# cfc-card.net
KiCad netlist of a schematic drawn in EAGLE
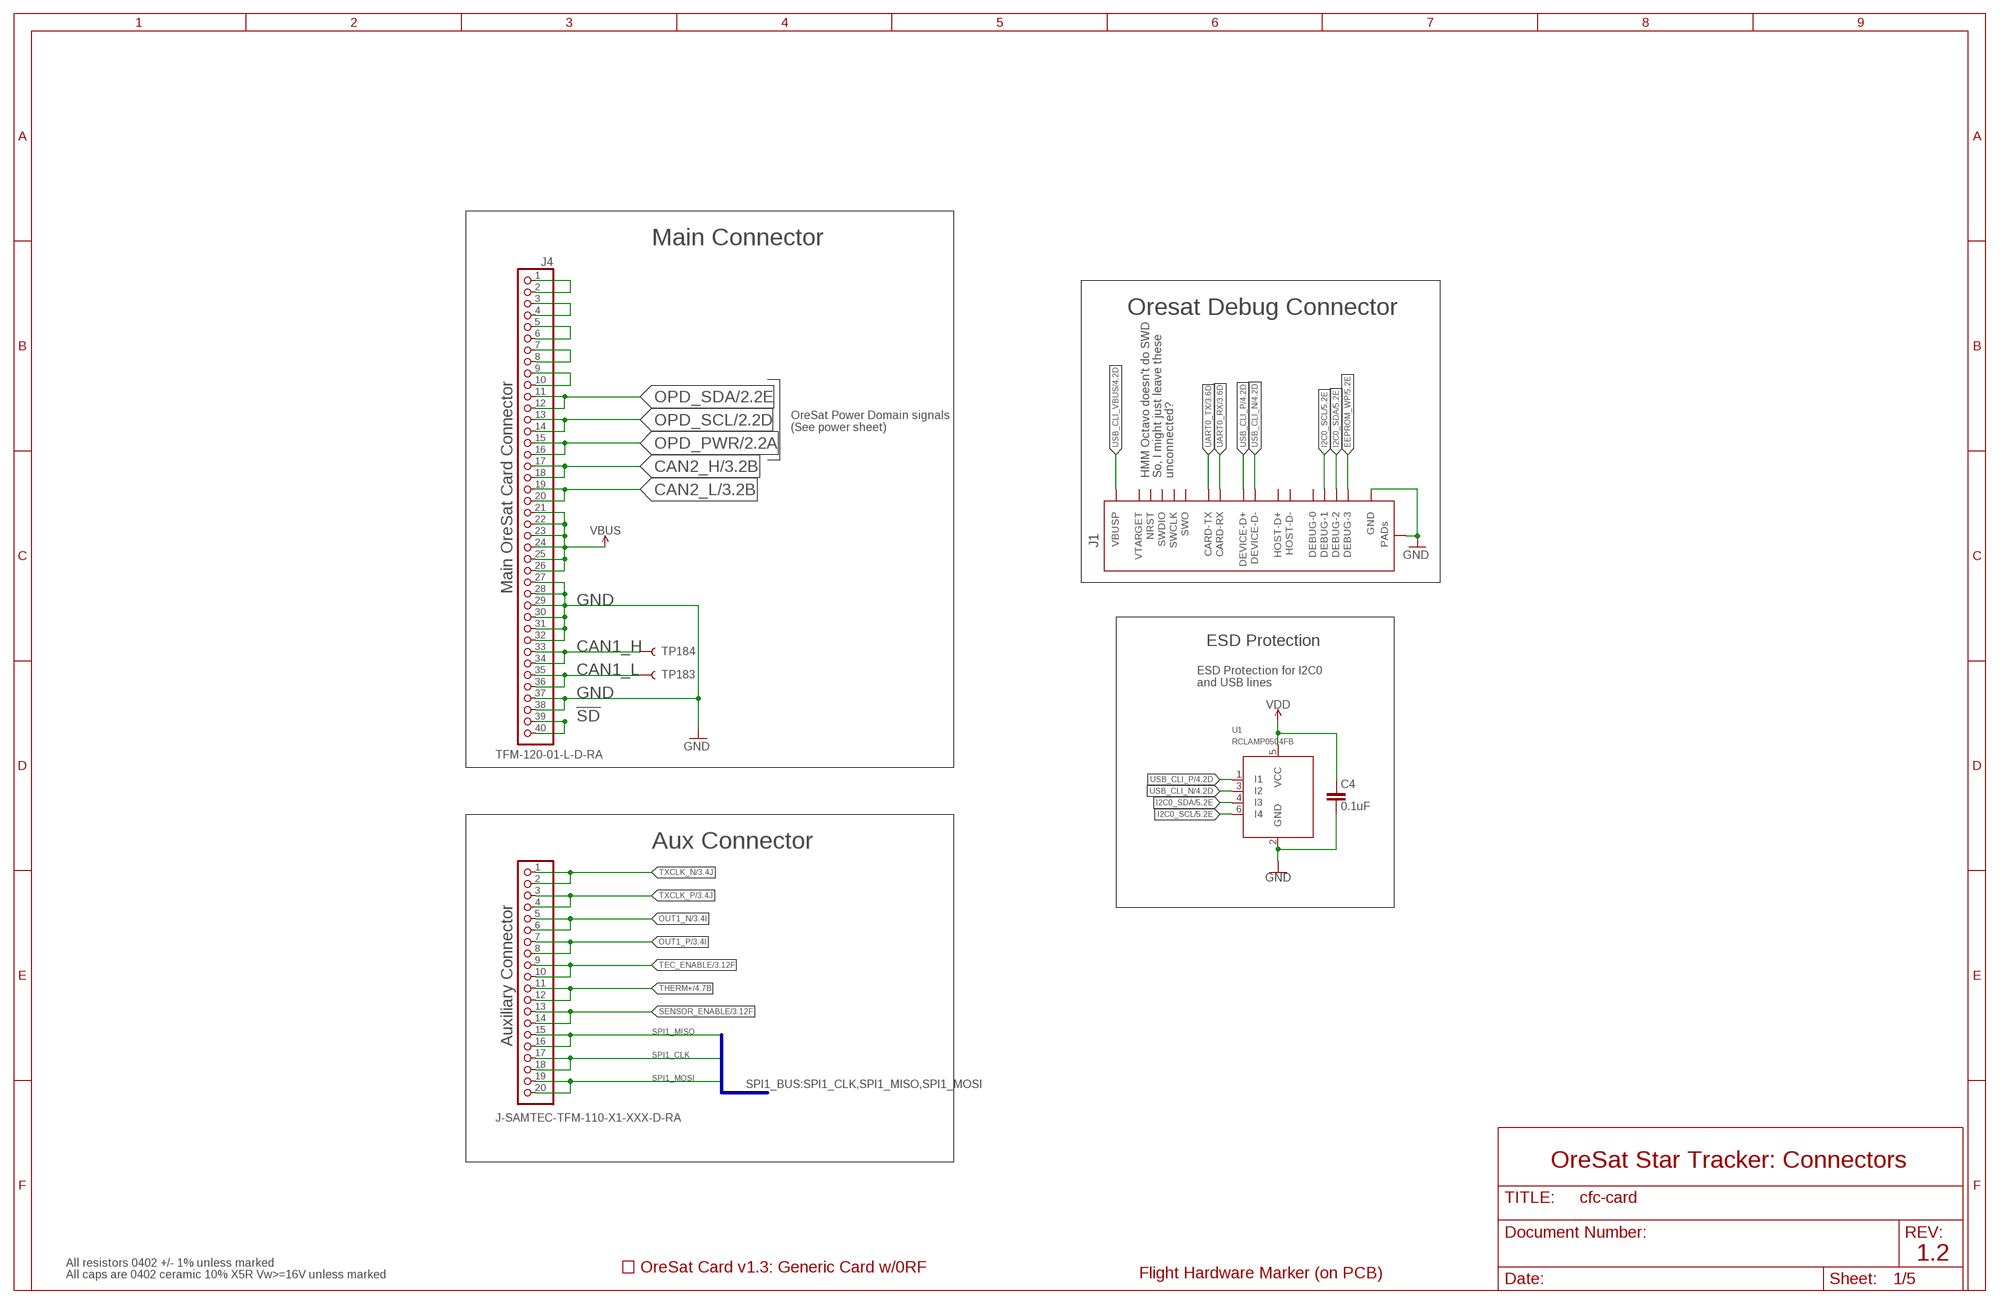
[diagram p0: schematic, sheet 1]
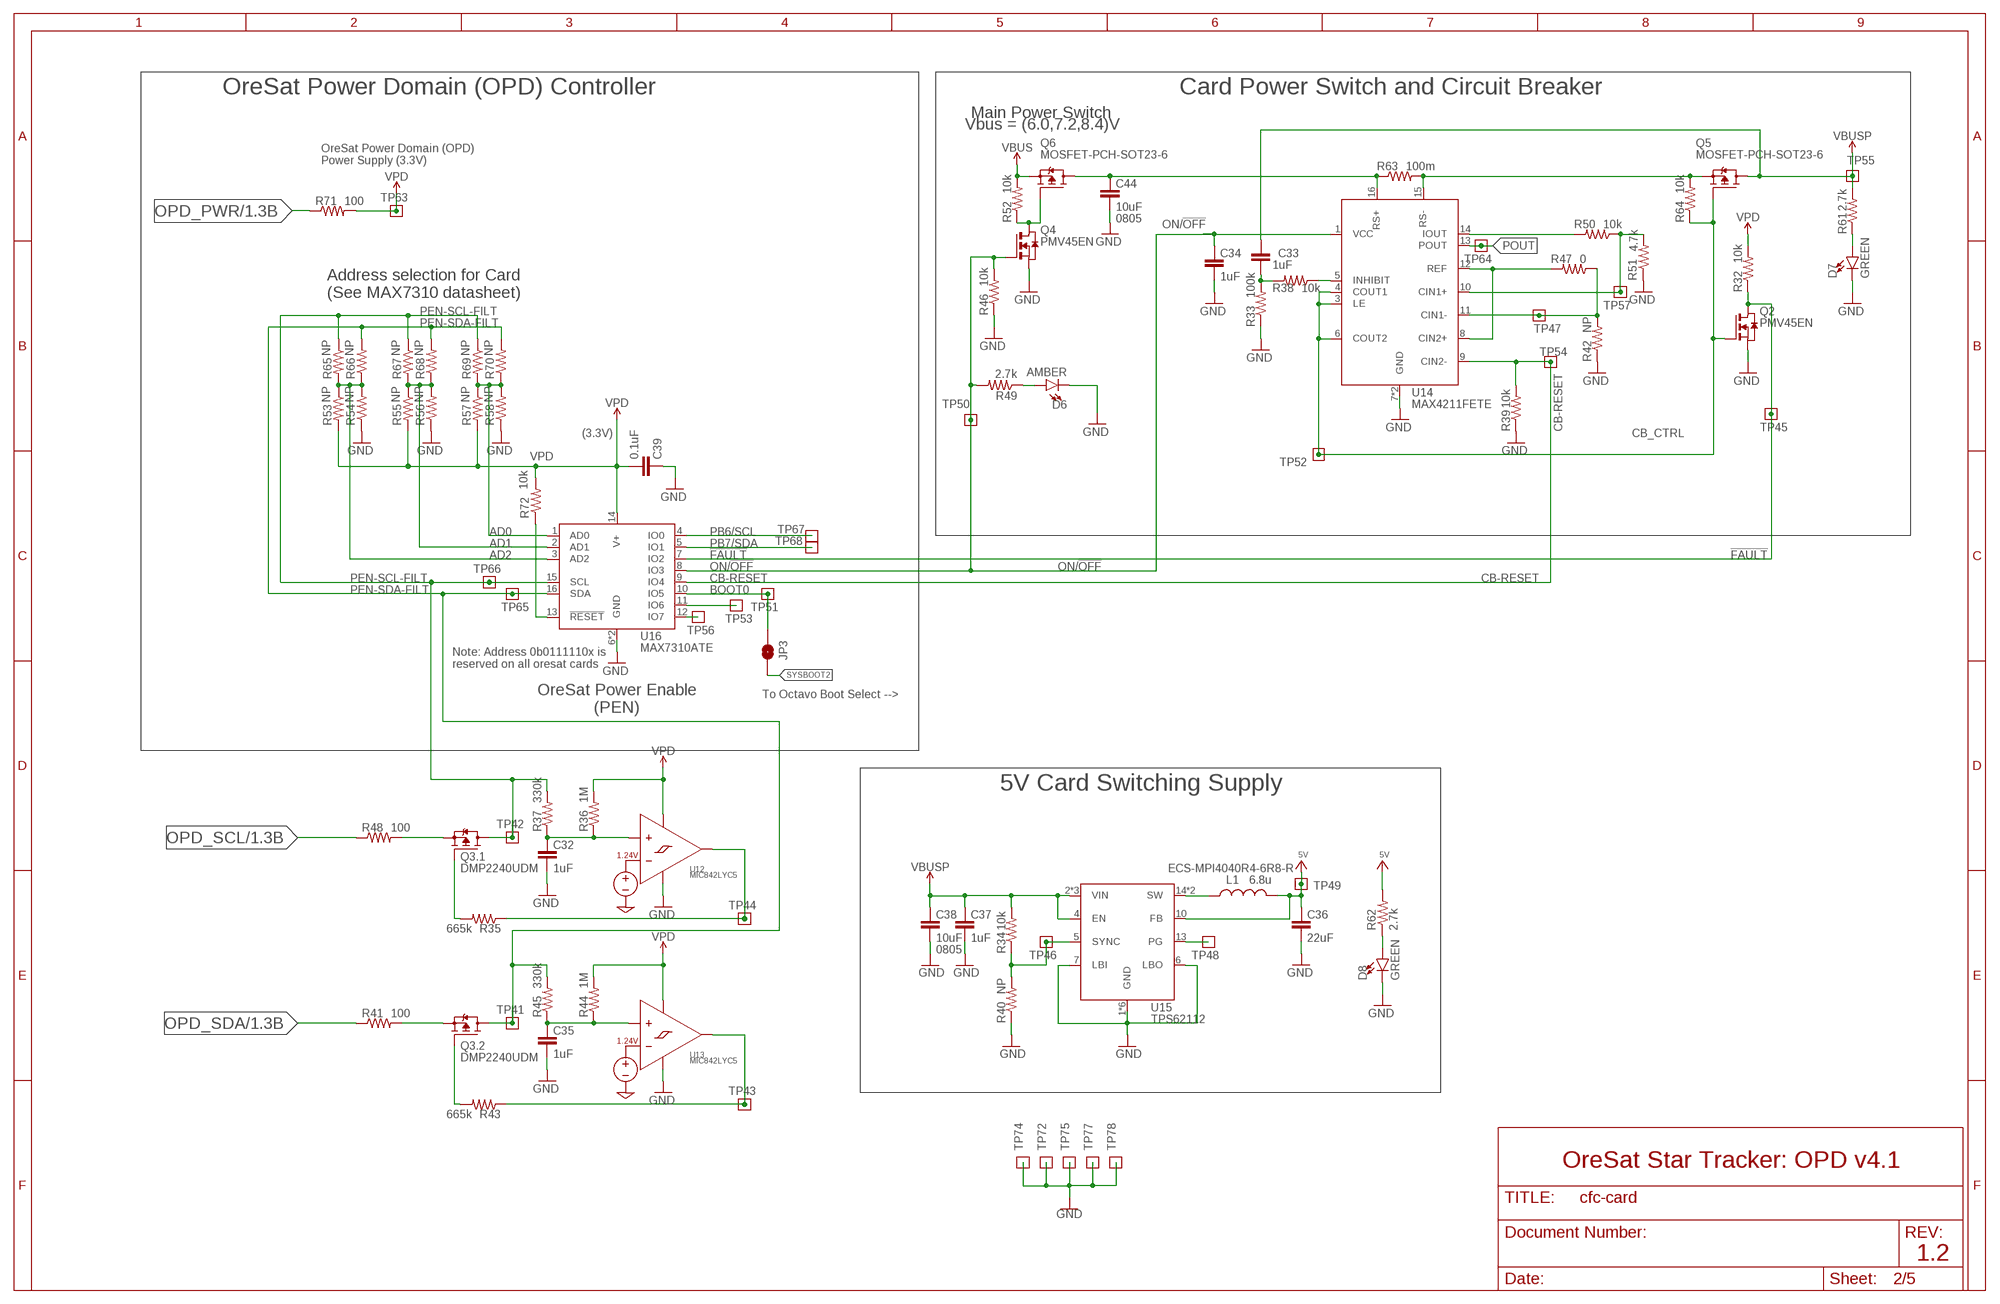
[diagram p1: schematic, sheet 2]
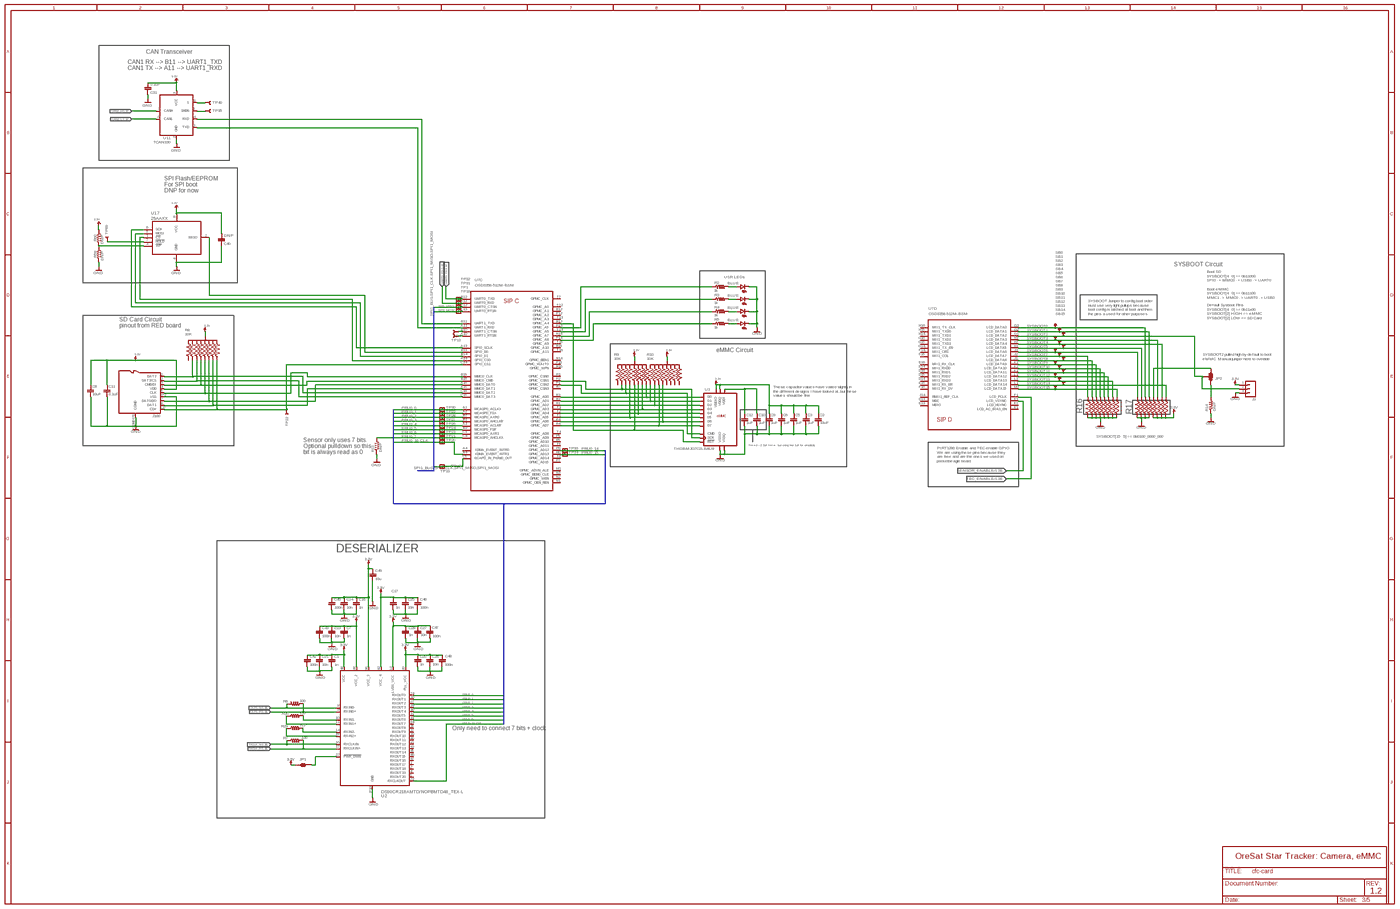
[diagram p2: schematic, sheet 3, overview]
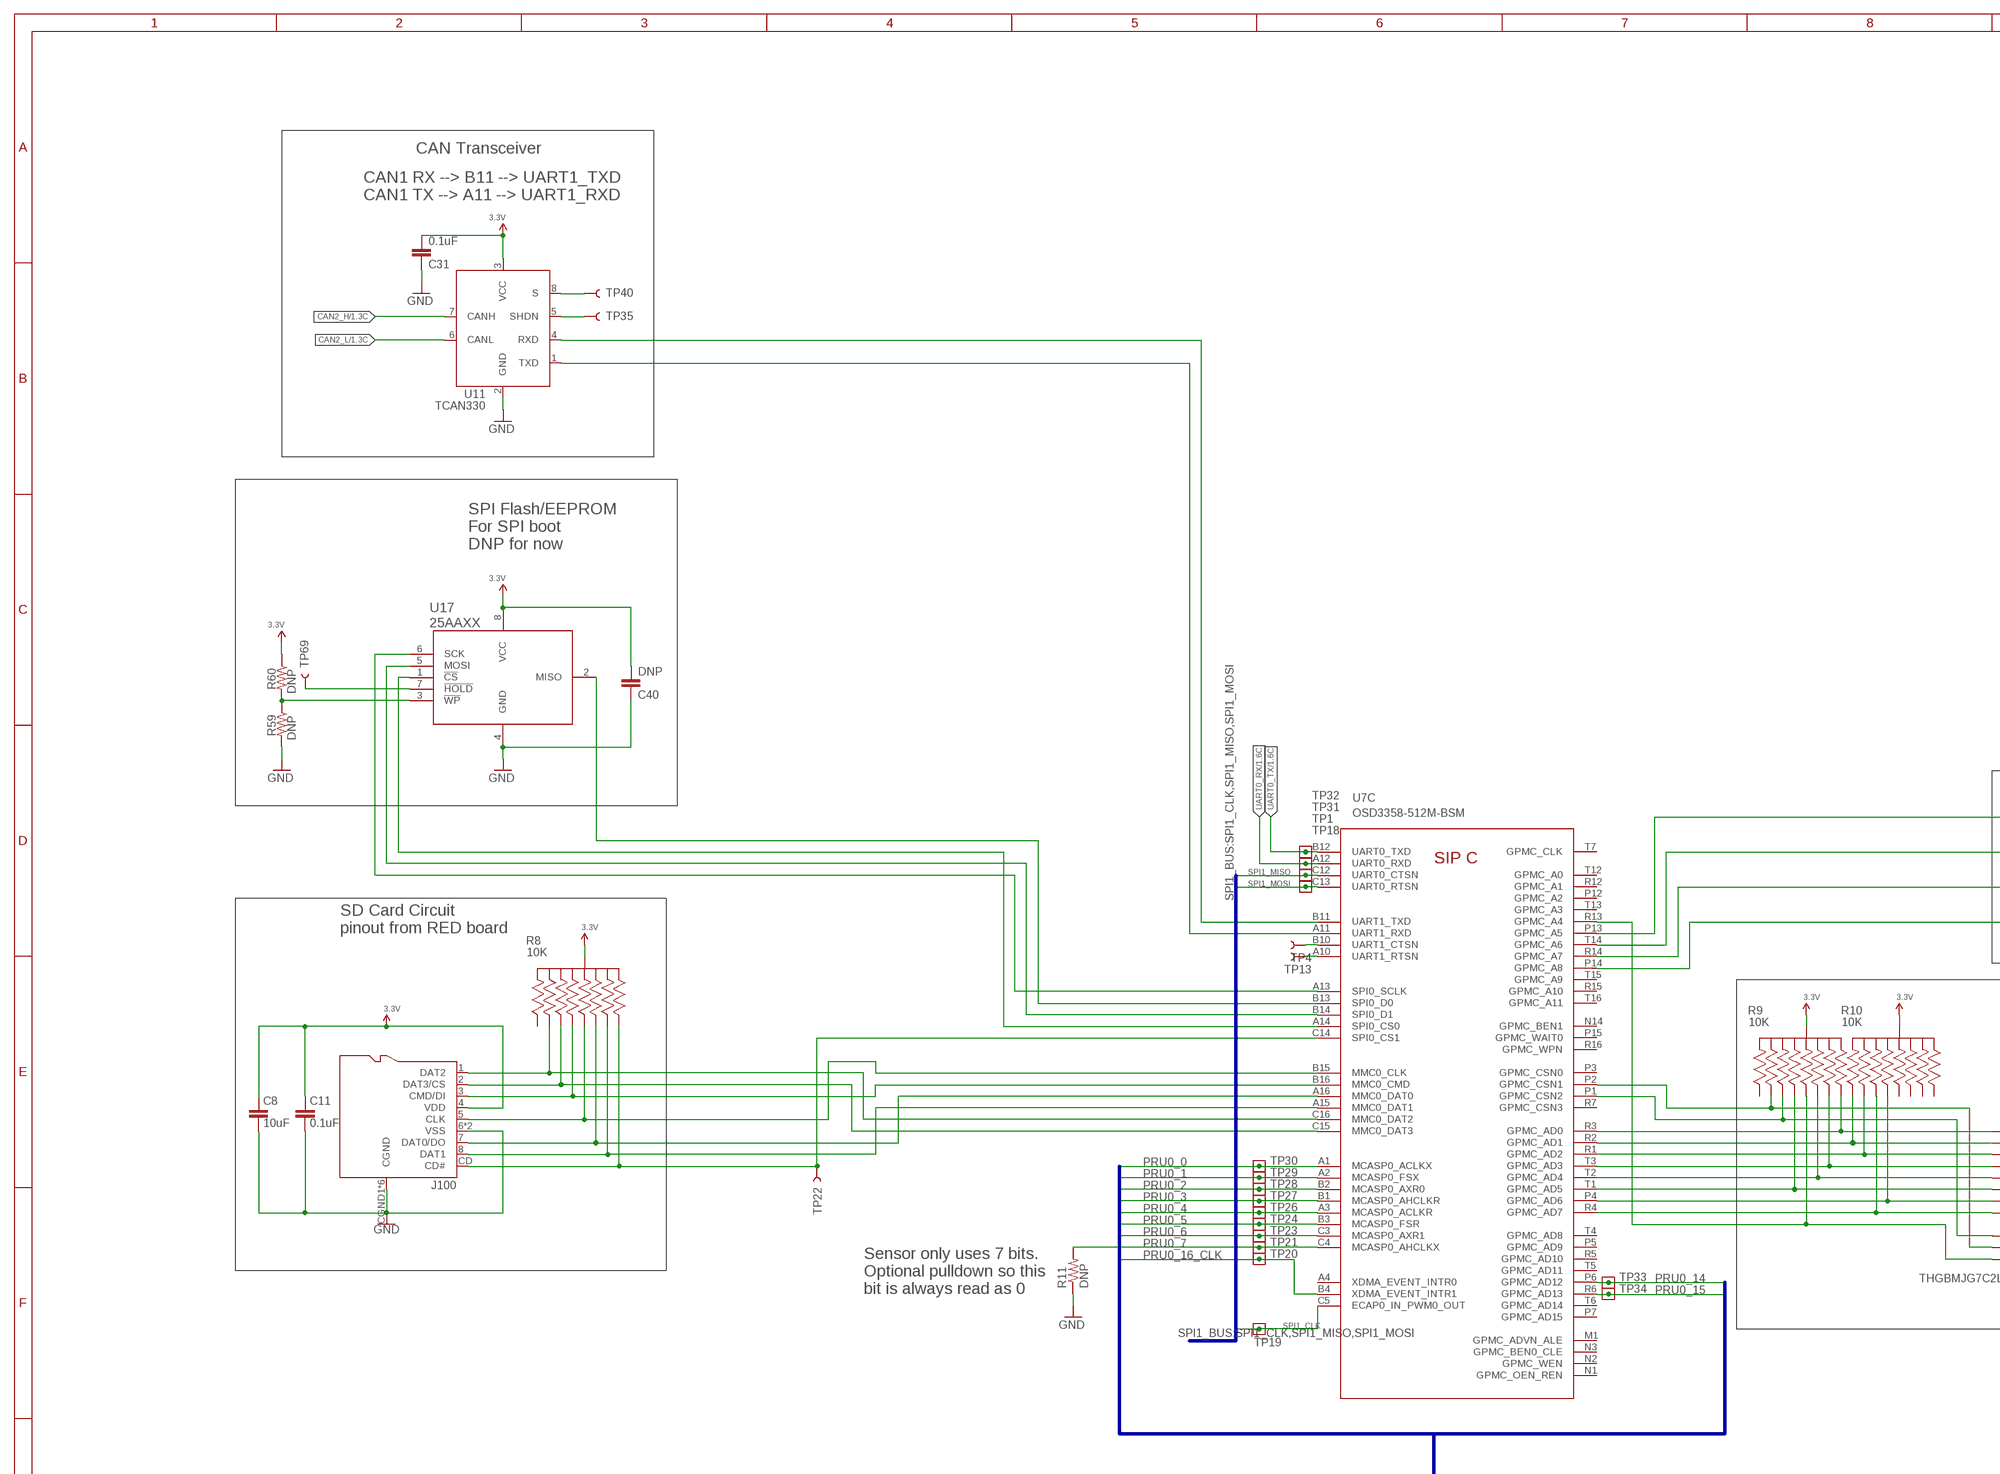
[diagram p3: schematic, sheet 3, part 1 of 4]
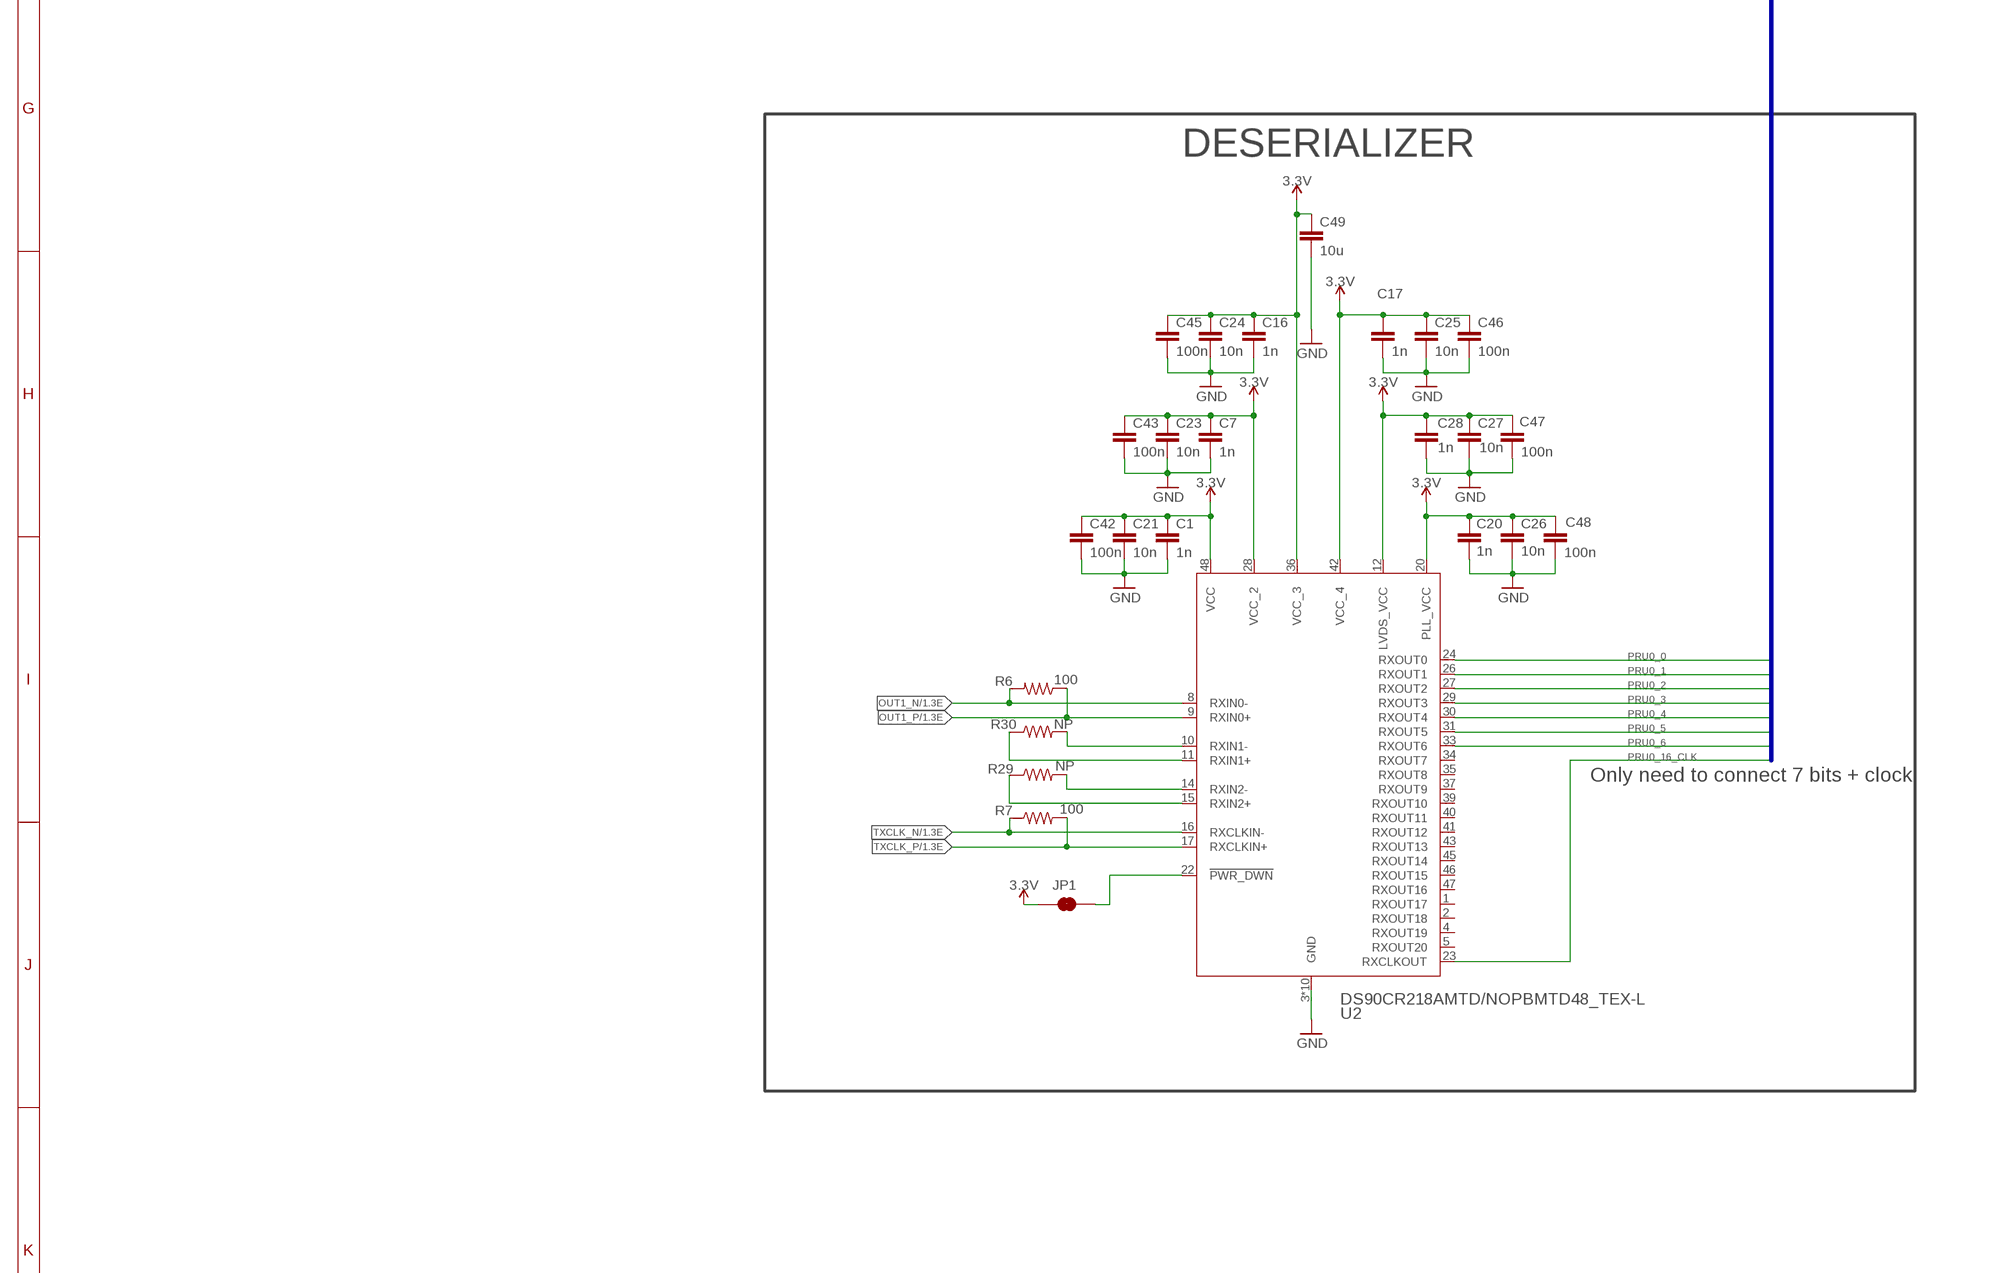
[diagram p4: schematic, sheet 3, part 2 of 4]
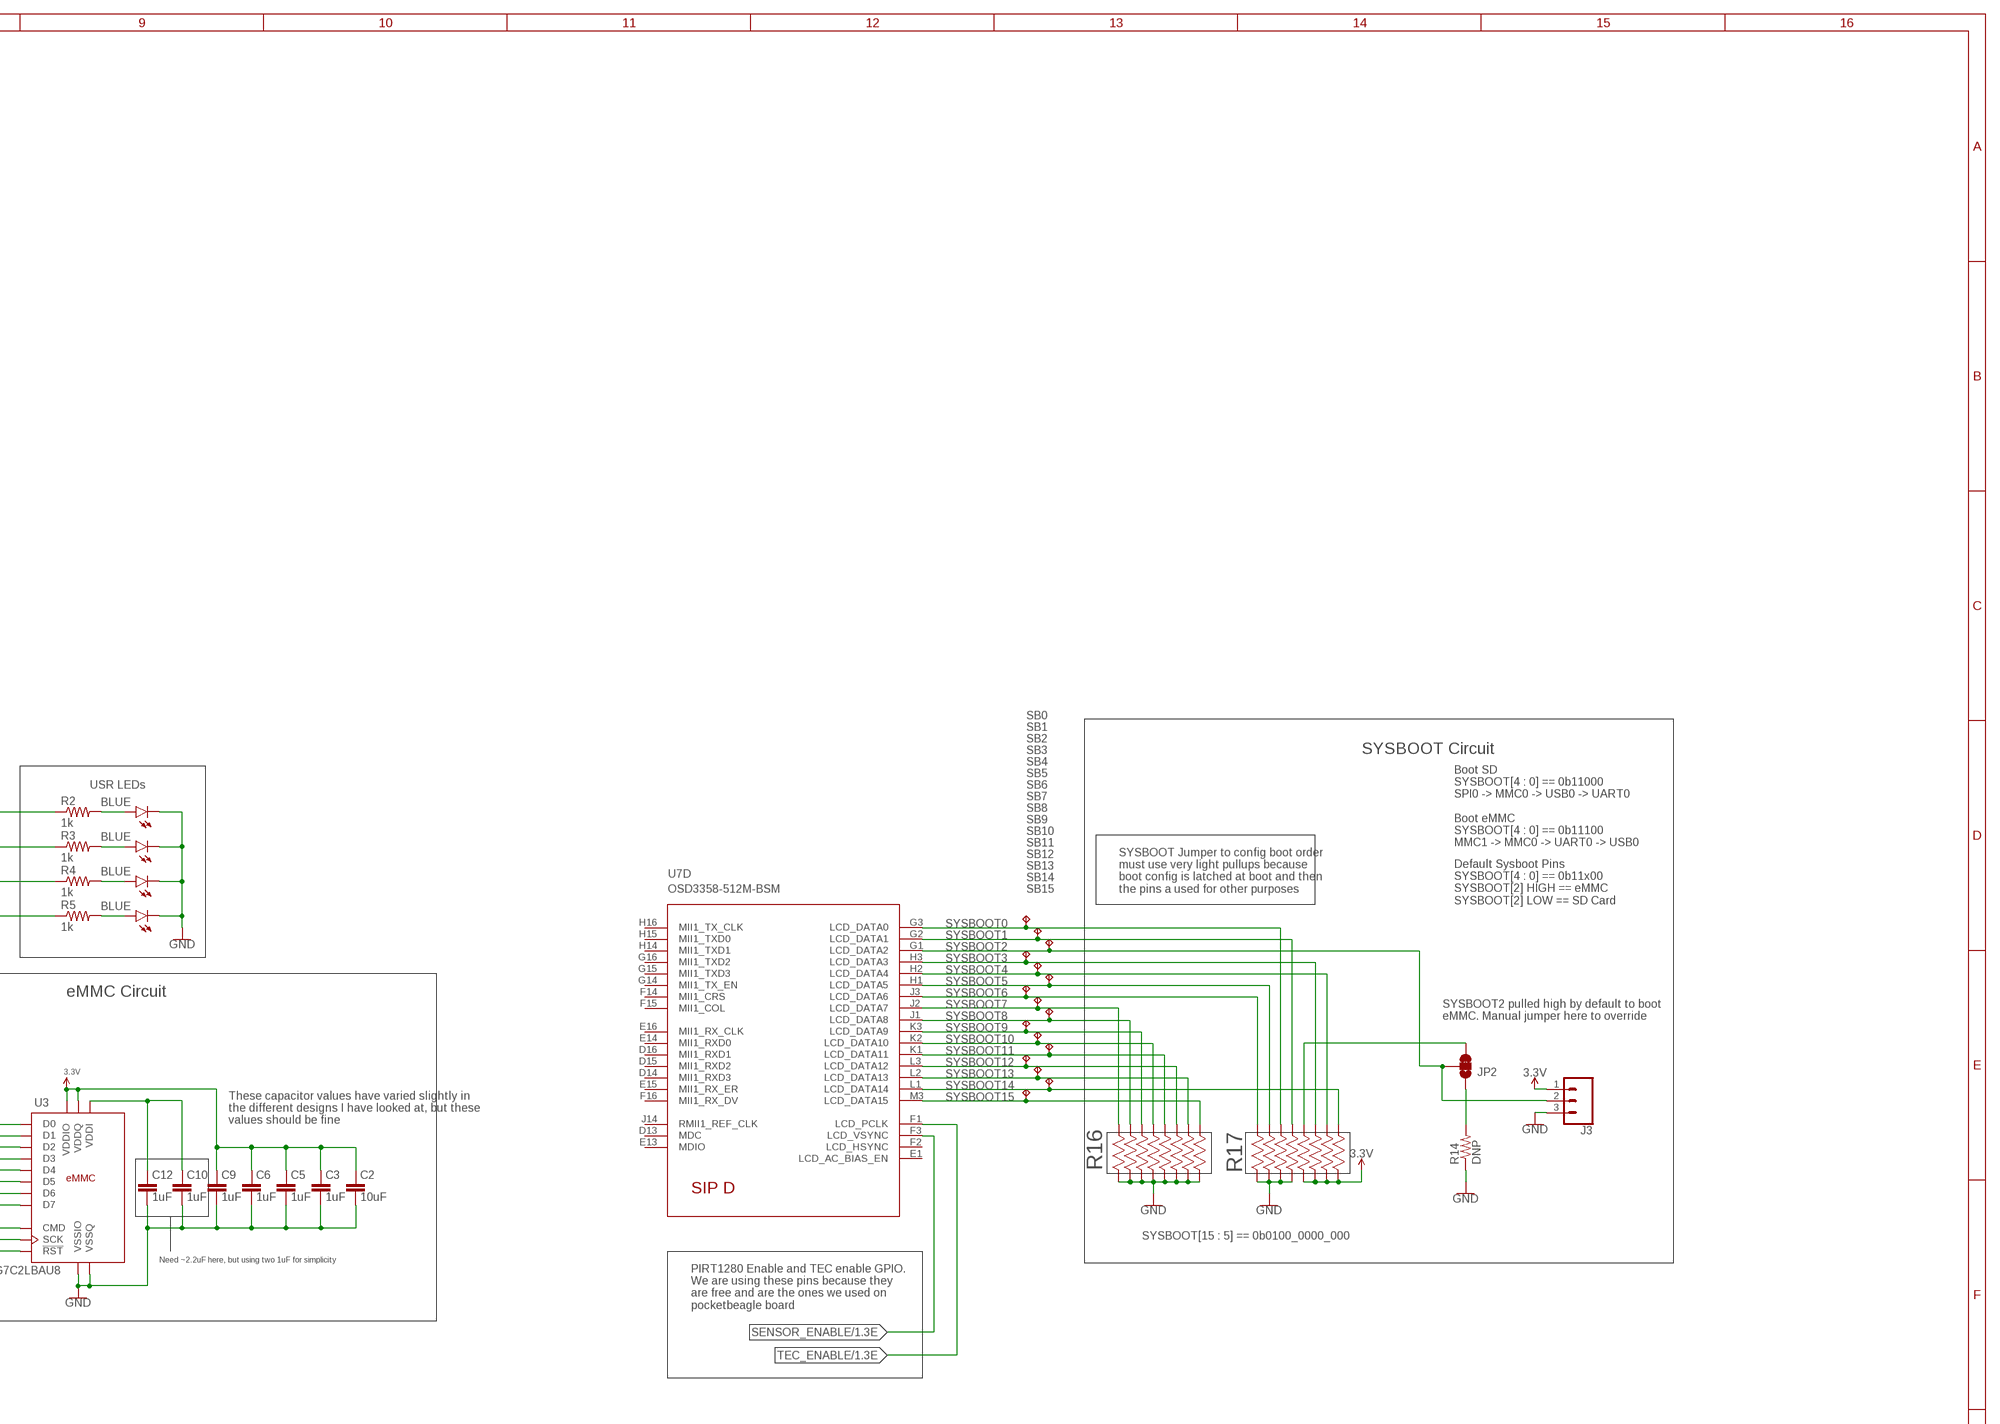
[diagram p5: schematic, sheet 3, part 3 of 4]
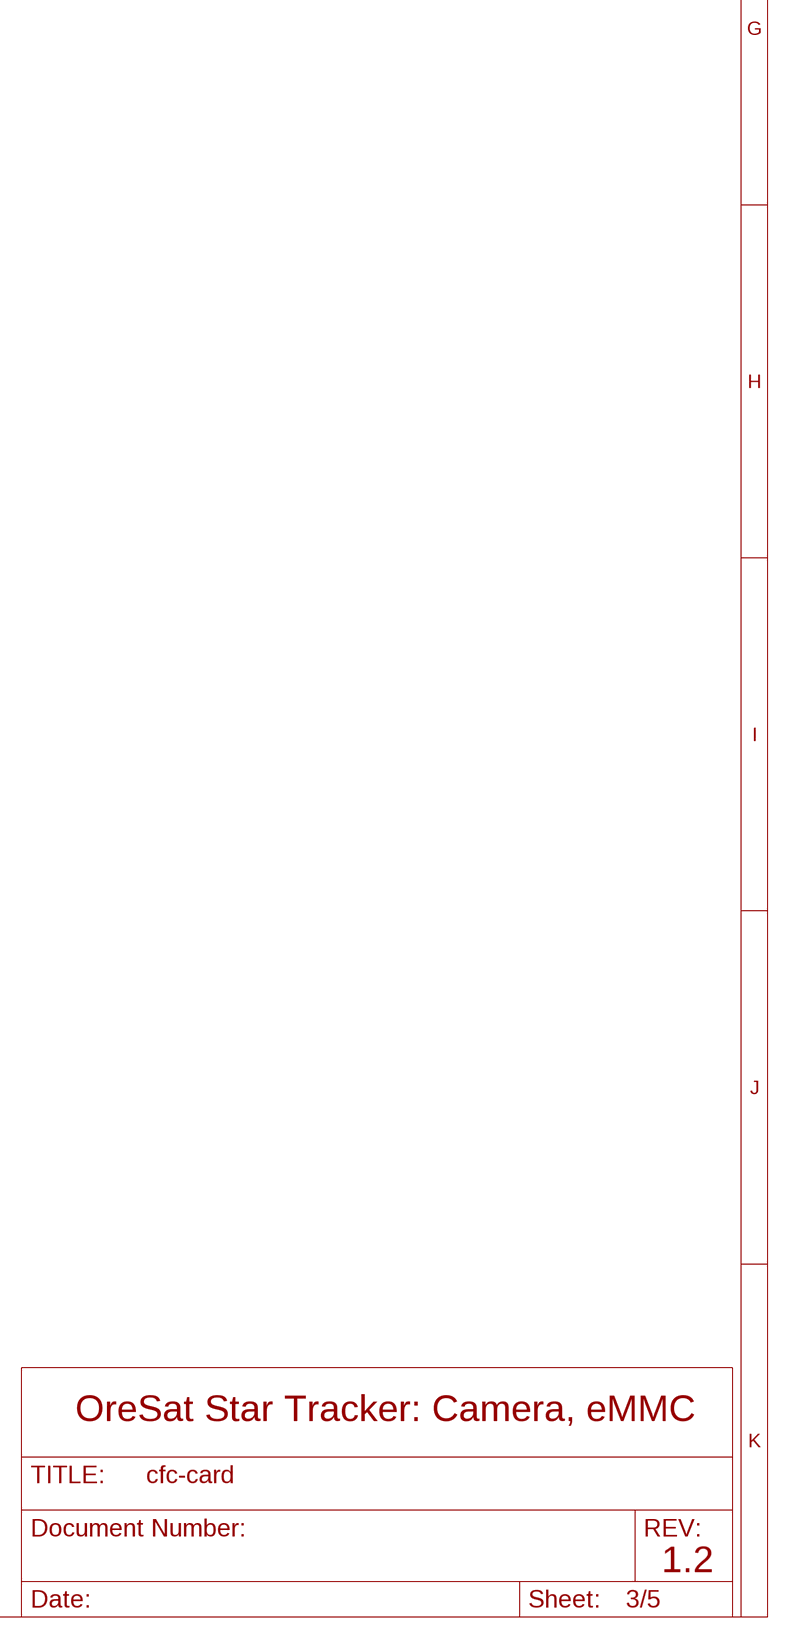
[diagram p6: schematic, sheet 3, part 4 of 4]
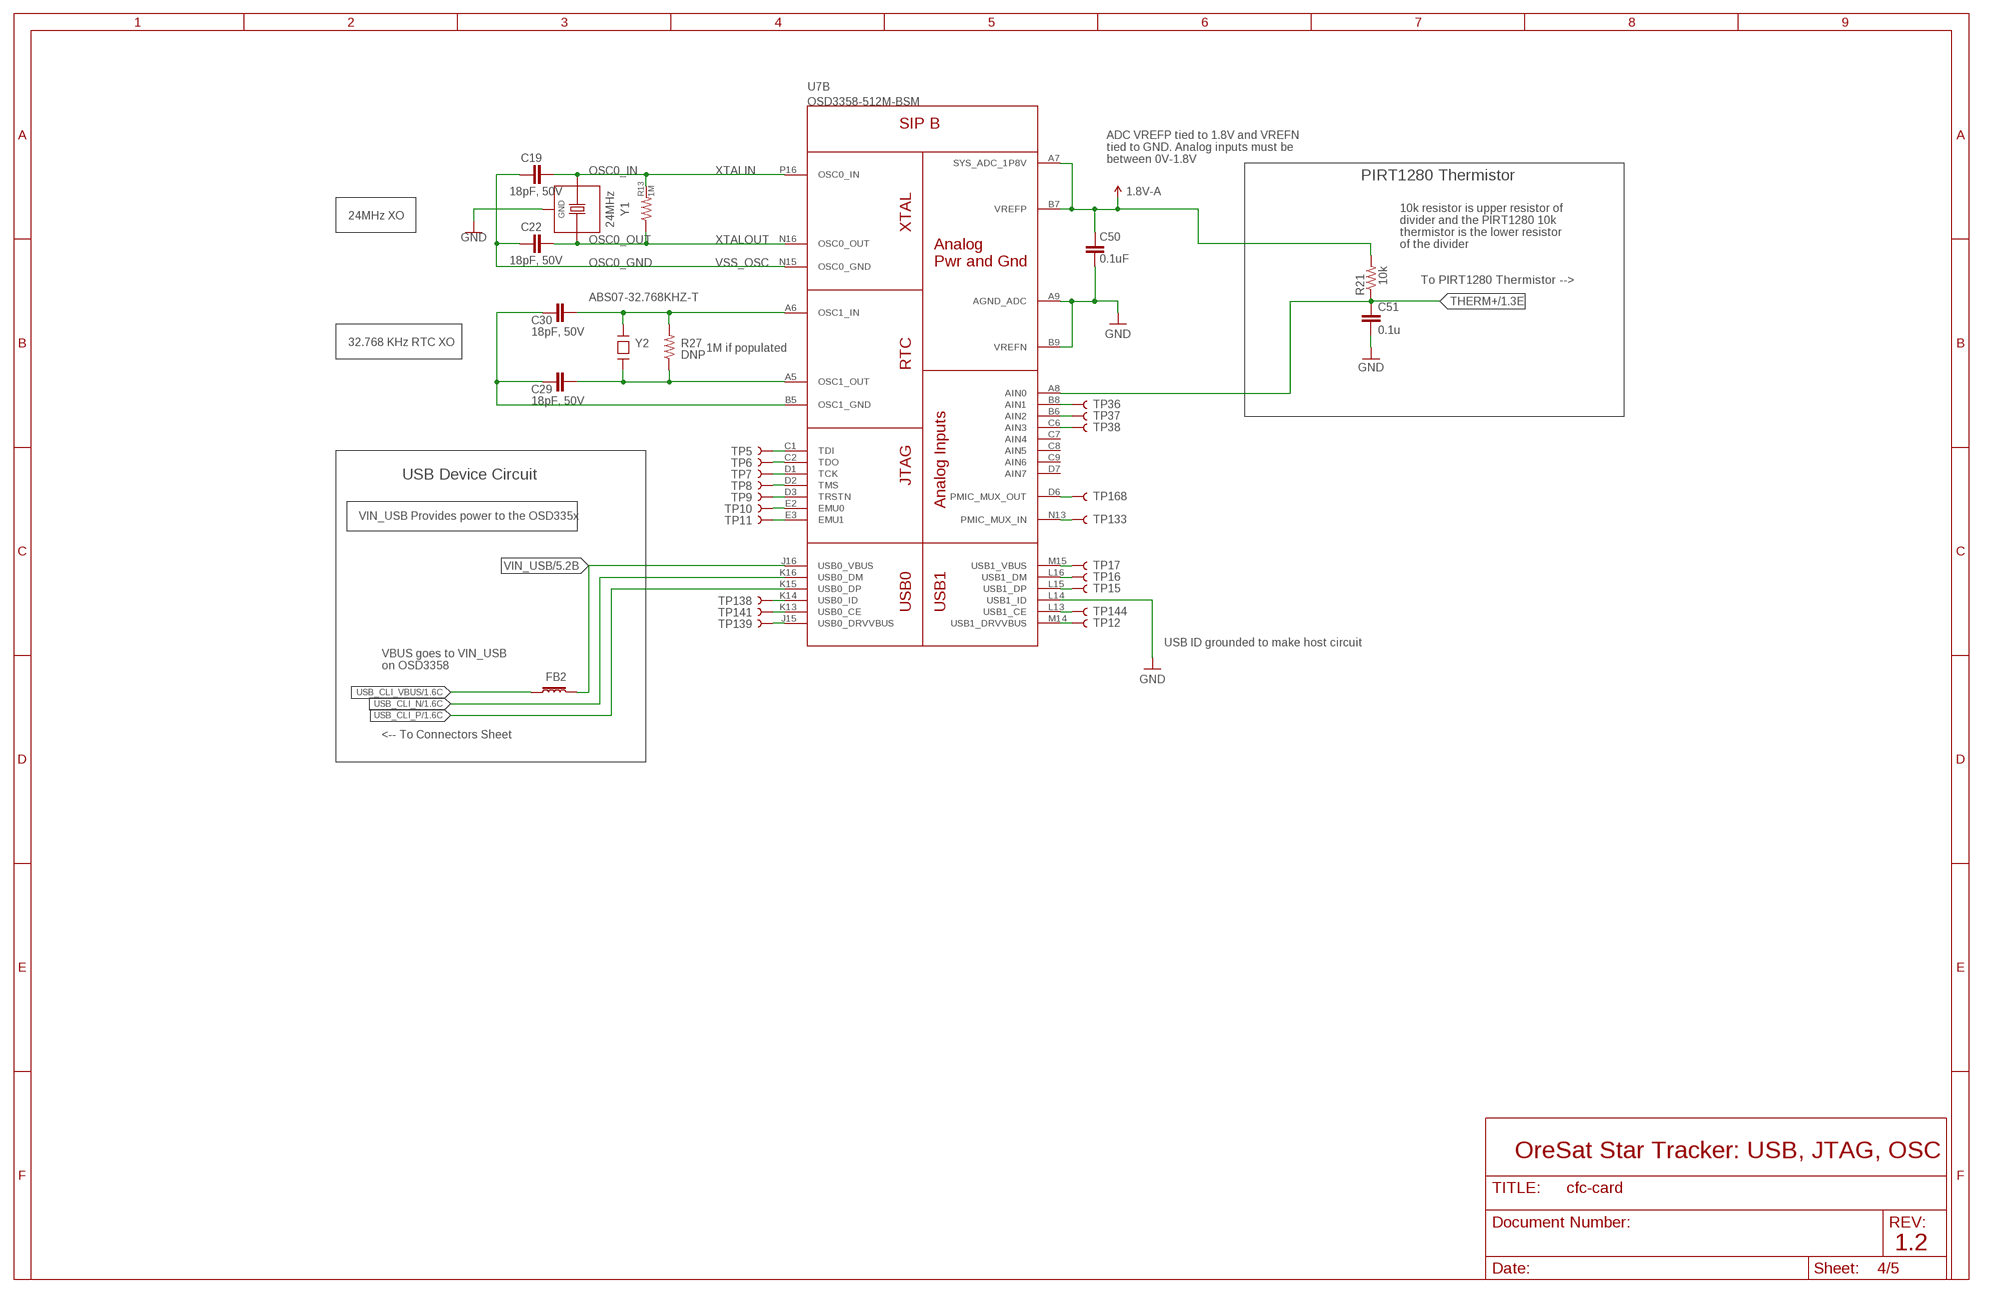
[diagram p7: schematic, sheet 4]
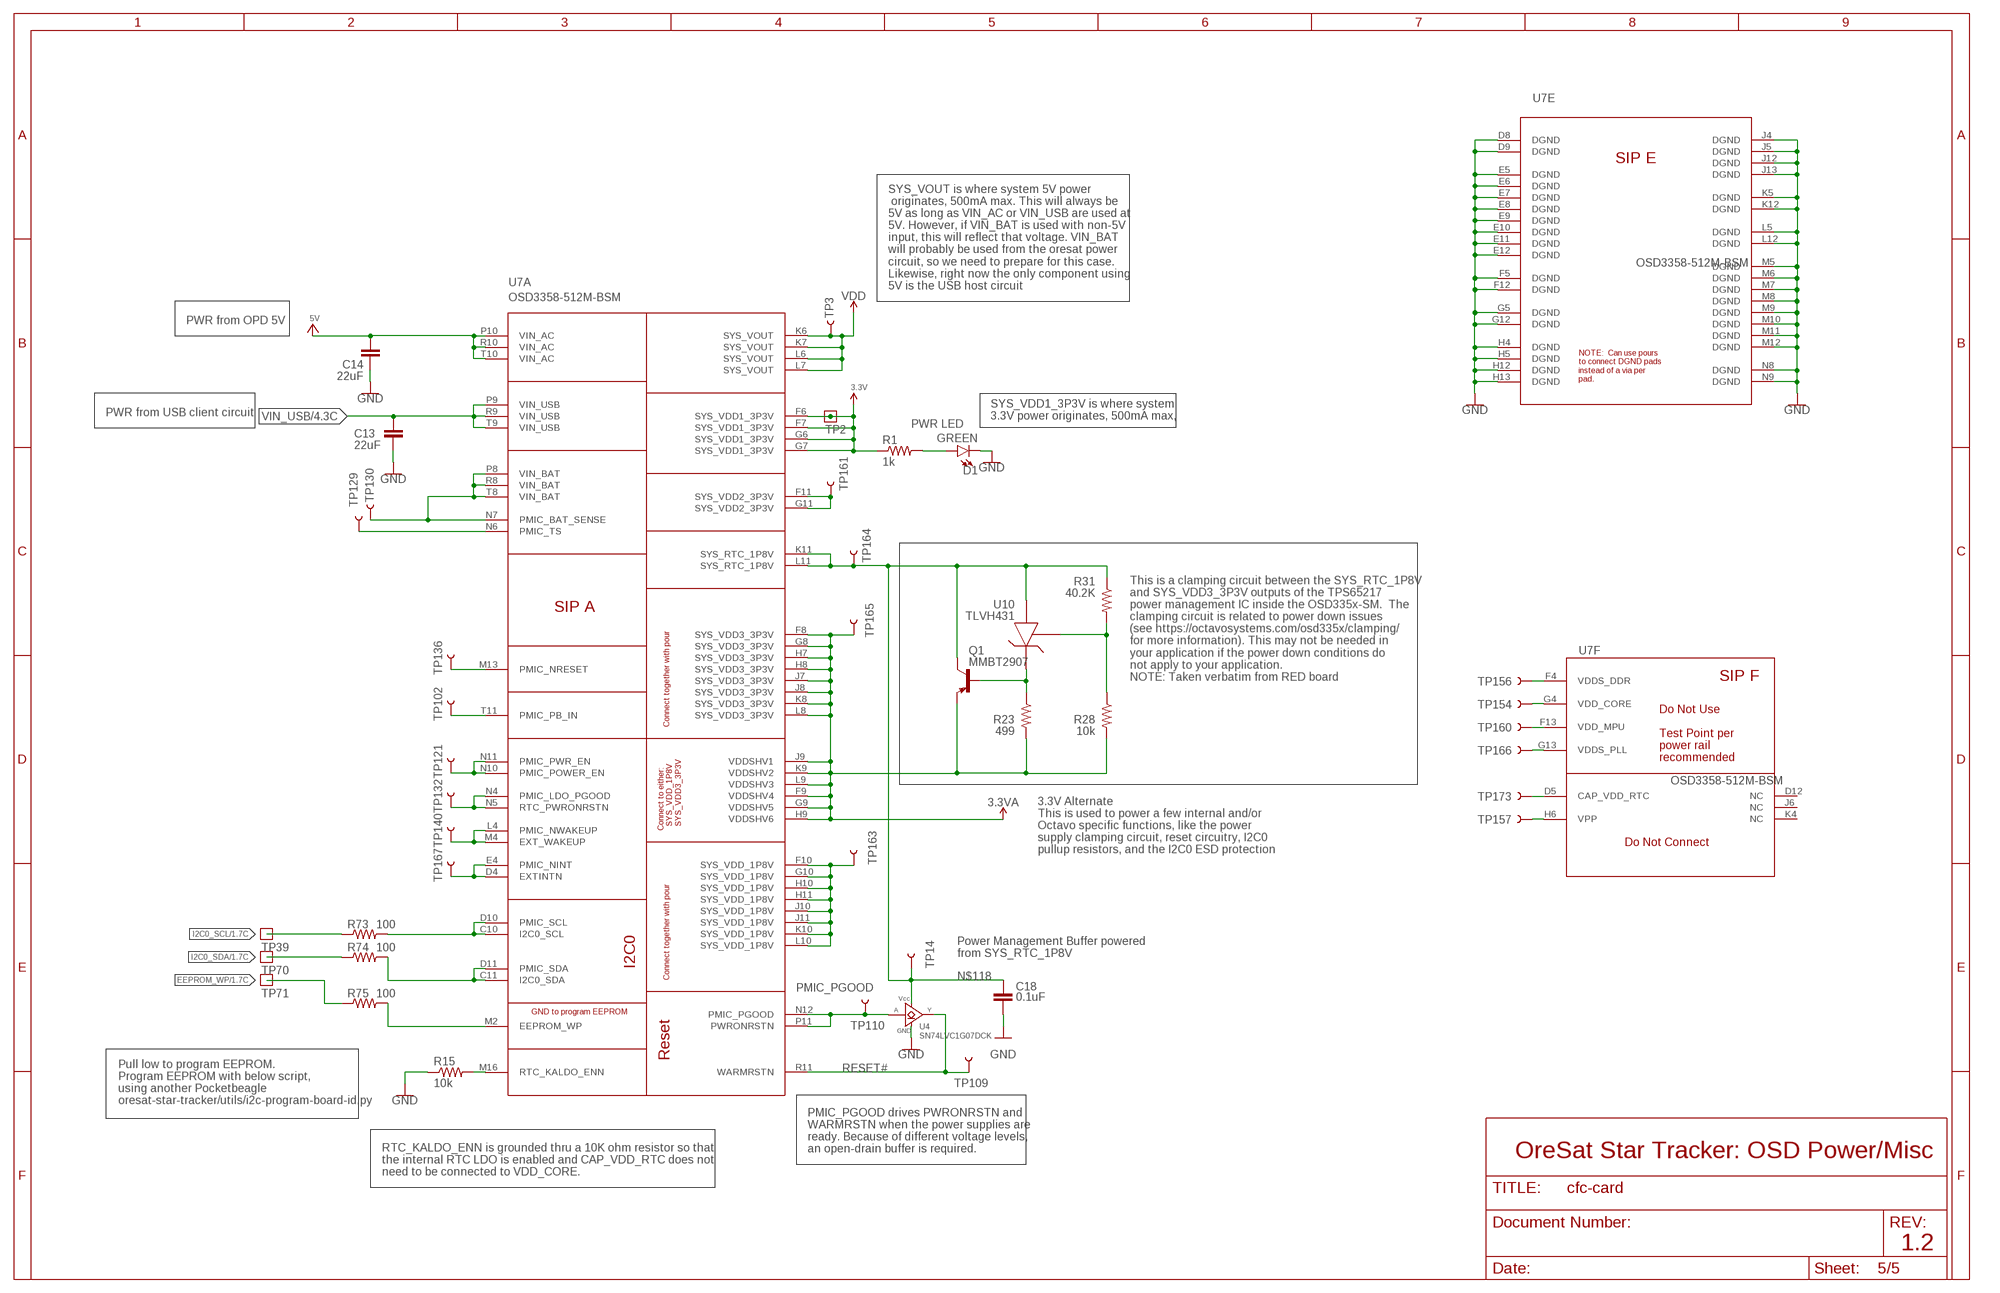
[diagram p8: schematic, sheet 5]

(export (version "E")
  (design (tool "Eeschema 10.0.6"))
  (components
    (comp (ref "C32")
      (value "1uF")
      (footprint "eagle-import:.0805-B-NOSILK")
      (libsource (lib "eagle-import") (part "C-EU0805-B-NOSILK"))
    )
    (comp (ref "C33")
      (value "1uF")
      (footprint "eagle-import:.0603-A")
      (fields (field (name "MFR") "Samsung"))
      (libsource (lib "eagle-import") (part "C-EU0603-A"))
    )
    (comp (ref "C34")
      (value "1uF")
      (footprint "eagle-import:.0603-A")
      (libsource (lib "eagle-import") (part "C-EU0603-A"))
    )
    (comp (ref "C35")
      (value "1uF")
      (footprint "eagle-import:.0805-B-NOSILK")
      (libsource (lib "eagle-import") (part "C-EU0805-B-NOSILK"))
    )
    (comp (ref "C36")
      (value "22uF")
      (footprint "eagle-import:C1210")
      (libsource (lib "eagle-import") (part "C-EUC1210"))
    )
    (comp (ref "C37")
      (value "1uF")
      (footprint "eagle-import:.0603-A")
      (libsource (lib "eagle-import") (part "C-EU0603-A"))
    )
    (comp (ref "C38")
      (value "10uF")
      (footprint "eagle-import:.0805-B")
      (libsource (lib "eagle-import") (part "C-EU0805-B"))
    )
    (comp (ref "C39")
      (value "0.1uF")
      (footprint "eagle-import:.0603-A")
      (libsource (lib "eagle-import") (part "C-EU0603-A"))
    )
    (comp (ref "C44")
      (value "10uF")
      (footprint "eagle-import:.0805-B")
      (libsource (lib "eagle-import") (part "C-EU0805-B"))
    )
    (comp (ref "D6")
      (value "AMBER")
      (footprint "eagle-import:LED-0603")
      (libsource (lib "eagle-import") (part "SparkFun-LED_529_LED-GREEN0603"))
    )
    (comp (ref "D7")
      (value "GREEN")
      (footprint "eagle-import:LED-0603")
      (libsource (lib "eagle-import") (part "LED-GREEN0603"))
    )
    (comp (ref "D8")
      (value "GREEN")
      (footprint "eagle-import:LED-0603")
      (libsource (lib "eagle-import") (part "LED-GREEN0603"))
    )
    (comp (ref "JP3")
      (value "JUMPER-SMT_2_NO_SILK")
      (footprint "eagle-import:SMT-JUMPER_2_NO_SILK")
      (libsource (lib "eagle-import") (part "JUMPER-SMT_2_NO_SILK"))
    )
    (comp (ref "L1")
      (value "6.8u")
      (footprint "eagle-import:ECS-MPI4040")
      (fields (field (name "MPN") "ECS-MPI4040R4-6R8-R"))
      (libsource (lib "eagle-import") (part "L-ECS-MPI4040"))
    )
    (comp (ref "Q2")
      (value "PMV45EN")
      (footprint "eagle-import:SOT23")
      (fields (field (name "MPN") "PMV45EN2R"))
      (libsource (lib "eagle-import") (part "PMV45EN"))
    )
    (comp (ref "Q3")
      (value "DMP2240UDM")
      (footprint "eagle-import:SOT23-6")
      (fields (field (name "MFR") "Diodes Inc") (field (name "MPN") "DMP2240UDM-7"))
      (libsource (lib "eagle-import") (part "Q-MOSFET-PCH-dual-SOT23-6_MOSFET-PCH-SOT23-6"))
    )
    (comp (ref "Q4")
      (value "PMV45EN")
      (footprint "eagle-import:SOT23")
      (fields (field (name "MPN") "PMV45EN2R"))
      (libsource (lib "eagle-import") (part "PMV45EN"))
    )
    (comp (ref "Q5")
      (value "MOSFET-PCH-SOT23-6")
      (footprint "eagle-import:SOT23-6")
      (fields (field (name "MPN") "DMP3050LVT-7") (field (name "MPN_1") "DMP3050LVT-7"))
      (libsource (lib "eagle-import") (part "MOSFET-PCH-SOT23-6"))
    )
    (comp (ref "Q6")
      (value "MOSFET-PCH-SOT23-6")
      (footprint "eagle-import:SOT23-6")
      (fields (field (name "MPN") "DMP3050LVT-7") (field (name "MPN_1") "DMP3050LVT-7"))
      (libsource (lib "eagle-import") (part "MOSFET-PCH-SOT23-6"))
    )
    (comp (ref "R32")
      (value "10k")
      (footprint "eagle-import:.0603-A")
      (libsource (lib "eagle-import") (part "R-US_0603-A"))
    )
    (comp (ref "R33")
      (value "100k")
      (footprint "eagle-import:.0603-A")
      (fields (field (name "MFR") "Samsung") (field (name "MPN") "RC1005F6653CS"))
      (libsource (lib "eagle-import") (part "R-US_0603-A"))
    )
    (comp (ref "R34")
      (value "10k")
      (footprint "eagle-import:.0603-A")
      (libsource (lib "eagle-import") (part "R-US_0603-A"))
    )
    (comp (ref "R35")
      (value "665k")
      (footprint "eagle-import:.0603-A")
      (libsource (lib "eagle-import") (part "R-US_0603-A"))
    )
    (comp (ref "R36")
      (value "1M")
      (footprint "eagle-import:.0603-A")
      (libsource (lib "eagle-import") (part "R-US_0603-A"))
    )
    (comp (ref "R37")
      (value "330k")
      (footprint "eagle-import:.0603-A")
      (libsource (lib "eagle-import") (part "R-US_0603-A"))
    )
    (comp (ref "R38")
      (value "10k")
      (footprint "eagle-import:.0603-A")
      (fields (field (name "MFR") "Samsung") (field (name "MPN") "RC1005F6653CS"))
      (libsource (lib "eagle-import") (part "R-US_0603-A"))
    )
    (comp (ref "R39")
      (value "10k")
      (footprint "eagle-import:.0603-A")
      (libsource (lib "eagle-import") (part "R-US_0603-A"))
    )
    (comp (ref "R40")
      (value "NP")
      (footprint "eagle-import:.0603-A")
      (fields (field (name "MFR") "Samsung") (field (name "MPN") "RC1005F6653CS"))
      (libsource (lib "eagle-import") (part "R-US_0603-A"))
    )
    (comp (ref "R41")
      (value "100")
      (footprint "eagle-import:.0603-A")
      (libsource (lib "eagle-import") (part "R-US_0603-A"))
    )
    (comp (ref "R42")
      (value "NP")
      (footprint "eagle-import:.0603-A")
      (fields (field (name "MFR") "Samsung") (field (name "MPN") "RC1005F6653CS"))
      (libsource (lib "eagle-import") (part "R-US_0603-A"))
    )
    (comp (ref "R43")
      (value "665k")
      (footprint "eagle-import:.0603-A")
      (libsource (lib "eagle-import") (part "R-US_0603-A"))
    )
    (comp (ref "R44")
      (value "1M")
      (footprint "eagle-import:.0603-A")
      (libsource (lib "eagle-import") (part "R-US_0603-A"))
    )
    (comp (ref "R45")
      (value "330k")
      (footprint "eagle-import:.0603-A")
      (libsource (lib "eagle-import") (part "R-US_0603-A"))
    )
    (comp (ref "R46")
      (value "10k")
      (footprint "eagle-import:.0603-A")
      (libsource (lib "eagle-import") (part "R-US_0603-A"))
    )
    (comp (ref "R47")
      (value "0")
      (footprint "eagle-import:.0603-A")
      (libsource (lib "eagle-import") (part "R-US_0603-A"))
    )
    (comp (ref "R48")
      (value "100")
      (footprint "eagle-import:.0603-A")
      (libsource (lib "eagle-import") (part "R-US_0603-A"))
    )
    (comp (ref "R49")
      (value "2.7k")
      (footprint "eagle-import:.0603-A")
      (libsource (lib "eagle-import") (part "R-US_0603-A"))
    )
    (comp (ref "R50")
      (value "10k")
      (footprint "eagle-import:.0603-A")
      (libsource (lib "eagle-import") (part "R-US_0603-A"))
    )
    (comp (ref "R51")
      (value "4.7k")
      (footprint "eagle-import:.0603-A")
      (fields (field (name "MFR") "Samsung") (field (name "MPN") "RC1005F6653CS"))
      (libsource (lib "eagle-import") (part "R-US_0603-A"))
    )
    (comp (ref "R52")
      (value "10k")
      (footprint "eagle-import:.0603-A")
      (libsource (lib "eagle-import") (part "R-US_0603-A"))
    )
    (comp (ref "R53")
      (value "NP")
      (footprint "eagle-import:.0603-A")
      (fields (field (name "MFR") "Samsung") (field (name "MPN") "RC1005F6653CS"))
      (libsource (lib "eagle-import") (part "R-US_0603-A"))
    )
    (comp (ref "R54")
      (value "NP")
      (footprint "eagle-import:.0603-A")
      (fields (field (name "MFR") "Samsung") (field (name "MPN") "RC1005F6653CS"))
      (libsource (lib "eagle-import") (part "R-US_0603-A"))
    )
    (comp (ref "R55")
      (value "NP")
      (footprint "eagle-import:.0603-A")
      (fields (field (name "MFR") "Samsung") (field (name "MPN") "RC1005F6653CS"))
      (libsource (lib "eagle-import") (part "R-US_0603-A"))
    )
    (comp (ref "R56")
      (value "NP")
      (footprint "eagle-import:.0603-A")
      (fields (field (name "MFR") "Samsung") (field (name "MPN") "RC1005F6653CS"))
      (libsource (lib "eagle-import") (part "R-US_0603-A"))
    )
    (comp (ref "R57")
      (value "NP")
      (footprint "eagle-import:.0603-A")
      (fields (field (name "MFR") "Samsung") (field (name "MPN") "RC1005F6653CS"))
      (libsource (lib "eagle-import") (part "R-US_0603-A"))
    )
    (comp (ref "R58")
      (value "NP")
      (footprint "eagle-import:.0603-A")
      (fields (field (name "MFR") "Samsung") (field (name "MPN") "RC1005F6653CS"))
      (libsource (lib "eagle-import") (part "R-US_0603-A"))
    )
    (comp (ref "R61")
      (value "2.7k")
      (footprint "eagle-import:.0603-A")
      (libsource (lib "eagle-import") (part "R-US_0603-A"))
    )
    (comp (ref "R62")
      (value "2.7k")
      (footprint "eagle-import:.0603-A")
      (libsource (lib "eagle-import") (part "R-US_0603-A"))
    )
    (comp (ref "R63")
      (value "100m")
      (footprint "eagle-import:R1206")
      (libsource (lib "eagle-import") (part "rcl_334_R-US_R1206"))
    )
    (comp (ref "R64")
      (value "10k")
      (footprint "eagle-import:.0603-A")
      (libsource (lib "eagle-import") (part "R-US_0603-A"))
    )
    (comp (ref "R65")
      (value "NP")
      (footprint "eagle-import:.0603-A")
      (fields (field (name "MFR") "Samsung") (field (name "MPN") "RC1005F6653CS"))
      (libsource (lib "eagle-import") (part "R-US_0603-A"))
    )
    (comp (ref "R66")
      (value "NP")
      (footprint "eagle-import:.0603-A")
      (fields (field (name "MFR") "Samsung") (field (name "MPN") "RC1005F6653CS"))
      (libsource (lib "eagle-import") (part "R-US_0603-A"))
    )
    (comp (ref "R67")
      (value "NP")
      (footprint "eagle-import:.0603-A")
      (fields (field (name "MFR") "Samsung") (field (name "MPN") "RC1005F6653CS"))
      (libsource (lib "eagle-import") (part "R-US_0603-A"))
    )
    (comp (ref "R68")
      (value "NP")
      (footprint "eagle-import:.0603-A")
      (fields (field (name "MFR") "Samsung") (field (name "MPN") "RC1005F6653CS"))
      (libsource (lib "eagle-import") (part "R-US_0603-A"))
    )
    (comp (ref "R69")
      (value "NP")
      (footprint "eagle-import:.0603-A")
      (fields (field (name "MFR") "Samsung") (field (name "MPN") "RC1005F6653CS"))
      (libsource (lib "eagle-import") (part "R-US_0603-A"))
    )
    (comp (ref "R70")
      (value "NP")
      (footprint "eagle-import:.0603-A")
      (fields (field (name "MFR") "Samsung") (field (name "MPN") "RC1005F6653CS"))
      (libsource (lib "eagle-import") (part "R-US_0603-A"))
    )
    (comp (ref "R71")
      (value "100")
      (footprint "eagle-import:.0603-A")
      (libsource (lib "eagle-import") (part "R-US_0603-A"))
    )
    (comp (ref "R72")
      (value "10k")
      (footprint "eagle-import:.0603-A")
      (libsource (lib "eagle-import") (part "R-US_0603-A"))
    )
    (comp (ref "TP41")
      (value "TEST-POINT")
      (footprint "eagle-import:2MM-TEST-POINT")
      (libsource (lib "eagle-import") (part "TEST-POINT"))
    )
    (comp (ref "TP42")
      (value "TEST-POINT")
      (footprint "eagle-import:2MM-TEST-POINT")
      (libsource (lib "eagle-import") (part "TEST-POINT"))
    )
    (comp (ref "TP43")
      (value "TEST-POINT")
      (footprint "eagle-import:2MM-TEST-POINT")
      (libsource (lib "eagle-import") (part "TEST-POINT"))
    )
    (comp (ref "TP44")
      (value "TEST-POINT")
      (footprint "eagle-import:2MM-TEST-POINT")
      (libsource (lib "eagle-import") (part "TEST-POINT"))
    )
    (comp (ref "TP45")
      (value "TEST-POINT")
      (footprint "eagle-import:2MM-TEST-POINT")
      (libsource (lib "eagle-import") (part "TEST-POINT"))
    )
    (comp (ref "TP46")
      (value "TEST-POINT")
      (footprint "eagle-import:2MM-TEST-POINT")
      (libsource (lib "eagle-import") (part "TEST-POINT"))
    )
    (comp (ref "TP47")
      (value "TEST-POINT")
      (footprint "eagle-import:2MM-TEST-POINT")
      (libsource (lib "eagle-import") (part "TEST-POINT"))
    )
    (comp (ref "TP48")
      (value "TEST-POINT")
      (footprint "eagle-import:2MM-TEST-POINT")
      (libsource (lib "eagle-import") (part "TEST-POINT"))
    )
    (comp (ref "TP49")
      (value "TEST-POINT")
      (footprint "eagle-import:2MM-TEST-POINT")
      (libsource (lib "eagle-import") (part "TEST-POINT"))
    )
    (comp (ref "TP50")
      (value "TEST-POINT")
      (footprint "eagle-import:2MM-TEST-POINT")
      (libsource (lib "eagle-import") (part "TEST-POINT"))
    )
    (comp (ref "TP51")
      (value "TEST-POINT")
      (footprint "eagle-import:2MM-TEST-POINT")
      (libsource (lib "eagle-import") (part "TEST-POINT"))
    )
    (comp (ref "TP52")
      (value "TEST-POINT")
      (footprint "eagle-import:2MM-TEST-POINT")
      (libsource (lib "eagle-import") (part "TEST-POINT"))
    )
    (comp (ref "TP53")
      (value "TEST-POINT")
      (footprint "eagle-import:2MM-TEST-POINT")
      (libsource (lib "eagle-import") (part "TEST-POINT"))
    )
    (comp (ref "TP54")
      (value "TEST-POINT")
      (footprint "eagle-import:2MM-TEST-POINT")
      (libsource (lib "eagle-import") (part "TEST-POINT"))
    )
    (comp (ref "TP55")
      (value "TEST-POINT")
      (footprint "eagle-import:2MM-TEST-POINT")
      (libsource (lib "eagle-import") (part "TEST-POINT"))
    )
    (comp (ref "TP56")
      (value "TEST-POINT")
      (footprint "eagle-import:2MM-TEST-POINT")
      (libsource (lib "eagle-import") (part "TEST-POINT"))
    )
    (comp (ref "TP57")
      (value "TEST-POINT")
      (footprint "eagle-import:2MM-TEST-POINT")
      (libsource (lib "eagle-import") (part "TEST-POINT"))
    )
    (comp (ref "TP63")
      (value "TEST-POINT")
      (footprint "eagle-import:2MM-TEST-POINT")
      (libsource (lib "eagle-import") (part "TEST-POINT"))
    )
    (comp (ref "TP64")
      (value "TEST-POINT")
      (footprint "eagle-import:2MM-TEST-POINT")
      (libsource (lib "eagle-import") (part "TEST-POINT"))
    )
    (comp (ref "TP65")
      (value "TEST-POINT")
      (footprint "eagle-import:2MM-TEST-POINT")
      (libsource (lib "eagle-import") (part "TEST-POINT"))
    )
    (comp (ref "TP66")
      (value "TEST-POINT")
      (footprint "eagle-import:2MM-TEST-POINT")
      (libsource (lib "eagle-import") (part "TEST-POINT"))
    )
    (comp (ref "TP67")
      (value "TEST-POINT")
      (footprint "eagle-import:2MM-TEST-POINT")
      (libsource (lib "eagle-import") (part "TEST-POINT"))
    )
    (comp (ref "TP68")
      (value "TEST-POINT")
      (footprint "eagle-import:2MM-TEST-POINT")
      (libsource (lib "eagle-import") (part "TEST-POINT"))
    )
    (comp (ref "TP72")
      (value "TEST-POINT")
      (footprint "eagle-import:2MM-TEST-POINT")
      (libsource (lib "eagle-import") (part "TEST-POINT"))
    )
    (comp (ref "TP74")
      (value "TEST-POINT")
      (footprint "eagle-import:2MM-TEST-POINT")
      (libsource (lib "eagle-import") (part "TEST-POINT"))
    )
    (comp (ref "TP75")
      (value "TEST-POINT")
      (footprint "eagle-import:2MM-TEST-POINT")
      (libsource (lib "eagle-import") (part "TEST-POINT"))
    )
    (comp (ref "TP77")
      (value "TEST-POINT")
      (footprint "eagle-import:2MM-TEST-POINT")
      (libsource (lib "eagle-import") (part "TEST-POINT"))
    )
    (comp (ref "TP78")
      (value "TEST-POINT")
      (footprint "eagle-import:2MM-TEST-POINT")
      (libsource (lib "eagle-import") (part "TEST-POINT"))
    )
    (comp (ref "U12")
      (value "MIC842LYC5")
      (footprint "eagle-import:SC70-5")
      (libsource (lib "eagle-import") (part "MIC842LYC5"))
    )
    (comp (ref "U13")
      (value "MIC842LYC5")
      (footprint "eagle-import:SC70-5")
      (libsource (lib "eagle-import") (part "MIC842LYC5"))
    )
    (comp (ref "U14")
      (value "MAX4211FETE")
      (footprint "eagle-import:QFN65P400X400X80-17T210")
      (fields (field (name "MPN") "MAX4211FETE+"))
      (libsource (lib "eagle-import") (part "MAX4211"))
    )
    (comp (ref "U15")
      (value "TPS62112")
      (footprint "eagle-import:S-PVQFN-16")
      (fields (field (name "MPN") "TPS62112RSAR"))
      (libsource (lib "eagle-import") (part "TPS6211X"))
    )
    (comp (ref "U16")
      (value "MAX7310ATE")
      (footprint "eagle-import:QFN65P400X400X80-17T210")
      (fields
        (field (name "MPN") "MAX7310ATE+")
        (field (name "MFR") "Maxim")
        (field (name "MPN_1") "MAX7310ATE")
      )
      (libsource (lib "eagle-import") (part "MAX7310"))
    )
    (comp (ref "C4")
      (value "0.1uF")
      (footprint "eagle-import:.0603-A")
      (libsource (lib "eagle-import") (part "C-EU0603-A"))
    )
    (comp (ref "J1")
      (value "ORESAT-DEBUG-CONNECTOR-ALL")
      (footprint "eagle-import:TE_2-1734592-0")
      (fields (field (name "MPN") "2-1734592-0"))
      (libsource (lib "eagle-import") (part "ORESAT-DEBUG-CONNECTOR-ALL"))
    )
    (comp (ref "J2")
      (value "J-SAMTEC-TFM-110-X1-XXX-D-RA")
      (footprint "eagle-import:J-SAMTEC-TFM-110-X1-XXX-D-RA")
      (fields (field (name "MFR") "Samtec") (field (name "MPN") "TFM-110-01-L-D-RA "))
      (libsource (lib "eagle-import") (part "J-SAMTEC-TFM-110-X1-XXX-D-RA"))
    )
    (comp (ref "J4")
      (value "TFM-120-01-L-D-RA")
      (footprint "eagle-import:J-SAMTEC-TFM-120-X1-XXX-D-RA")
      (libsource (lib "eagle-import") (part "J-SAMTEC-TFM-120-X1-XXX-D-RA"))
    )
    (comp (ref "PCB1")
      (value "ORESAT-CARD-V1.3-GENERIC-0RF")
      (footprint "eagle-import:ORESAT-CARD-V1.3-GENERIC-0RF")
      (libsource (lib "eagle-import") (part "ORESAT-CARD-V1.3-GENERIC-0RF"))
    )
    (comp (ref "TP183")
      (value "TEST-POINT3X4")
      (footprint "eagle-import:PAD.03X.04")
      (libsource (lib "eagle-import") (part "TEST-POINT3X4"))
    )
    (comp (ref "TP184")
      (value "TEST-POINT3X4")
      (footprint "eagle-import:PAD.03X.04")
      (libsource (lib "eagle-import") (part "TEST-POINT3X4"))
    )
    (comp (ref "U$1")
      (value "FLIGHMARKERNEW")
      (footprint "eagle-import:FLIGHTMARKER_NEW_BOARDS")
      (libsource (lib "eagle-import") (part "FLIGHMARKERNEW"))
    )
    (comp (ref "U1")
      (value "RCLAMP0504FB")
      (footprint "eagle-import:SC70-6")
      (fields (field (name "MPN") "RCLAMP0504FBTCT"))
      (libsource (lib "eagle-import") (part "RCLAMP0504FB"))
    )
    (comp (ref "C13")
      (value "22uF")
      (footprint "eagle-import:C1210")
      (libsource (lib "eagle-import") (part "C-EUC1210"))
    )
    (comp (ref "C14")
      (value "22uF")
      (footprint "eagle-import:C1210")
      (libsource (lib "eagle-import") (part "C-EUC1210"))
    )
    (comp (ref "C18")
      (value "0.1uF")
      (footprint "eagle-import:.0603-A")
      (libsource (lib "eagle-import") (part "C-EU0603-A"))
    )
    (comp (ref "D1")
      (value "GREEN")
      (footprint "eagle-import:LED-0603")
      (libsource (lib "eagle-import") (part "LED-GREEN0603"))
    )
    (comp (ref "Q1")
      (value "MMBT2907")
      (footprint "eagle-import:SOT23-BEC")
      (fields (field (name "MPN") "MMBT2907A-7-F"))
      (libsource (lib "eagle-import") (part "MMBT2907SMD"))
    )
    (comp (ref "R1")
      (value "1k")
      (footprint "eagle-import:.0603-A")
      (libsource (lib "eagle-import") (part "R-US_0603-A"))
    )
    (comp (ref "R15")
      (value "10k")
      (footprint "eagle-import:.0603-A")
      (libsource (lib "eagle-import") (part "R-US_0603-A"))
    )
    (comp (ref "R23")
      (value "499")
      (footprint "eagle-import:.0603-A")
      (libsource (lib "eagle-import") (part "R-US_0603-A"))
    )
    (comp (ref "R28")
      (value "10k")
      (footprint "eagle-import:.0603-A")
      (libsource (lib "eagle-import") (part "R-US_0603-A"))
    )
    (comp (ref "R31")
      (value "40.2K")
      (footprint "eagle-import:.0603-A")
      (libsource (lib "eagle-import") (part "R-US_0603-A"))
    )
    (comp (ref "R73")
      (value "100")
      (footprint "eagle-import:.0603-A")
      (libsource (lib "eagle-import") (part "R-US_0603-A"))
    )
    (comp (ref "R74")
      (value "100")
      (footprint "eagle-import:.0603-A")
      (libsource (lib "eagle-import") (part "R-US_0603-A"))
    )
    (comp (ref "R75")
      (value "100")
      (footprint "eagle-import:.0603-A")
      (libsource (lib "eagle-import") (part "R-US_0603-A"))
    )
    (comp (ref "TP2")
      (value "TEST-POINT")
      (footprint "eagle-import:2MM-TEST-POINT")
      (libsource (lib "eagle-import") (part "TEST-POINT"))
    )
    (comp (ref "TP3")
      (value "TEST-POINT3X4")
      (footprint "eagle-import:PAD.03X.04")
      (libsource (lib "eagle-import") (part "TEST-POINT3X4"))
    )
    (comp (ref "TP14")
      (value "TEST-POINT3X4")
      (footprint "eagle-import:PAD.03X.04")
      (libsource (lib "eagle-import") (part "TEST-POINT3X4"))
    )
    (comp (ref "TP39")
      (value "TEST-POINT")
      (footprint "eagle-import:2MM-TEST-POINT")
      (libsource (lib "eagle-import") (part "TEST-POINT"))
    )
    (comp (ref "TP70")
      (value "TEST-POINT")
      (footprint "eagle-import:2MM-TEST-POINT")
      (libsource (lib "eagle-import") (part "TEST-POINT"))
    )
    (comp (ref "TP71")
      (value "TEST-POINT")
      (footprint "eagle-import:2MM-TEST-POINT")
      (libsource (lib "eagle-import") (part "TEST-POINT"))
    )
    (comp (ref "TP102")
      (value "TEST-POINT3X4")
      (footprint "eagle-import:PAD.03X.04")
      (libsource (lib "eagle-import") (part "TEST-POINT3X4"))
    )
    (comp (ref "TP109")
      (value "TEST-POINT3X4")
      (footprint "eagle-import:PAD.03X.04")
      (libsource (lib "eagle-import") (part "TEST-POINT3X4"))
    )
    (comp (ref "TP110")
      (value "TEST-POINT3X4")
      (footprint "eagle-import:PAD.03X.04")
      (libsource (lib "eagle-import") (part "TEST-POINT3X4"))
    )
    (comp (ref "TP121")
      (value "TEST-POINT3X4")
      (footprint "eagle-import:PAD.03X.04")
      (libsource (lib "eagle-import") (part "TEST-POINT3X4"))
    )
    (comp (ref "TP129")
      (value "TEST-POINT3X4")
      (footprint "eagle-import:PAD.03X.04")
      (libsource (lib "eagle-import") (part "TEST-POINT3X4"))
    )
    (comp (ref "TP130")
      (value "TEST-POINT3X4")
      (footprint "eagle-import:PAD.03X.04")
      (libsource (lib "eagle-import") (part "TEST-POINT3X4"))
    )
    (comp (ref "TP132")
      (value "TEST-POINT3X4")
      (footprint "eagle-import:PAD.03X.04")
      (libsource (lib "eagle-import") (part "TEST-POINT3X4"))
    )
    (comp (ref "TP136")
      (value "TEST-POINT3X4")
      (footprint "eagle-import:PAD.03X.04")
      (libsource (lib "eagle-import") (part "TEST-POINT3X4"))
    )
    (comp (ref "TP140")
      (value "TEST-POINT3X4")
      (footprint "eagle-import:PAD.03X.04")
      (libsource (lib "eagle-import") (part "TEST-POINT3X4"))
    )
    (comp (ref "TP154")
      (value "TEST-POINT3X4")
      (footprint "eagle-import:PAD.03X.04")
      (libsource (lib "eagle-import") (part "TEST-POINT3X4"))
    )
    (comp (ref "TP156")
      (value "TEST-POINT3X4")
      (footprint "eagle-import:PAD.03X.04")
      (libsource (lib "eagle-import") (part "TEST-POINT3X4"))
    )
    (comp (ref "TP157")
      (value "TEST-POINT3X4")
      (footprint "eagle-import:PAD.03X.04")
      (libsource (lib "eagle-import") (part "TEST-POINT3X4"))
    )
    (comp (ref "TP160")
      (value "TEST-POINT3X4")
      (footprint "eagle-import:PAD.03X.04")
      (libsource (lib "eagle-import") (part "TEST-POINT3X4"))
    )
    (comp (ref "TP161")
      (value "TEST-POINT3X4")
      (footprint "eagle-import:PAD.03X.04")
      (libsource (lib "eagle-import") (part "TEST-POINT3X4"))
    )
    (comp (ref "TP163")
      (value "TEST-POINT3X4")
      (footprint "eagle-import:PAD.03X.04")
      (libsource (lib "eagle-import") (part "TEST-POINT3X4"))
    )
    (comp (ref "TP164")
      (value "TEST-POINT3X4")
      (footprint "eagle-import:PAD.03X.04")
      (libsource (lib "eagle-import") (part "TEST-POINT3X4"))
    )
    (comp (ref "TP165")
      (value "TEST-POINT3X4")
      (footprint "eagle-import:PAD.03X.04")
      (libsource (lib "eagle-import") (part "TEST-POINT3X4"))
    )
    (comp (ref "TP166")
      (value "TEST-POINT3X4")
      (footprint "eagle-import:PAD.03X.04")
      (libsource (lib "eagle-import") (part "TEST-POINT3X4"))
    )
    (comp (ref "TP167")
      (value "TEST-POINT3X4")
      (footprint "eagle-import:PAD.03X.04")
      (libsource (lib "eagle-import") (part "TEST-POINT3X4"))
    )
    (comp (ref "TP173")
      (value "TEST-POINT3X4")
      (footprint "eagle-import:PAD.03X.04")
      (libsource (lib "eagle-import") (part "TEST-POINT3X4"))
    )
    (comp (ref "U4")
      (value "SN74LVC1G07DCK")
      (footprint "eagle-import:C70(TI-DCK)")
      (fields (field (name "MPN") "SN74LVC1G07DCKR"))
      (libsource (lib "eagle-import") (part "SN74LVC1G07DCK"))
    )
    (comp (ref "U7")
      (value "OSD3358-512M-BSM")
      (footprint "eagle-import:OSD335X-BGA-256")
      (fields (field (name "MFR") "Octavo Systems"))
      (libsource (lib "eagle-import") (part "OSD3358-512M-BSM"))
    )
    (comp (ref "U10")
      (value "TLVH431")
      (footprint "eagle-import:SOT23-3")
      (fields (field (name "MPN") "TLVH431BQDBZRQ1"))
      (libsource (lib "eagle-import") (part "TLVH431"))
    )
    (comp (ref "C19")
      (value "18pF, 50V")
      (footprint "eagle-import:.0603-A")
      (libsource (lib "eagle-import") (part "C-EU0603-A"))
    )
    (comp (ref "C22")
      (value "18pF, 50V")
      (footprint "eagle-import:.0603-A")
      (libsource (lib "eagle-import") (part "C-EU0603-A"))
    )
    (comp (ref "C29")
      (value "18pF, 50V")
      (footprint "eagle-import:.0603-A")
      (libsource (lib "eagle-import") (part "C-EU0603-A"))
    )
    (comp (ref "C30")
      (value "18pF, 50V")
      (footprint "eagle-import:.0603-A")
      (libsource (lib "eagle-import") (part "C-EU0603-A"))
    )
    (comp (ref "C50")
      (value "0.1uF")
      (footprint "eagle-import:.0603-A")
      (libsource (lib "eagle-import") (part "C-EU0603-A"))
    )
    (comp (ref "C51")
      (value "0.1u")
      (footprint "eagle-import:.0603-A")
      (libsource (lib "eagle-import") (part "C-EU0603-A"))
    )
    (comp (ref "FB2")
      (value "30Ω/1.8A")
      (footprint "eagle-import:0603")
      (fields (field (name "MPN") "BLM18KG300JH1D"))
      (libsource (lib "eagle-import") (part "FERRITE_BEAD-0603"))
    )
    (comp (ref "R13")
      (value "1M")
      (footprint "eagle-import:.0603-A")
      (libsource (lib "eagle-import") (part "R-US_0603-A"))
    )
    (comp (ref "R21")
      (value "10k")
      (footprint "eagle-import:.0603-A")
      (libsource (lib "eagle-import") (part "R-US_0603-A"))
    )
    (comp (ref "R27")
      (value "DNP")
      (footprint "eagle-import:.0603-A")
      (libsource (lib "eagle-import") (part "R-US_0603-A"))
    )
    (comp (ref "TP5")
      (value "TEST-POINT3X4")
      (footprint "eagle-import:PAD.03X.04")
      (libsource (lib "eagle-import") (part "TEST-POINT3X4"))
    )
    (comp (ref "TP6")
      (value "TEST-POINT3X4")
      (footprint "eagle-import:PAD.03X.04")
      (libsource (lib "eagle-import") (part "TEST-POINT3X4"))
    )
    (comp (ref "TP7")
      (value "TEST-POINT3X4")
      (footprint "eagle-import:PAD.03X.04")
      (libsource (lib "eagle-import") (part "TEST-POINT3X4"))
    )
    (comp (ref "TP8")
      (value "TEST-POINT3X4")
      (footprint "eagle-import:PAD.03X.04")
      (libsource (lib "eagle-import") (part "TEST-POINT3X4"))
    )
    (comp (ref "TP9")
      (value "TEST-POINT3X4")
      (footprint "eagle-import:PAD.03X.04")
      (libsource (lib "eagle-import") (part "TEST-POINT3X4"))
    )
    (comp (ref "TP10")
      (value "TEST-POINT3X4")
      (footprint "eagle-import:PAD.03X.04")
      (libsource (lib "eagle-import") (part "TEST-POINT3X4"))
    )
    (comp (ref "TP11")
      (value "TEST-POINT3X4")
      (footprint "eagle-import:PAD.03X.04")
      (libsource (lib "eagle-import") (part "TEST-POINT3X4"))
    )
    (comp (ref "TP12")
      (value "TEST-POINT3X4")
      (footprint "eagle-import:PAD.03X.04")
      (libsource (lib "eagle-import") (part "TEST-POINT3X4"))
    )
    (comp (ref "TP15")
      (value "TEST-POINT3X4")
      (footprint "eagle-import:PAD.03X.04")
      (libsource (lib "eagle-import") (part "TEST-POINT3X4"))
    )
    (comp (ref "TP16")
      (value "TEST-POINT3X4")
      (footprint "eagle-import:PAD.03X.04")
      (libsource (lib "eagle-import") (part "TEST-POINT3X4"))
    )
    (comp (ref "TP17")
      (value "TEST-POINT3X4")
      (footprint "eagle-import:PAD.03X.04")
      (libsource (lib "eagle-import") (part "TEST-POINT3X4"))
    )
    (comp (ref "TP36")
      (value "TEST-POINT3X4")
      (footprint "eagle-import:PAD.03X.04")
      (libsource (lib "eagle-import") (part "TEST-POINT3X4"))
    )
    (comp (ref "TP37")
      (value "TEST-POINT3X4")
      (footprint "eagle-import:PAD.03X.04")
      (libsource (lib "eagle-import") (part "TEST-POINT3X4"))
    )
    (comp (ref "TP38")
      (value "TEST-POINT3X4")
      (footprint "eagle-import:PAD.03X.04")
      (libsource (lib "eagle-import") (part "TEST-POINT3X4"))
    )
    (comp (ref "TP133")
      (value "TEST-POINT3X4")
      (footprint "eagle-import:PAD.03X.04")
      (libsource (lib "eagle-import") (part "TEST-POINT3X4"))
    )
    (comp (ref "TP138")
      (value "TEST-POINT3X4")
      (footprint "eagle-import:PAD.03X.04")
      (libsource (lib "eagle-import") (part "TEST-POINT3X4"))
    )
    (comp (ref "TP139")
      (value "TEST-POINT3X4")
      (footprint "eagle-import:PAD.03X.04")
      (libsource (lib "eagle-import") (part "TEST-POINT3X4"))
    )
    (comp (ref "TP141")
      (value "TEST-POINT3X4")
      (footprint "eagle-import:PAD.03X.04")
      (libsource (lib "eagle-import") (part "TEST-POINT3X4"))
    )
    (comp (ref "TP144")
      (value "TEST-POINT3X4")
      (footprint "eagle-import:PAD.03X.04")
      (libsource (lib "eagle-import") (part "TEST-POINT3X4"))
    )
    (comp (ref "TP168")
      (value "TEST-POINT3X4")
      (footprint "eagle-import:PAD.03X.04")
      (libsource (lib "eagle-import") (part "TEST-POINT3X4"))
    )
    (comp (ref "Y1")
      (value "24MHz")
      (footprint "eagle-import:5X3.2-4SMD")
      (fields (field (name "MPN") "ECS-240-12-30BQ-AEN-TR"))
      (libsource (lib "eagle-import") (part "ECS-240-12-30BQ-AEN-TR"))
    )
    (comp (ref "Y2")
      (value "ABS07-32.768KHZ-T")
      (footprint "eagle-import:CRYSTAL_3.2X1.5")
      (libsource (lib "eagle-import") (part "ABS07-32.768KHZ-T"))
    )
    (comp (ref "C1")
      (value "1n")
      (footprint "eagle-import:.0402-C-NOSILK")
      (fields (field (name "MFR") "Murata") (field (name "MPN") "GRM155R71H102KA01J"))
      (libsource (lib "eagle-import") (part "C-EU0402-C-NOSILK"))
    )
    (comp (ref "C2")
      (value "10uF")
      (footprint "eagle-import:.0805-B")
      (libsource (lib "eagle-import") (part "C-EU0805-B"))
    )
    (comp (ref "C3")
      (value "1uF")
      (footprint "eagle-import:.0603-A")
      (libsource (lib "eagle-import") (part "C-EU0603-A"))
    )
    (comp (ref "C5")
      (value "1uF")
      (footprint "eagle-import:.0603-A")
      (libsource (lib "eagle-import") (part "C-EU0603-A"))
    )
    (comp (ref "C6")
      (value "1uF")
      (footprint "eagle-import:.0603-A")
      (libsource (lib "eagle-import") (part "C-EU0603-A"))
    )
    (comp (ref "C7")
      (value "1n")
      (footprint "eagle-import:.0402-C-NOSILK")
      (fields (field (name "MFR") "Murata") (field (name "MPN") "GRM155R71H102KA01J"))
      (libsource (lib "eagle-import") (part "C-EU0402-C-NOSILK"))
    )
    (comp (ref "C8")
      (value "10uF")
      (footprint "eagle-import:.0805-B")
      (libsource (lib "eagle-import") (part "C-EU0805-B"))
    )
    (comp (ref "C9")
      (value "1uF")
      (footprint "eagle-import:.0603-A")
      (libsource (lib "eagle-import") (part "C-EU0603-A"))
    )
    (comp (ref "C10")
      (value "1uF")
      (footprint "eagle-import:.0603-A")
      (libsource (lib "eagle-import") (part "C-EU0603-A"))
    )
    (comp (ref "C11")
      (value "0.1uF")
      (footprint "eagle-import:.0603-A")
      (libsource (lib "eagle-import") (part "C-EU0603-A"))
    )
    (comp (ref "C12")
      (value "1uF")
      (footprint "eagle-import:.0603-A")
      (libsource (lib "eagle-import") (part "C-EU0603-A"))
    )
    (comp (ref "C16")
      (value "1n")
      (footprint "eagle-import:.0402-C-NOSILK")
      (fields (field (name "MFR") "Murata") (field (name "MPN") "GRM155R71H102KA01J"))
      (libsource (lib "eagle-import") (part "C-EU0402-C-NOSILK"))
    )
    (comp (ref "C17")
      (value "1n")
      (footprint "eagle-import:.0402-C-NOSILK")
      (fields (field (name "MFR") "Murata") (field (name "MPN") "GRM155R71H102KA01J"))
      (libsource (lib "eagle-import") (part "C-EU0402-C-NOSILK"))
    )
    (comp (ref "C20")
      (value "1n")
      (footprint "eagle-import:.0402-C-NOSILK")
      (fields (field (name "MFR") "Murata") (field (name "MPN") "GRM155R71H102KA01J"))
      (libsource (lib "eagle-import") (part "C-EU0402-C-NOSILK"))
    )
    (comp (ref "C21")
      (value "10n")
      (footprint "eagle-import:.0402-C-NOSILK")
      (fields (field (name "MFR") "Kemet") (field (name "MPN") "C0603C103M5RACTU"))
      (libsource (lib "eagle-import") (part "C-EU0402-C-NOSILK"))
    )
    (comp (ref "C23")
      (value "10n")
      (footprint "eagle-import:.0402-C-NOSILK")
      (fields (field (name "MFR") "Kemet") (field (name "MPN") "C0603C103M5RACTU"))
      (libsource (lib "eagle-import") (part "C-EU0402-C-NOSILK"))
    )
    (comp (ref "C24")
      (value "10n")
      (footprint "eagle-import:.0402-C-NOSILK")
      (fields (field (name "MFR") "Kemet") (field (name "MPN") "C0603C103M5RACTU"))
      (libsource (lib "eagle-import") (part "C-EU0402-C-NOSILK"))
    )
    (comp (ref "C25")
      (value "10n")
      (footprint "eagle-import:.0402-C-NOSILK")
      (fields (field (name "MFR") "Kemet") (field (name "MPN") "C0603C103M5RACTU"))
      (libsource (lib "eagle-import") (part "C-EU0402-C-NOSILK"))
    )
    (comp (ref "C26")
      (value "10n")
      (footprint "eagle-import:.0402-C-NOSILK")
      (fields (field (name "MFR") "Kemet") (field (name "MPN") "C0603C103M5RACTU"))
      (libsource (lib "eagle-import") (part "C-EU0402-C-NOSILK"))
    )
    (comp (ref "C27")
      (value "10n")
      (footprint "eagle-import:.0402-C-NOSILK")
      (fields (field (name "MFR") "Kemet") (field (name "MPN") "C0603C103M5RACTU"))
      (libsource (lib "eagle-import") (part "C-EU0402-C-NOSILK"))
    )
    (comp (ref "C28")
      (value "1n")
      (footprint "eagle-import:.0402-C-NOSILK")
      (fields (field (name "MFR") "Murata") (field (name "MPN") "GRM155R71H102KA01J"))
      (libsource (lib "eagle-import") (part "C-EU0402-C-NOSILK"))
    )
    (comp (ref "C31")
      (value "0.1uF")
      (footprint "eagle-import:.0603-A")
      (libsource (lib "eagle-import") (part "C-EU0603-A"))
    )
    (comp (ref "C40")
      (value "DNP")
      (footprint "eagle-import:.0603-A")
      (libsource (lib "eagle-import") (part "C-EU0603-A"))
    )
    (comp (ref "C42")
      (value "100n")
      (footprint "eagle-import:.0402-C-NOSILK")
      (fields (field (name "MFR") "Kemet") (field (name "MPN") "C0805C104Z5VACTU"))
      (libsource (lib "eagle-import") (part "C-EU0402-C-NOSILK"))
    )
    (comp (ref "C43")
      (value "100n")
      (footprint "eagle-import:.0402-C-NOSILK")
      (fields (field (name "MFR") "Kemet") (field (name "MPN") "C0805C104Z5VACTU"))
      (libsource (lib "eagle-import") (part "C-EU0402-C-NOSILK"))
    )
    (comp (ref "C45")
      (value "100n")
      (footprint "eagle-import:.0402-C-NOSILK")
      (fields (field (name "MFR") "Kemet") (field (name "MPN") "C0805C104Z5VACTU"))
      (libsource (lib "eagle-import") (part "C-EU0402-C-NOSILK"))
    )
    (comp (ref "C46")
      (value "100n")
      (footprint "eagle-import:.0402-C-NOSILK")
      (fields (field (name "MFR") "Kemet") (field (name "MPN") "C0805C104Z5VACTU"))
      (libsource (lib "eagle-import") (part "C-EU0402-C-NOSILK"))
    )
    (comp (ref "C47")
      (value "100n")
      (footprint "eagle-import:.0402-C-NOSILK")
      (fields (field (name "MFR") "Kemet") (field (name "MPN") "C0805C104Z5VACTU"))
      (libsource (lib "eagle-import") (part "C-EU0402-C-NOSILK"))
    )
    (comp (ref "C48")
      (value "100n")
      (footprint "eagle-import:.0402-C-NOSILK")
      (fields (field (name "MFR") "Kemet") (field (name "MPN") "C0805C104Z5VACTU"))
      (libsource (lib "eagle-import") (part "C-EU0402-C-NOSILK"))
    )
    (comp (ref "C49")
      (value "10u")
      (footprint "eagle-import:.0603-C-NOSILK")
      (fields (field (name "MFR") "Murata") (field (name "MPN") "GRM188R61A106KE69J"))
      (libsource (lib "eagle-import") (part "C-EU0603-C-NOSILK"))
    )
    (comp (ref "D2")
      (value "BLUE")
      (footprint "eagle-import:LED-0603")
      (libsource (lib "eagle-import") (part "LED-BLUE0603"))
    )
    (comp (ref "D3")
      (value "BLUE")
      (footprint "eagle-import:LED-0603")
      (libsource (lib "eagle-import") (part "LED-BLUE0603"))
    )
    (comp (ref "D4")
      (value "BLUE")
      (footprint "eagle-import:LED-0603")
      (libsource (lib "eagle-import") (part "LED-BLUE0603"))
    )
    (comp (ref "D5")
      (value "BLUE")
      (footprint "eagle-import:LED-0603")
      (libsource (lib "eagle-import") (part "LED-BLUE0603"))
    )
    (comp (ref "J3")
      (value "CONN_03LONGPADS")
      (footprint "eagle-import:1X03_LONGPADS")
      (libsource (lib "eagle-import") (part "CONN_03LONGPADS"))
    )
    (comp (ref "J100")
      (value "DM3BT-DSF-PEJS")
      (footprint "eagle-import:DM3BT-DSF-PEJS")
      (libsource (lib "eagle-import") (part "DM3BT-DSF-PEJS"))
    )
    (comp (ref "JP1")
      (value "JUMPER-SMT_2_NC_TRACE_SILK")
      (footprint "eagle-import:SMT-JUMPER_2_NC_TRACE_SILK")
      (libsource (lib "eagle-import") (part "JUMPER-SMT_2_NC_TRACE_SILK"))
    )
    (comp (ref "JP2")
      (value "JUMPER-SMT_3_1-NC_TRACE_SILK")
      (footprint "eagle-import:SMT-JUMPER_3_1-NC_TRACE_SILK")
      (libsource (lib "eagle-import") (part "JUMPER-SMT_3_1-NC_TRACE_SILK"))
    )
    (comp (ref "R2")
      (value "1k")
      (footprint "eagle-import:.0603-A")
      (libsource (lib "eagle-import") (part "R-US_0603-A"))
    )
    (comp (ref "R3")
      (value "1k")
      (footprint "eagle-import:.0603-A")
      (libsource (lib "eagle-import") (part "R-US_0603-A"))
    )
    (comp (ref "R4")
      (value "1k")
      (footprint "eagle-import:.0603-A")
      (libsource (lib "eagle-import") (part "R-US_0603-A"))
    )
    (comp (ref "R5")
      (value "1k")
      (footprint "eagle-import:.0603-A")
      (libsource (lib "eagle-import") (part "R-US_0603-A"))
    )
    (comp (ref "R6")
      (value "100")
      (footprint "eagle-import:.0402-C-NOSILK")
      (fields (field (name "MFR") "Yageo") (field (name "MPN") "RC0201FR-07100RL"))
      (libsource (lib "eagle-import") (part "R-US_0402-C-NOSILK"))
    )
    (comp (ref "R7")
      (value "100")
      (footprint "eagle-import:.0402-C-NOSILK")
      (fields (field (name "MFR") "Yageo") (field (name "MPN") "RC0201FR-07100RL"))
      (libsource (lib "eagle-import") (part "R-US_0402-C-NOSILK"))
    )
    (comp (ref "R8")
      (value "10K")
      (footprint "eagle-import:ARRAY_EXBA-M")
      (fields (field (name "MFR") "Panasonic Electronic Components"))
      (libsource (lib "eagle-import") (part "EXB-A10P391JC_ARRAY_EXBA-M"))
    )
    (comp (ref "R9")
      (value "10K")
      (footprint "eagle-import:ARRAY_EXBA-M")
      (fields (field (name "MFR") "Panasonic Electronic Components"))
      (libsource (lib "eagle-import") (part "EXB-A10P391JC_ARRAY_EXBA-M"))
    )
    (comp (ref "R10")
      (value "10K")
      (footprint "eagle-import:ARRAY_EXBA-M")
      (fields (field (name "MFR") "Panasonic Electronic Components") (field (name "DPN") "U7103CT-ND"))
      (libsource (lib "eagle-import") (part "EXB-A10P391JC_ARRAY_EXBA-M"))
    )
    (comp (ref "R11")
      (value "DNP")
      (footprint "eagle-import:.0603-A")
      (libsource (lib "eagle-import") (part "R-US_0603-A"))
    )
    (comp (ref "R14")
      (value "DNP")
      (footprint "eagle-import:.0603-A")
      (libsource (lib "eagle-import") (part "R-US_0603-A"))
    )
    (comp (ref "R16")
      (value "100k")
      (footprint "eagle-import:RES_EXB2HV")
      (fields (field (name "MPN") "EXB-2HV103JV"))
      (libsource (lib "eagle-import") (part "EXB-2HV103JV"))
    )
    (comp (ref "R17")
      (value "100k")
      (footprint "eagle-import:RES_EXB2HV")
      (fields (field (name "MPN") "EXB-2HV103JV"))
      (libsource (lib "eagle-import") (part "EXB-2HV103JV"))
    )
    (comp (ref "R29")
      (value "NP")
      (footprint "eagle-import:.0402-C-NOSILK")
      (fields (field (name "MFR") "Yageo") (field (name "MPN") "RC0201FR-07100RL"))
      (libsource (lib "eagle-import") (part "R-US_0402-C-NOSILK"))
    )
    (comp (ref "R30")
      (value "NP")
      (footprint "eagle-import:.0402-C-NOSILK")
      (fields (field (name "MFR") "Yageo") (field (name "MPN") "RC0201FR-07100RL"))
      (libsource (lib "eagle-import") (part "R-US_0402-C-NOSILK"))
    )
    (comp (ref "R59")
      (value "DNP")
      (footprint "eagle-import:.0603-A")
      (libsource (lib "eagle-import") (part "R-US_0603-A"))
    )
    (comp (ref "R60")
      (value "DNP")
      (footprint "eagle-import:.0603-A")
      (libsource (lib "eagle-import") (part "R-US_0603-A"))
    )
    (comp (ref "SB0")
      (value "TEST-POINT-SMALL")
      (footprint "eagle-import:TEST-POINT-SMALL")
      (libsource (lib "eagle-import") (part "TEST-POINT-SMALL"))
    )
    (comp (ref "SB1")
      (value "TEST-POINT-SMALL")
      (footprint "eagle-import:TEST-POINT-SMALL")
      (libsource (lib "eagle-import") (part "TEST-POINT-SMALL"))
    )
    (comp (ref "SB2")
      (value "TEST-POINT-SMALL")
      (footprint "eagle-import:TEST-POINT-SMALL")
      (libsource (lib "eagle-import") (part "TEST-POINT-SMALL"))
    )
    (comp (ref "SB3")
      (value "TEST-POINT-SMALL")
      (footprint "eagle-import:TEST-POINT-SMALL")
      (libsource (lib "eagle-import") (part "TEST-POINT-SMALL"))
    )
    (comp (ref "SB4")
      (value "TEST-POINT-SMALL")
      (footprint "eagle-import:TEST-POINT-SMALL")
      (libsource (lib "eagle-import") (part "TEST-POINT-SMALL"))
    )
    (comp (ref "SB5")
      (value "TEST-POINT-SMALL")
      (footprint "eagle-import:TEST-POINT-SMALL")
      (libsource (lib "eagle-import") (part "TEST-POINT-SMALL"))
    )
    (comp (ref "SB6")
      (value "TEST-POINT-SMALL")
      (footprint "eagle-import:TEST-POINT-SMALL")
      (libsource (lib "eagle-import") (part "TEST-POINT-SMALL"))
    )
    (comp (ref "SB7")
      (value "TEST-POINT-SMALL")
      (footprint "eagle-import:TEST-POINT-SMALL")
      (libsource (lib "eagle-import") (part "TEST-POINT-SMALL"))
    )
    (comp (ref "SB8")
      (value "TEST-POINT-SMALL")
      (footprint "eagle-import:TEST-POINT-SMALL")
      (libsource (lib "eagle-import") (part "TEST-POINT-SMALL"))
    )
    (comp (ref "SB9")
      (value "TEST-POINT-SMALL")
      (footprint "eagle-import:TEST-POINT-SMALL")
      (libsource (lib "eagle-import") (part "TEST-POINT-SMALL"))
    )
    (comp (ref "SB10")
      (value "TEST-POINT-SMALL")
      (footprint "eagle-import:TEST-POINT-SMALL")
      (libsource (lib "eagle-import") (part "TEST-POINT-SMALL"))
    )
    (comp (ref "SB11")
      (value "TEST-POINT-SMALL")
      (footprint "eagle-import:TEST-POINT-SMALL")
      (libsource (lib "eagle-import") (part "TEST-POINT-SMALL"))
    )
    (comp (ref "SB12")
      (value "TEST-POINT-SMALL")
      (footprint "eagle-import:TEST-POINT-SMALL")
      (libsource (lib "eagle-import") (part "TEST-POINT-SMALL"))
    )
    (comp (ref "SB13")
      (value "TEST-POINT-SMALL")
      (footprint "eagle-import:TEST-POINT-SMALL")
      (libsource (lib "eagle-import") (part "TEST-POINT-SMALL"))
    )
    (comp (ref "SB14")
      (value "TEST-POINT-SMALL")
      (footprint "eagle-import:TEST-POINT-SMALL")
      (libsource (lib "eagle-import") (part "TEST-POINT-SMALL"))
    )
    (comp (ref "SB15")
      (value "TEST-POINT-SMALL")
      (footprint "eagle-import:TEST-POINT-SMALL")
      (libsource (lib "eagle-import") (part "TEST-POINT-SMALL"))
    )
    (comp (ref "TP1")
      (value "TEST-POINT")
      (footprint "eagle-import:2MM-TEST-POINT")
      (libsource (lib "eagle-import") (part "TEST-POINT"))
    )
    (comp (ref "TP4")
      (value "TEST-POINT3X4")
      (footprint "eagle-import:PAD.03X.04")
      (libsource (lib "eagle-import") (part "TEST-POINT3X4"))
    )
    (comp (ref "TP13")
      (value "TEST-POINT3X4")
      (footprint "eagle-import:PAD.03X.04")
      (libsource (lib "eagle-import") (part "TEST-POINT3X4"))
    )
    (comp (ref "TP18")
      (value "TEST-POINT")
      (footprint "eagle-import:2MM-TEST-POINT")
      (libsource (lib "eagle-import") (part "TEST-POINT"))
    )
    (comp (ref "TP19")
      (value "TEST-POINT")
      (footprint "eagle-import:2MM-TEST-POINT")
      (libsource (lib "eagle-import") (part "TEST-POINT"))
    )
    (comp (ref "TP20")
      (value "TEST-POINT")
      (footprint "eagle-import:2MM-TEST-POINT")
      (libsource (lib "eagle-import") (part "TEST-POINT"))
    )
    (comp (ref "TP21")
      (value "TEST-POINT")
      (footprint "eagle-import:2MM-TEST-POINT")
      (libsource (lib "eagle-import") (part "TEST-POINT"))
    )
    (comp (ref "TP22")
      (value "TEST-POINT3X4")
      (footprint "eagle-import:PAD.03X.04")
      (libsource (lib "eagle-import") (part "TEST-POINT3X4"))
    )
    (comp (ref "TP23")
      (value "TEST-POINT")
      (footprint "eagle-import:2MM-TEST-POINT")
      (libsource (lib "eagle-import") (part "TEST-POINT"))
    )
    (comp (ref "TP24")
      (value "TEST-POINT")
      (footprint "eagle-import:2MM-TEST-POINT")
      (libsource (lib "eagle-import") (part "TEST-POINT"))
    )
    (comp (ref "TP26")
      (value "TEST-POINT")
      (footprint "eagle-import:2MM-TEST-POINT")
      (libsource (lib "eagle-import") (part "TEST-POINT"))
    )
    (comp (ref "TP27")
      (value "TEST-POINT")
      (footprint "eagle-import:2MM-TEST-POINT")
      (libsource (lib "eagle-import") (part "TEST-POINT"))
    )
    (comp (ref "TP28")
      (value "TEST-POINT")
      (footprint "eagle-import:2MM-TEST-POINT")
      (libsource (lib "eagle-import") (part "TEST-POINT"))
    )
    (comp (ref "TP29")
      (value "TEST-POINT")
      (footprint "eagle-import:2MM-TEST-POINT")
      (libsource (lib "eagle-import") (part "TEST-POINT"))
    )
    (comp (ref "TP30")
      (value "TEST-POINT")
      (footprint "eagle-import:2MM-TEST-POINT")
      (libsource (lib "eagle-import") (part "TEST-POINT"))
    )
    (comp (ref "TP31")
      (value "TEST-POINT")
      (footprint "eagle-import:2MM-TEST-POINT")
      (libsource (lib "eagle-import") (part "TEST-POINT"))
    )
    (comp (ref "TP32")
      (value "TEST-POINT")
      (footprint "eagle-import:2MM-TEST-POINT")
      (libsource (lib "eagle-import") (part "TEST-POINT"))
    )
    (comp (ref "TP33")
      (value "TEST-POINT")
      (footprint "eagle-import:2MM-TEST-POINT")
      (libsource (lib "eagle-import") (part "TEST-POINT"))
    )
    (comp (ref "TP34")
      (value "TEST-POINT")
      (footprint "eagle-import:2MM-TEST-POINT")
      (libsource (lib "eagle-import") (part "TEST-POINT"))
    )
    (comp (ref "TP35")
      (value "TEST-POINT3X4")
      (footprint "eagle-import:PAD.03X.04")
      (libsource (lib "eagle-import") (part "TEST-POINT3X4"))
    )
    (comp (ref "TP40")
      (value "TEST-POINT3X4")
      (footprint "eagle-import:PAD.03X.04")
      (libsource (lib "eagle-import") (part "TEST-POINT3X4"))
    )
    (comp (ref "TP69")
      (value "TEST-POINT3X4")
      (footprint "eagle-import:PAD.03X.04")
      (libsource (lib "eagle-import") (part "TEST-POINT3X4"))
    )
    (comp (ref "U2")
      (value "DS90CR218AMTD/NOPBMTD48_TEX-L")
      (footprint "eagle-import:MTD48_TEX-L")
      (fields (field (name "MFR") "Texas Instruments") (field (name "MPN") "DS90CR218AMTD/NOPB"))
      (libsource (lib "eagle-import") (part "DS90CR218AMTD/NOPBMTD48_TEX-L"))
    )
    (comp (ref "U3")
      (value "THGBMJG7C2LBAU8")
      (footprint "eagle-import:BGA-153(11.5X13)(EMMC-BA)")
      (libsource (lib "eagle-import") (part "EMMC+RESET+5.1-COMPATIBLE-BA"))
    )
    (comp (ref "U11")
      (value "TCAN330")
      (footprint "eagle-import:SOT23-8_TI-DCN")
      (fields (field (name "MPN") "TCAN330GDCNT"))
      (libsource (lib "eagle-import") (part "TCAN330"))
    )
    (comp (ref "U17")
      (value "25AAXX")
      (footprint "eagle-import:SOIC8")
      (fields (field (name "MPN") "25AA02E48T-I/SN"))
      (libsource (lib "eagle-import") (part "25AAXX"))
    )
  )
  (nets
    (net (code "5") (name "1.8V-A") (class "Default")
      (node (ref "C50") (pin "1") (pinfunction "1_1") (pintype "passive"))
      (node (ref "R21") (pin "2") (pinfunction "2_2") (pintype "passive"))
      (node (ref "U7") (pin "A7") (pinfunction "SYS_ADC_1P8V_A7") (pintype "bidirectional"))
      (node (ref "U7") (pin "B7") (pinfunction "VREFP_B7") (pintype "bidirectional"))
    )
    (net (code "6") (name "3.3V") (class "Default")
      (node (ref "C1") (pin "1") (pinfunction "1_1") (pintype "passive"))
      (node (ref "C11") (pin "1") (pinfunction "1_1") (pintype "passive"))
      (node (ref "C16") (pin "1") (pinfunction "1_1") (pintype "passive"))
      (node (ref "C17") (pin "1") (pinfunction "1_1") (pintype "passive"))
      (node (ref "C2") (pin "1") (pinfunction "1_1") (pintype "passive"))
      (node (ref "C20") (pin "1") (pinfunction "1_1") (pintype "passive"))
      (node (ref "C21") (pin "1") (pinfunction "1_1") (pintype "passive"))
      (node (ref "C23") (pin "1") (pinfunction "1_1") (pintype "passive"))
      (node (ref "C24") (pin "1") (pinfunction "1_1") (pintype "passive"))
      (node (ref "C25") (pin "1") (pinfunction "1_1") (pintype "passive"))
      (node (ref "C26") (pin "1") (pinfunction "1_1") (pintype "passive"))
      (node (ref "C27") (pin "1") (pinfunction "1_1") (pintype "passive"))
      (node (ref "C28") (pin "1") (pinfunction "1_1") (pintype "passive"))
      (node (ref "C3") (pin "1") (pinfunction "1_1") (pintype "passive"))
      (node (ref "C31") (pin "2") (pinfunction "2_2") (pintype "passive"))
      (node (ref "C40") (pin "2") (pinfunction "2_2") (pintype "passive"))
      (node (ref "C42") (pin "1") (pinfunction "1_1") (pintype "passive"))
      (node (ref "C43") (pin "1") (pinfunction "1_1") (pintype "passive"))
      (node (ref "C45") (pin "1") (pinfunction "1_1") (pintype "passive"))
      (node (ref "C46") (pin "1") (pinfunction "1_1") (pintype "passive"))
      (node (ref "C47") (pin "1") (pinfunction "1_1") (pintype "passive"))
      (node (ref "C48") (pin "1") (pinfunction "1_1") (pintype "passive"))
      (node (ref "C49") (pin "1") (pinfunction "1_1") (pintype "passive"))
      (node (ref "C5") (pin "1") (pinfunction "1_1") (pintype "passive"))
      (node (ref "C6") (pin "1") (pinfunction "1_1") (pintype "passive"))
      (node (ref "C7") (pin "1") (pinfunction "1_1") (pintype "passive"))
      (node (ref "C8") (pin "1") (pinfunction "1_1") (pintype "passive"))
      (node (ref "C9") (pin "1") (pinfunction "1_1") (pintype "passive"))
      (node (ref "J100") (pin "4") (pinfunction "VDD_4") (pintype "bidirectional"))
      (node (ref "J3") (pin "1") (pinfunction "1_1") (pintype "passive"))
      (node (ref "JP1") (pin "1") (pinfunction "1_1") (pintype "passive"))
      (node (ref "R1") (pin "1") (pinfunction "1_1") (pintype "passive"))
      (node (ref "R10") (pin "10") (pinfunction "55_10") (pintype "passive"))
      (node (ref "R10") (pin "5") (pinfunction "55_5") (pintype "passive"))
      (node (ref "R17") (pin "5") (pinfunction "5_5") (pintype "passive"))
      (node (ref "R17") (pin "6") (pinfunction "6_6") (pintype "passive"))
      (node (ref "R17") (pin "7") (pinfunction "7_7") (pintype "passive"))
      (node (ref "R17") (pin "8") (pinfunction "8_8") (pintype "passive"))
      (node (ref "R60") (pin "1") (pinfunction "1_1") (pintype "passive"))
      (node (ref "R8") (pin "10") (pinfunction "55_10") (pintype "passive"))
      (node (ref "R8") (pin "5") (pinfunction "55_5") (pintype "passive"))
      (node (ref "R9") (pin "10") (pinfunction "55_10") (pintype "passive"))
      (node (ref "R9") (pin "5") (pinfunction "55_5") (pintype "passive"))
      (node (ref "TP2") (pin "1") (pinfunction "1_1") (pintype "passive"))
      (node (ref "U11") (pin "3") (pinfunction "VCC_3") (pintype "power_in"))
      (node (ref "U17") (pin "8") (pinfunction "VCC_8") (pintype "power_in"))
      (node (ref "U2") (pin "12") (pinfunction "LVDS_VCC_12") (pintype "power_in"))
      (node (ref "U2") (pin "20") (pinfunction "PLL_VCC_20") (pintype "power_in"))
      (node (ref "U2") (pin "28") (pinfunction "VCC_2_28") (pintype "power_in"))
      (node (ref "U2") (pin "36") (pinfunction "VCC_3_36") (pintype "power_in"))
      (node (ref "U2") (pin "42") (pinfunction "VCC_4_42") (pintype "power_in"))
      (node (ref "U2") (pin "48") (pinfunction "VCC_48") (pintype "power_in"))
      (node (ref "U3") (pin "C6") (pinfunction "VDDQ_C6") (pintype "power_in"))
      (node (ref "U3") (pin "E6") (pinfunction "VDDIO_E6") (pintype "power_in"))
      (node (ref "U3") (pin "F5") (pinfunction "VDDIO_F5") (pintype "power_in"))
      (node (ref "U3") (pin "J10") (pinfunction "VDDIO_J10") (pintype "power_in"))
      (node (ref "U3") (pin "K9") (pinfunction "VDDIO_K9") (pintype "power_in"))
      (node (ref "U3") (pin "M4") (pinfunction "VDDQ_M4") (pintype "power_in"))
      (node (ref "U3") (pin "N4") (pinfunction "VDDQ_N4") (pintype "power_in"))
      (node (ref "U3") (pin "P3") (pinfunction "VDDQ_P3") (pintype "power_in"))
      (node (ref "U3") (pin "P5") (pinfunction "VDDQ_P5") (pintype "power_in"))
      (node (ref "U7") (pin "F6") (pinfunction "SYS_VDD1_3P3V_F6") (pintype "power_in"))
      (node (ref "U7") (pin "F7") (pinfunction "SYS_VDD1_3P3V_F7") (pintype "power_in"))
      (node (ref "U7") (pin "G6") (pinfunction "SYS_VDD1_3P3V_G6") (pintype "power_in"))
      (node (ref "U7") (pin "G7") (pinfunction "SYS_VDD1_3P3V_G7") (pintype "power_in"))
    )
    (net (code "7") (name "3.3VA") (class "Default")
      (node (ref "Q1") (pin "E") (pinfunction "E_E") (pintype "passive"))
      (node (ref "R23") (pin "2") (pinfunction "2_2") (pintype "passive"))
      (node (ref "R28") (pin "2") (pinfunction "2_2") (pintype "passive"))
      (node (ref "TP165") (pin "P$1") (pinfunction "1_P$1") (pintype "bidirectional"))
      (node (ref "U7") (pin "F8") (pinfunction "SYS_VDD3_3P3V_F8") (pintype "power_in"))
      (node (ref "U7") (pin "F9") (pinfunction "VDDSHV4_F9") (pintype "power_in"))
      (node (ref "U7") (pin "G8") (pinfunction "SYS_VDD3_3P3V_G8") (pintype "power_in"))
      (node (ref "U7") (pin "G9") (pinfunction "VDDSHV5_G9") (pintype "power_in"))
      (node (ref "U7") (pin "H7") (pinfunction "SYS_VDD3_3P3V_H7") (pintype "power_in"))
      (node (ref "U7") (pin "H8") (pinfunction "SYS_VDD3_3P3V_H8") (pintype "power_in"))
      (node (ref "U7") (pin "H9") (pinfunction "VDDSHV6_H9") (pintype "power_in"))
      (node (ref "U7") (pin "J7") (pinfunction "SYS_VDD3_3P3V_J7") (pintype "power_in"))
      (node (ref "U7") (pin "J8") (pinfunction "SYS_VDD3_3P3V_J8") (pintype "power_in"))
      (node (ref "U7") (pin "J9") (pinfunction "VDDSHV1_J9") (pintype "power_in"))
      (node (ref "U7") (pin "K8") (pinfunction "SYS_VDD3_3P3V_K8") (pintype "power_in"))
      (node (ref "U7") (pin "K9") (pinfunction "VDDSHV2_K9") (pintype "power_in"))
      (node (ref "U7") (pin "L8") (pinfunction "SYS_VDD3_3P3V_L8") (pintype "power_in"))
      (node (ref "U7") (pin "L9") (pinfunction "VDDSHV3_L9") (pintype "power_in"))
    )
    (net (code "8") (name "5V") (class "Default")
      (node (ref "C14") (pin "1") (pinfunction "1_1") (pintype "passive"))
      (node (ref "C36") (pin "1") (pinfunction "1_1") (pintype "passive"))
      (node (ref "L1") (pin "2") (pinfunction "2_2") (pintype "passive"))
      (node (ref "R62") (pin "2") (pinfunction "2_2") (pintype "passive"))
      (node (ref "TP49") (pin "1") (pinfunction "1_1") (pintype "passive"))
      (node (ref "U15") (pin "10") (pinfunction "FB_10") (pintype "input"))
      (node (ref "U7") (pin "P10") (pinfunction "VIN_AC_P10") (pintype "power_in"))
      (node (ref "U7") (pin "R10") (pinfunction "VIN_AC_R10") (pintype "power_in"))
      (node (ref "U7") (pin "T10") (pinfunction "VIN_AC_T10") (pintype "power_in"))
    )
    (net (code "9") (name "AD0") (class "Default")
      (node (ref "R57") (pin "1") (pinfunction "1_1") (pintype "passive"))
      (node (ref "R58") (pin "2") (pinfunction "2_2") (pintype "passive"))
      (node (ref "R69") (pin "2") (pinfunction "2_2") (pintype "passive"))
      (node (ref "R70") (pin "1") (pinfunction "1_1") (pintype "passive"))
      (node (ref "U16") (pin "1") (pinfunction "AD0_1") (pintype "input"))
    )
    (net (code "10") (name "AD1") (class "Default")
      (node (ref "R55") (pin "1") (pinfunction "1_1") (pintype "passive"))
      (node (ref "R56") (pin "2") (pinfunction "2_2") (pintype "passive"))
      (node (ref "R67") (pin "2") (pinfunction "2_2") (pintype "passive"))
      (node (ref "R68") (pin "1") (pinfunction "1_1") (pintype "passive"))
      (node (ref "U16") (pin "2") (pinfunction "AD1_2") (pintype "input"))
    )
    (net (code "11") (name "AD2") (class "Default")
      (node (ref "R53") (pin "1") (pinfunction "1_1") (pintype "passive"))
      (node (ref "R54") (pin "2") (pinfunction "2_2") (pintype "passive"))
      (node (ref "R65") (pin "2") (pinfunction "2_2") (pintype "passive"))
      (node (ref "R66") (pin "1") (pinfunction "1_1") (pintype "passive"))
      (node (ref "U16") (pin "3") (pinfunction "AD2_3") (pintype "input"))
    )
    (net (code "12") (name "BOOT0") (class "Default")
      (node (ref "JP3") (pin "1") (pinfunction "1_1") (pintype "passive"))
      (node (ref "TP51") (pin "1") (pinfunction "1_1") (pintype "passive"))
      (node (ref "U16") (pin "10") (pinfunction "IO5_10") (pintype "bidirectional"))
    )
    (net (code "13") (name "CAN1_H") (class "Default")
      (node (ref "J4") (pin "33") (pinfunction "33_33") (pintype "passive"))
      (node (ref "J4") (pin "34") (pinfunction "34_34") (pintype "passive"))
      (node (ref "TP184") (pin "P$1") (pinfunction "1_P$1") (pintype "bidirectional"))
    )
    (net (code "14") (name "CAN1_L") (class "Default")
      (node (ref "J4") (pin "35") (pinfunction "35_35") (pintype "passive"))
      (node (ref "J4") (pin "36") (pinfunction "36_36") (pintype "passive"))
      (node (ref "TP183") (pin "P$1") (pinfunction "1_P$1") (pintype "bidirectional"))
    )
    (net (code "15") (name "CAN2_H") (class "Default")
      (node (ref "J4") (pin "17") (pinfunction "17_17") (pintype "passive"))
      (node (ref "J4") (pin "18") (pinfunction "18_18") (pintype "passive"))
      (node (ref "U11") (pin "7") (pinfunction "CANH_7") (pintype "bidirectional"))
    )
    (net (code "16") (name "CAN2_L") (class "Default")
      (node (ref "J4") (pin "19") (pinfunction "19_19") (pintype "passive"))
      (node (ref "J4") (pin "20") (pinfunction "20_20") (pintype "passive"))
      (node (ref "U11") (pin "6") (pinfunction "CANL_6") (pintype "bidirectional"))
    )
    (net (code "17") (name "CB-RESET") (class "Default")
      (node (ref "R39") (pin "2") (pinfunction "2_2") (pintype "passive"))
      (node (ref "TP54") (pin "1") (pinfunction "1_1") (pintype "passive"))
      (node (ref "U14") (pin "9") (pinfunction "CIN2-_9") (pintype "input"))
      (node (ref "U16") (pin "9") (pinfunction "IO4_9") (pintype "bidirectional"))
    )
    (net (code "18") (name "CB_CTRL") (class "Default")
      (node (ref "Q2") (pin "1") (pinfunction "G_1") (pintype "passive"))
      (node (ref "Q5") (pin "3") (pinfunction "G_3") (pintype "passive"))
      (node (ref "R64") (pin "1") (pinfunction "1_1") (pintype "passive"))
      (node (ref "TP52") (pin "1") (pinfunction "1_1") (pintype "passive"))
      (node (ref "U14") (pin "3") (pinfunction "LE_3") (pintype "input"))
      (node (ref "U14") (pin "4") (pinfunction "COUT1_4") (pintype "open_collector"))
      (node (ref "U14") (pin "6") (pinfunction "COUT2_6") (pintype "open_collector"))
    )
    (net (code "19") (name "EEPROM_WP") (class "Default")
      (node (ref "J1") (pin "20") (pinfunction "DEBUG-3_20") (pintype "passive"))
      (node (ref "R75") (pin "1") (pinfunction "1_1") (pintype "passive"))
      (node (ref "TP71") (pin "1") (pinfunction "1_1") (pintype "passive"))
    )
    (net (code "20") (name "GND") (class "Default")
      (node (ref "C1") (pin "2") (pinfunction "2_2") (pintype "passive"))
      (node (ref "C10") (pin "2") (pinfunction "2_2") (pintype "passive"))
      (node (ref "C11") (pin "2") (pinfunction "2_2") (pintype "passive"))
      (node (ref "C12") (pin "2") (pinfunction "2_2") (pintype "passive"))
      (node (ref "C13") (pin "2") (pinfunction "2_2") (pintype "passive"))
      (node (ref "C14") (pin "2") (pinfunction "2_2") (pintype "passive"))
      (node (ref "C16") (pin "2") (pinfunction "2_2") (pintype "passive"))
      (node (ref "C17") (pin "2") (pinfunction "2_2") (pintype "passive"))
      (node (ref "C18") (pin "2") (pinfunction "2_2") (pintype "passive"))
      (node (ref "C2") (pin "2") (pinfunction "2_2") (pintype "passive"))
      (node (ref "C20") (pin "2") (pinfunction "2_2") (pintype "passive"))
      (node (ref "C21") (pin "2") (pinfunction "2_2") (pintype "passive"))
      (node (ref "C23") (pin "2") (pinfunction "2_2") (pintype "passive"))
      (node (ref "C24") (pin "2") (pinfunction "2_2") (pintype "passive"))
      (node (ref "C25") (pin "2") (pinfunction "2_2") (pintype "passive"))
      (node (ref "C26") (pin "2") (pinfunction "2_2") (pintype "passive"))
      (node (ref "C27") (pin "2") (pinfunction "2_2") (pintype "passive"))
      (node (ref "C28") (pin "2") (pinfunction "2_2") (pintype "passive"))
      (node (ref "C3") (pin "2") (pinfunction "2_2") (pintype "passive"))
      (node (ref "C31") (pin "1") (pinfunction "1_1") (pintype "passive"))
      (node (ref "C32") (pin "2") (pinfunction "2_2") (pintype "passive"))
      (node (ref "C34") (pin "2") (pinfunction "2_2") (pintype "passive"))
      (node (ref "C35") (pin "2") (pinfunction "2_2") (pintype "passive"))
      (node (ref "C36") (pin "2") (pinfunction "2_2") (pintype "passive"))
      (node (ref "C37") (pin "2") (pinfunction "2_2") (pintype "passive"))
      (node (ref "C38") (pin "2") (pinfunction "2_2") (pintype "passive"))
      (node (ref "C39") (pin "1") (pinfunction "1_1") (pintype "passive"))
      (node (ref "C4") (pin "2") (pinfunction "2_2") (pintype "passive"))
      (node (ref "C40") (pin "1") (pinfunction "1_1") (pintype "passive"))
      (node (ref "C42") (pin "2") (pinfunction "2_2") (pintype "passive"))
      (node (ref "C43") (pin "2") (pinfunction "2_2") (pintype "passive"))
      (node (ref "C44") (pin "2") (pinfunction "2_2") (pintype "passive"))
      (node (ref "C45") (pin "2") (pinfunction "2_2") (pintype "passive"))
      (node (ref "C46") (pin "2") (pinfunction "2_2") (pintype "passive"))
      (node (ref "C47") (pin "2") (pinfunction "2_2") (pintype "passive"))
      (node (ref "C48") (pin "2") (pinfunction "2_2") (pintype "passive"))
      (node (ref "C49") (pin "2") (pinfunction "2_2") (pintype "passive"))
      (node (ref "C5") (pin "2") (pinfunction "2_2") (pintype "passive"))
      (node (ref "C50") (pin "2") (pinfunction "2_2") (pintype "passive"))
      (node (ref "C51") (pin "2") (pinfunction "2_2") (pintype "passive"))
      (node (ref "C6") (pin "2") (pinfunction "2_2") (pintype "passive"))
      (node (ref "C7") (pin "2") (pinfunction "2_2") (pintype "passive"))
      (node (ref "C8") (pin "2") (pinfunction "2_2") (pintype "passive"))
      (node (ref "C9") (pin "2") (pinfunction "2_2") (pintype "passive"))
      (node (ref "D1") (pin "C") (pinfunction "C_C") (pintype "passive"))
      (node (ref "D2") (pin "C") (pinfunction "C_C") (pintype "passive"))
      (node (ref "D3") (pin "C") (pinfunction "C_C") (pintype "passive"))
      (node (ref "D4") (pin "C") (pinfunction "C_C") (pintype "passive"))
      (node (ref "D5") (pin "C") (pinfunction "C_C") (pintype "passive"))
      (node (ref "D6") (pin "C") (pinfunction "C_C") (pintype "passive"))
      (node (ref "D7") (pin "C") (pinfunction "C_C") (pintype "passive"))
      (node (ref "D8") (pin "C") (pinfunction "C_C") (pintype "passive"))
      (node (ref "J1") (pin "3") (pinfunction "GND_3") (pintype "passive"))
      (node (ref "J1") (pin "6") (pinfunction "GND_6") (pintype "passive"))
      (node (ref "J1") (pin "9") (pinfunction "GND_9") (pintype "passive"))
      (node (ref "J1") (pin "PAD1") (pinfunction "PAD_PAD1") (pintype "bidirectional"))
      (node (ref "J1") (pin "PAD2") (pinfunction "PAD_PAD2") (pintype "bidirectional"))
      (node (ref "J100") (pin "6") (pinfunction "VSS_6") (pintype "bidirectional"))
      (node (ref "J100") (pin "CGND1") (pinfunction "CGND_CGND1") (pintype "bidirectional"))
      (node (ref "J100") (pin "CGND2") (pinfunction "CGND_CGND2") (pintype "bidirectional"))
      (node (ref "J100") (pin "CGND3") (pinfunction "CGND_CGND3") (pintype "bidirectional"))
      (node (ref "J100") (pin "CGND4") (pinfunction "CGND_CGND4") (pintype "bidirectional"))
      (node (ref "J100") (pin "CGND5") (pinfunction "CGND_CGND5") (pintype "bidirectional"))
      (node (ref "J100") (pin "CGND6") (pinfunction "CGND_CGND6") (pintype "bidirectional"))
      (node (ref "J100") (pin "GND") (pinfunction "VSS_GND") (pintype "bidirectional"))
      (node (ref "J3") (pin "3") (pinfunction "3_3") (pintype "passive"))
      (node (ref "J4") (pin "27") (pinfunction "27_27") (pintype "passive"))
      (node (ref "J4") (pin "28") (pinfunction "28_28") (pintype "passive"))
      (node (ref "J4") (pin "29") (pinfunction "29_29") (pintype "passive"))
      (node (ref "J4") (pin "30") (pinfunction "30_30") (pintype "passive"))
      (node (ref "J4") (pin "31") (pinfunction "31_31") (pintype "passive"))
      (node (ref "J4") (pin "32") (pinfunction "32_32") (pintype "passive"))
      (node (ref "J4") (pin "37") (pinfunction "37_37") (pintype "passive"))
      (node (ref "J4") (pin "38") (pinfunction "38_38") (pintype "passive"))
      (node (ref "Q2") (pin "2") (pinfunction "S_2") (pintype "passive"))
      (node (ref "Q4") (pin "2") (pinfunction "S_2") (pintype "passive"))
      (node (ref "R11") (pin "1") (pinfunction "1_1") (pintype "passive"))
      (node (ref "R14") (pin "1") (pinfunction "1_1") (pintype "passive"))
      (node (ref "R15") (pin "1") (pinfunction "1_1") (pintype "passive"))
      (node (ref "R16") (pin "1") (pinfunction "1_1") (pintype "passive"))
      (node (ref "R16") (pin "2") (pinfunction "2_2") (pintype "passive"))
      (node (ref "R16") (pin "3") (pinfunction "3_3") (pintype "passive"))
      (node (ref "R16") (pin "4") (pinfunction "4_4") (pintype "passive"))
      (node (ref "R16") (pin "5") (pinfunction "5_5") (pintype "passive"))
      (node (ref "R16") (pin "6") (pinfunction "6_6") (pintype "passive"))
      (node (ref "R16") (pin "7") (pinfunction "7_7") (pintype "passive"))
      (node (ref "R16") (pin "8") (pinfunction "8_8") (pintype "passive"))
      (node (ref "R17") (pin "1") (pinfunction "1_1") (pintype "passive"))
      (node (ref "R17") (pin "2") (pinfunction "2_2") (pintype "passive"))
      (node (ref "R17") (pin "3") (pinfunction "3_3") (pintype "passive"))
      (node (ref "R17") (pin "4") (pinfunction "4_4") (pintype "passive"))
      (node (ref "R33") (pin "1") (pinfunction "1_1") (pintype "passive"))
      (node (ref "R39") (pin "1") (pinfunction "1_1") (pintype "passive"))
      (node (ref "R40") (pin "1") (pinfunction "1_1") (pintype "passive"))
      (node (ref "R42") (pin "1") (pinfunction "1_1") (pintype "passive"))
      (node (ref "R46") (pin "1") (pinfunction "1_1") (pintype "passive"))
      (node (ref "R51") (pin "1") (pinfunction "1_1") (pintype "passive"))
      (node (ref "R54") (pin "1") (pinfunction "1_1") (pintype "passive"))
      (node (ref "R56") (pin "1") (pinfunction "1_1") (pintype "passive"))
      (node (ref "R58") (pin "1") (pinfunction "1_1") (pintype "passive"))
      (node (ref "R59") (pin "2") (pinfunction "2_2") (pintype "passive"))
      (node (ref "TP72") (pin "1") (pinfunction "1_1") (pintype "passive"))
      (node (ref "TP74") (pin "1") (pinfunction "1_1") (pintype "passive"))
      (node (ref "TP75") (pin "1") (pinfunction "1_1") (pintype "passive"))
      (node (ref "TP77") (pin "1") (pinfunction "1_1") (pintype "passive"))
      (node (ref "TP78") (pin "1") (pinfunction "1_1") (pintype "passive"))
      (node (ref "U1") (pin "2") (pinfunction "GND_2") (pintype "power_in"))
      (node (ref "U11") (pin "2") (pinfunction "GND_2") (pintype "power_in"))
      (node (ref "U12") (pin "2") (pinfunction "GND_2") (pintype "power_in"))
      (node (ref "U13") (pin "2") (pinfunction "GND_2") (pintype "power_in"))
      (node (ref "U14") (pin "7") (pinfunction "GND_7") (pintype "power_in"))
      (node (ref "U14") (pin "EPAD") (pinfunction "GND_EPAD") (pintype "power_in"))
      (node (ref "U15") (pin "1") (pinfunction "GND_1") (pintype "power_in"))
      (node (ref "U15") (pin "11") (pinfunction "GND_11") (pintype "power_in"))
      (node (ref "U15") (pin "12") (pinfunction "GND_12") (pintype "power_in"))
      (node (ref "U15") (pin "16") (pinfunction "GND_16") (pintype "power_in"))
      (node (ref "U15") (pin "6") (pinfunction "LBO_6") (pintype "open_collector"))
      (node (ref "U15") (pin "7") (pinfunction "LBI_7") (pintype "input"))
      (node (ref "U15") (pin "9") (pinfunction "GND_9") (pintype "power_in"))
      (node (ref "U15") (pin "PAD") (pinfunction "GND_PAD") (pintype "power_in"))
      (node (ref "U16") (pin "6") (pinfunction "GND_6") (pintype "power_in"))
      (node (ref "U16") (pin "EPAD") (pinfunction "GND_EPAD") (pintype "power_in"))
      (node (ref "U17") (pin "4") (pinfunction "GND_4") (pintype "power_in"))
      (node (ref "U2") (pin "13") (pinfunction "GND_13") (pintype "power_in"))
      (node (ref "U2") (pin "18") (pinfunction "GND_18") (pintype "power_in"))
      (node (ref "U2") (pin "19") (pinfunction "GND_19") (pintype "power_in"))
      (node (ref "U2") (pin "21") (pinfunction "GND_21") (pintype "power_in"))
      (node (ref "U2") (pin "25") (pinfunction "GND_25") (pintype "power_in"))
      (node (ref "U2") (pin "3") (pinfunction "GND_3") (pintype "power_in"))
      (node (ref "U2") (pin "32") (pinfunction "GND_32") (pintype "power_in"))
      (node (ref "U2") (pin "38") (pinfunction "GND_38") (pintype "power_in"))
      (node (ref "U2") (pin "44") (pinfunction "GND_44") (pintype "power_in"))
      (node (ref "U2") (pin "7") (pinfunction "GND_7") (pintype "power_in"))
      (node (ref "U3") (pin "A6") (pinfunction "VSSIO_A6") (pintype "power_in"))
      (node (ref "U3") (pin "C4") (pinfunction "VSSQ_C4") (pintype "power_in"))
      (node (ref "U3") (pin "E7") (pinfunction "VSSIO_E7") (pintype "power_in"))
      (node (ref "U3") (pin "G5") (pinfunction "VSSIO_G5") (pintype "power_in"))
      (node (ref "U3") (pin "H10") (pinfunction "VSSIO_H10") (pintype "power_in"))
      (node (ref "U3") (pin "J5") (pinfunction "VSSIO_J5") (pintype "power_in"))
      (node (ref "U3") (pin "K8") (pinfunction "VSSIO_K8") (pintype "power_in"))
      (node (ref "U3") (pin "N2") (pinfunction "VSSQ_N2") (pintype "power_in"))
      (node (ref "U3") (pin "N5") (pinfunction "VSSQ_N5") (pintype "power_in"))
      (node (ref "U3") (pin "P4") (pinfunction "VSSQ_P4") (pintype "power_in"))
      (node (ref "U3") (pin "P6") (pinfunction "VSSQ_P6") (pintype "power_in"))
      (node (ref "U4") (pin "3") (pinfunction "GND_3") (pintype "bidirectional"))
      (node (ref "U7") (pin "A9") (pinfunction "AGND_ADC_A9") (pintype "bidirectional"))
      (node (ref "U7") (pin "B9") (pinfunction "VREFN_B9") (pintype "bidirectional"))
      (node (ref "U7") (pin "D8") (pinfunction "DGND_D8") (pintype "bidirectional"))
      (node (ref "U7") (pin "D9") (pinfunction "DGND_D9") (pintype "bidirectional"))
      (node (ref "U7") (pin "E10") (pinfunction "DGND_E10") (pintype "bidirectional"))
      (node (ref "U7") (pin "E11") (pinfunction "DGND_E11") (pintype "bidirectional"))
      (node (ref "U7") (pin "E12") (pinfunction "DGND_E12") (pintype "bidirectional"))
      (node (ref "U7") (pin "E5") (pinfunction "DGND_E5") (pintype "bidirectional"))
      (node (ref "U7") (pin "E6") (pinfunction "DGND_E6") (pintype "bidirectional"))
      (node (ref "U7") (pin "E7") (pinfunction "DGND_E7") (pintype "bidirectional"))
      (node (ref "U7") (pin "E8") (pinfunction "DGND_E8") (pintype "bidirectional"))
      (node (ref "U7") (pin "E9") (pinfunction "DGND_E9") (pintype "bidirectional"))
      (node (ref "U7") (pin "F12") (pinfunction "DGND_F12") (pintype "bidirectional"))
      (node (ref "U7") (pin "F5") (pinfunction "DGND_F5") (pintype "bidirectional"))
      (node (ref "U7") (pin "G12") (pinfunction "DGND_G12") (pintype "bidirectional"))
      (node (ref "U7") (pin "G5") (pinfunction "DGND_G5") (pintype "bidirectional"))
      (node (ref "U7") (pin "H12") (pinfunction "DGND_H12") (pintype "bidirectional"))
      (node (ref "U7") (pin "H13") (pinfunction "DGND_H13") (pintype "bidirectional"))
      (node (ref "U7") (pin "H4") (pinfunction "DGND_H4") (pintype "bidirectional"))
      (node (ref "U7") (pin "H5") (pinfunction "DGND_H5") (pintype "bidirectional"))
      (node (ref "U7") (pin "J12") (pinfunction "DGND_J12") (pintype "bidirectional"))
      (node (ref "U7") (pin "J13") (pinfunction "DGND_J13") (pintype "bidirectional"))
      (node (ref "U7") (pin "J4") (pinfunction "DGND_J4") (pintype "bidirectional"))
      (node (ref "U7") (pin "J5") (pinfunction "DGND_J5") (pintype "bidirectional"))
      (node (ref "U7") (pin "K12") (pinfunction "DGND_K12") (pintype "bidirectional"))
      (node (ref "U7") (pin "K5") (pinfunction "DGND_K5") (pintype "bidirectional"))
      (node (ref "U7") (pin "L12") (pinfunction "DGND_L12") (pintype "bidirectional"))
      (node (ref "U7") (pin "L14") (pinfunction "USB1_ID_L14") (pintype "bidirectional"))
      (node (ref "U7") (pin "L5") (pinfunction "DGND_L5") (pintype "bidirectional"))
      (node (ref "U7") (pin "M10") (pinfunction "DGND_M10") (pintype "bidirectional"))
      (node (ref "U7") (pin "M11") (pinfunction "DGND_M11") (pintype "bidirectional"))
      (node (ref "U7") (pin "M12") (pinfunction "DGND_M12") (pintype "bidirectional"))
      (node (ref "U7") (pin "M5") (pinfunction "DGND_M5") (pintype "bidirectional"))
      (node (ref "U7") (pin "M6") (pinfunction "DGND_M6") (pintype "bidirectional"))
      (node (ref "U7") (pin "M7") (pinfunction "DGND_M7") (pintype "bidirectional"))
      (node (ref "U7") (pin "M8") (pinfunction "DGND_M8") (pintype "bidirectional"))
      (node (ref "U7") (pin "M9") (pinfunction "DGND_M9") (pintype "bidirectional"))
      (node (ref "U7") (pin "N8") (pinfunction "DGND_N8") (pintype "bidirectional"))
      (node (ref "U7") (pin "N9") (pinfunction "DGND_N9") (pintype "bidirectional"))
      (node (ref "Y1") (pin "2") (pinfunction "GND_2") (pintype "power_in"))
      (node (ref "Y1") (pin "4") (pinfunction "GND_4") (pintype "power_in"))
    )
    (net (code "21") (name "I2C0_SCL") (class "Default")
      (node (ref "J1") (pin "18") (pinfunction "DEBUG-1_18") (pintype "passive"))
      (node (ref "R73") (pin "1") (pinfunction "1_1") (pintype "passive"))
      (node (ref "TP39") (pin "1") (pinfunction "1_1") (pintype "passive"))
      (node (ref "U1") (pin "6") (pinfunction "I4_6") (pintype "bidirectional"))
    )
    (net (code "22") (name "I2C0_SDA") (class "Default")
      (node (ref "J1") (pin "19") (pinfunction "DEBUG-2_19") (pintype "passive"))
      (node (ref "R74") (pin "1") (pinfunction "1_1") (pintype "passive"))
      (node (ref "TP70") (pin "1") (pinfunction "1_1") (pintype "passive"))
      (node (ref "U1") (pin "4") (pinfunction "I3_4") (pintype "bidirectional"))
    )
    (net (code "23") (name "N$118") (class "Default")
      (node (ref "C18") (pin "1") (pinfunction "1_1") (pintype "passive"))
      (node (ref "Q1") (pin "C") (pinfunction "C_C") (pintype "passive"))
      (node (ref "R31") (pin "1") (pinfunction "1_1") (pintype "passive"))
      (node (ref "TP14") (pin "P$1") (pinfunction "1_P$1") (pintype "bidirectional"))
      (node (ref "TP164") (pin "P$1") (pinfunction "1_P$1") (pintype "bidirectional"))
      (node (ref "U10") (pin "3") (pinfunction "ANODE_3") (pintype "bidirectional"))
      (node (ref "U4") (pin "5") (pinfunction "VCC_5") (pintype "bidirectional"))
      (node (ref "U7") (pin "K11") (pinfunction "SYS_RTC_1P8V_K11") (pintype "power_in"))
      (node (ref "U7") (pin "L11") (pinfunction "SYS_RTC_1P8V_L11") (pintype "power_in"))
    )
    (net (code "24") (name "Net-(C33-Pad1)") (class "Default")
      (node (ref "C33") (pin "1") (pinfunction "1_1") (pintype "passive"))
      (node (ref "R33") (pin "2") (pinfunction "2_2") (pintype "passive"))
      (node (ref "R38") (pin "2") (pinfunction "2_2") (pintype "passive"))
    )
    (net (code "25") (name "Net-(D1-PadA)") (class "Default")
      (node (ref "D1") (pin "A") (pinfunction "A_A") (pintype "passive"))
      (node (ref "R1") (pin "2") (pinfunction "2_2") (pintype "passive"))
    )
    (net (code "26") (name "Net-(D2-PadA)") (class "Default")
      (node (ref "D2") (pin "A") (pinfunction "A_A") (pintype "passive"))
      (node (ref "R2") (pin "2") (pinfunction "2_2") (pintype "passive"))
    )
    (net (code "27") (name "Net-(D3-PadA)") (class "Default")
      (node (ref "D3") (pin "A") (pinfunction "A_A") (pintype "passive"))
      (node (ref "R3") (pin "2") (pinfunction "2_2") (pintype "passive"))
    )
    (net (code "28") (name "Net-(D4-PadA)") (class "Default")
      (node (ref "D4") (pin "A") (pinfunction "A_A") (pintype "passive"))
      (node (ref "R4") (pin "2") (pinfunction "2_2") (pintype "passive"))
    )
    (net (code "29") (name "Net-(D5-PadA)") (class "Default")
      (node (ref "D5") (pin "A") (pinfunction "A_A") (pintype "passive"))
      (node (ref "R5") (pin "2") (pinfunction "2_2") (pintype "passive"))
    )
    (net (code "30") (name "Net-(D6-PadA)") (class "Default")
      (node (ref "D6") (pin "A") (pinfunction "A_A") (pintype "passive"))
      (node (ref "R49") (pin "1") (pinfunction "1_1") (pintype "passive"))
    )
    (net (code "31") (name "Net-(D7-PadA)") (class "Default")
      (node (ref "D7") (pin "A") (pinfunction "A_A") (pintype "passive"))
      (node (ref "R61") (pin "1") (pinfunction "1_1") (pintype "passive"))
    )
    (net (code "32") (name "Net-(D8-PadA)") (class "Default")
      (node (ref "D8") (pin "A") (pinfunction "A_A") (pintype "passive"))
      (node (ref "R62") (pin "1") (pinfunction "1_1") (pintype "passive"))
    )
    (net (code "33") (name "Net-(J4-Pad1)") (class "Default")
      (node (ref "J4") (pin "1") (pinfunction "1_1") (pintype "passive"))
      (node (ref "J4") (pin "2") (pinfunction "2_2") (pintype "passive"))
    )
    (net (code "34") (name "Net-(J4-Pad3)") (class "Default")
      (node (ref "J4") (pin "3") (pinfunction "3_3") (pintype "passive"))
      (node (ref "J4") (pin "4") (pinfunction "4_4") (pintype "passive"))
    )
    (net (code "35") (name "Net-(J4-Pad5)") (class "Default")
      (node (ref "J4") (pin "5") (pinfunction "5_5") (pintype "passive"))
      (node (ref "J4") (pin "6") (pinfunction "6_6") (pintype "passive"))
    )
    (net (code "36") (name "Net-(J4-Pad7)") (class "Default")
      (node (ref "J4") (pin "7") (pinfunction "7_7") (pintype "passive"))
      (node (ref "J4") (pin "8") (pinfunction "8_8") (pintype "passive"))
    )
    (net (code "37") (name "Net-(J4-Pad10)") (class "Default")
      (node (ref "J4") (pin "10") (pinfunction "10_10") (pintype "passive"))
      (node (ref "J4") (pin "9") (pinfunction "9_9") (pintype "passive"))
    )
    (net (code "38") (name "Net-(J100-CD#)") (class "Default")
      (node (ref "J100") (pin "CD") (pinfunction "CD#_CD") (pintype "bidirectional"))
      (node (ref "R8") (pin "6") (pinfunction "66_6") (pintype "passive"))
      (node (ref "TP22") (pin "P$1") (pinfunction "1_P$1") (pintype "bidirectional"))
      (node (ref "U7") (pin "C14") (pinfunction "SPI0_CS1_C14") (pintype "bidirectional"))
    )
    (net (code "39") (name "Net-(J100-CLK)") (class "Default")
      (node (ref "J100") (pin "5") (pinfunction "CLK_5") (pintype "bidirectional"))
      (node (ref "R8") (pin "3") (pinfunction "33_3") (pintype "passive"))
      (node (ref "U7") (pin "B15") (pinfunction "MMC0_CLK_B15") (pintype "bidirectional"))
    )
    (net (code "40") (name "Net-(J100-CMD{slash}DI)") (class "Default")
      (node (ref "J100") (pin "3") (pinfunction "CMD/DI_3") (pintype "bidirectional"))
      (node (ref "R8") (pin "8") (pinfunction "88_8") (pintype "passive"))
      (node (ref "U7") (pin "B16") (pinfunction "MMC0_CMD_B16") (pintype "bidirectional"))
    )
    (net (code "41") (name "Net-(J100-DAT0{slash}DO)") (class "Default")
      (node (ref "J100") (pin "7") (pinfunction "DAT0/DO_7") (pintype "bidirectional"))
      (node (ref "R8") (pin "7") (pinfunction "77_7") (pintype "passive"))
      (node (ref "U7") (pin "A16") (pinfunction "MMC0_DAT0_A16") (pintype "bidirectional"))
    )
    (net (code "42") (name "Net-(J100-DAT1)") (class "Default")
      (node (ref "J100") (pin "8") (pinfunction "DAT1_8") (pintype "bidirectional"))
      (node (ref "R8") (pin "4") (pinfunction "44_4") (pintype "passive"))
      (node (ref "U7") (pin "A15") (pinfunction "MMC0_DAT1_A15") (pintype "bidirectional"))
    )
    (net (code "43") (name "Net-(J100-DAT2)") (class "Default")
      (node (ref "J100") (pin "1") (pinfunction "DAT2_1") (pintype "bidirectional"))
      (node (ref "R8") (pin "9") (pinfunction "99_9") (pintype "passive"))
      (node (ref "U7") (pin "C16") (pinfunction "MMC0_DAT2_C16") (pintype "bidirectional"))
    )
    (net (code "44") (name "Net-(J100-DAT3{slash}CS)") (class "Default")
      (node (ref "J100") (pin "2") (pinfunction "DAT3/CS_2") (pintype "bidirectional"))
      (node (ref "R8") (pin "2") (pinfunction "22_2") (pintype "passive"))
      (node (ref "U7") (pin "C15") (pinfunction "MMC0_DAT3_C15") (pintype "bidirectional"))
    )
    (net (code "45") (name "Net-(JP2-Pad1)") (class "Default")
      (node (ref "JP2") (pin "1") (pinfunction "1_1") (pintype "passive"))
      (node (ref "R14") (pin "2") (pinfunction "2_2") (pintype "passive"))
    )
    (net (code "46") (name "Net-(JP2-Pad3)") (class "Default")
      (node (ref "JP2") (pin "3") (pinfunction "3_3") (pintype "passive"))
      (node (ref "R17") (pin "12") (pinfunction "12_12") (pintype "passive"))
    )
    (net (code "47") (name "Net-(L1-Pad1)") (class "Default")
      (node (ref "L1") (pin "1") (pinfunction "1_1") (pintype "passive"))
      (node (ref "U15") (pin "14") (pinfunction "SW_14") (pintype "output"))
      (node (ref "U15") (pin "15") (pinfunction "SW_15") (pintype "output"))
    )
    (net (code "48") (name "Net-(Q3A-G)") (class "Default")
      (node (ref "Q3") (pin "1") (pinfunction "G_1") (pintype "passive"))
      (node (ref "R35") (pin "2") (pinfunction "2_2") (pintype "passive"))
    )
    (net (code "49") (name "Net-(Q3A-S)") (class "Default")
      (node (ref "Q3") (pin "5") (pinfunction "S_5") (pintype "passive"))
      (node (ref "R48") (pin "2") (pinfunction "2_2") (pintype "passive"))
    )
    (net (code "50") (name "Net-(Q3B-G)") (class "Default")
      (node (ref "Q3") (pin "3") (pinfunction "G_3") (pintype "passive"))
      (node (ref "R43") (pin "2") (pinfunction "2_2") (pintype "passive"))
    )
    (net (code "51") (name "Net-(Q3B-S)") (class "Default")
      (node (ref "Q3") (pin "2") (pinfunction "S_2") (pintype "passive"))
      (node (ref "R41") (pin "2") (pinfunction "2_2") (pintype "passive"))
    )
    (net (code "52") (name "Net-(Q4-D)") (class "Default")
      (node (ref "Q4") (pin "3") (pinfunction "D_3") (pintype "passive"))
      (node (ref "Q6") (pin "3") (pinfunction "G_3") (pintype "passive"))
      (node (ref "R52") (pin "1") (pinfunction "1_1") (pintype "passive"))
    )
    (net (code "53") (name "Net-(Q5-S)") (class "Default")
      (node (ref "Q5") (pin "4") (pinfunction "S_4") (pintype "passive"))
      (node (ref "R63") (pin "2") (pinfunction "2_2") (pintype "passive"))
      (node (ref "R64") (pin "2") (pinfunction "2_2") (pintype "passive"))
      (node (ref "U14") (pin "15") (pinfunction "RS-_15") (pintype "passive"))
    )
    (net (code "54") (name "Net-(R9-22)") (class "Default")
      (node (ref "R9") (pin "2") (pinfunction "22_2") (pintype "passive"))
      (node (ref "U3") (pin "M5") (pinfunction "CMD_M5") (pintype "input"))
      (node (ref "U7") (pin "P1") (pinfunction "GPMC_CSN2_P1") (pintype "bidirectional"))
    )
    (net (code "55") (name "Net-(R9-33)") (class "Default")
      (node (ref "R9") (pin "3") (pinfunction "33_3") (pintype "passive"))
      (node (ref "U3") (pin "K5") (pinfunction "~{RST}_K5") (pintype "input"))
      (node (ref "U7") (pin "R13") (pinfunction "GPMC_A4_R13") (pintype "bidirectional"))
    )
    (net (code "56") (name "Net-(R9-44)") (class "Default")
      (node (ref "R9") (pin "4") (pinfunction "44_4") (pintype "passive"))
      (node (ref "U3") (pin "B2") (pinfunction "D3_B2") (pintype "input"))
      (node (ref "U7") (pin "T3") (pinfunction "GPMC_AD3_T3") (pintype "bidirectional"))
    )
    (net (code "57") (name "Net-(R9-66)") (class "Default")
      (node (ref "R9") (pin "6") (pinfunction "66_6") (pintype "passive"))
      (node (ref "U3") (pin "A3") (pinfunction "D0_A3") (pintype "input"))
      (node (ref "U7") (pin "R3") (pinfunction "GPMC_AD0_R3") (pintype "bidirectional"))
    )
    (net (code "58") (name "Net-(R9-77)") (class "Default")
      (node (ref "R9") (pin "7") (pinfunction "77_7") (pintype "passive"))
      (node (ref "U3") (pin "B3") (pinfunction "D4_B3") (pintype "input"))
      (node (ref "U7") (pin "T2") (pinfunction "GPMC_AD4_T2") (pintype "bidirectional"))
    )
    (net (code "59") (name "Net-(R9-88)") (class "Default")
      (node (ref "R9") (pin "8") (pinfunction "88_8") (pintype "passive"))
      (node (ref "U3") (pin "B4") (pinfunction "D5_B4") (pintype "input"))
      (node (ref "U7") (pin "T1") (pinfunction "GPMC_AD5_T1") (pintype "bidirectional"))
    )
    (net (code "60") (name "Net-(R9-99)") (class "Default")
      (node (ref "R9") (pin "9") (pinfunction "99_9") (pintype "passive"))
      (node (ref "U3") (pin "M6") (pinfunction "SCK_M6") (pintype "input"))
      (node (ref "U7") (pin "P2") (pinfunction "GPMC_CSN1_P2") (pintype "bidirectional"))
    )
    (net (code "61") (name "Net-(R10-11)") (class "Default")
      (node (ref "R10") (pin "1") (pinfunction "11_1") (pintype "passive"))
      (node (ref "U3") (pin "A4") (pinfunction "D1_A4") (pintype "input"))
      (node (ref "U7") (pin "R2") (pinfunction "GPMC_AD1_R2") (pintype "bidirectional"))
    )
    (net (code "62") (name "Net-(R10-22)") (class "Default")
      (node (ref "R10") (pin "2") (pinfunction "22_2") (pintype "passive"))
      (node (ref "U3") (pin "B6") (pinfunction "D7_B6") (pintype "input"))
      (node (ref "U7") (pin "R4") (pinfunction "GPMC_AD7_R4") (pintype "bidirectional"))
    )
    (net (code "63") (name "Net-(R10-88)") (class "Default")
      (node (ref "R10") (pin "8") (pinfunction "88_8") (pintype "passive"))
      (node (ref "U3") (pin "B5") (pinfunction "D6_B5") (pintype "bidirectional"))
      (node (ref "U7") (pin "P4") (pinfunction "GPMC_AD6_P4") (pintype "bidirectional"))
    )
    (net (code "64") (name "Net-(R10-99)") (class "Default")
      (node (ref "R10") (pin "9") (pinfunction "99_9") (pintype "passive"))
      (node (ref "U3") (pin "A5") (pinfunction "D2_A5") (pintype "input"))
      (node (ref "U7") (pin "R1") (pinfunction "GPMC_AD2_R1") (pintype "bidirectional"))
    )
    (net (code "65") (name "Net-(TP4-1)") (class "Default")
      (node (ref "TP4") (pin "P$1") (pinfunction "1_P$1") (pintype "bidirectional"))
      (node (ref "U7") (pin "B10") (pinfunction "UART1_CTSN_B10") (pintype "bidirectional"))
    )
    (net (code "66") (name "Net-(TP5-1)") (class "Default")
      (node (ref "TP5") (pin "P$1") (pinfunction "1_P$1") (pintype "bidirectional"))
      (node (ref "U7") (pin "C1") (pinfunction "TDI_C1") (pintype "bidirectional"))
    )
    (net (code "67") (name "Net-(TP6-1)") (class "Default")
      (node (ref "TP6") (pin "P$1") (pinfunction "1_P$1") (pintype "bidirectional"))
      (node (ref "U7") (pin "C2") (pinfunction "TDO_C2") (pintype "bidirectional"))
    )
    (net (code "68") (name "Net-(TP7-1)") (class "Default")
      (node (ref "TP7") (pin "P$1") (pinfunction "1_P$1") (pintype "bidirectional"))
      (node (ref "U7") (pin "D1") (pinfunction "TCK_D1") (pintype "bidirectional"))
    )
    (net (code "69") (name "Net-(TP8-1)") (class "Default")
      (node (ref "TP8") (pin "P$1") (pinfunction "1_P$1") (pintype "bidirectional"))
      (node (ref "U7") (pin "D2") (pinfunction "TMS_D2") (pintype "bidirectional"))
    )
    (net (code "70") (name "Net-(TP9-1)") (class "Default")
      (node (ref "TP9") (pin "P$1") (pinfunction "1_P$1") (pintype "bidirectional"))
      (node (ref "U7") (pin "D3") (pinfunction "TRSTN_D3") (pintype "bidirectional"))
    )
    (net (code "71") (name "Net-(TP10-1)") (class "Default")
      (node (ref "TP10") (pin "P$1") (pinfunction "1_P$1") (pintype "bidirectional"))
      (node (ref "U7") (pin "E2") (pinfunction "EMU0_E2") (pintype "bidirectional"))
    )
    (net (code "72") (name "Net-(TP11-1)") (class "Default")
      (node (ref "TP11") (pin "P$1") (pinfunction "1_P$1") (pintype "bidirectional"))
      (node (ref "U7") (pin "E3") (pinfunction "EMU1_E3") (pintype "bidirectional"))
    )
    (net (code "73") (name "Net-(TP12-1)") (class "Default")
      (node (ref "TP12") (pin "P$1") (pinfunction "1_P$1") (pintype "bidirectional"))
      (node (ref "U7") (pin "M14") (pinfunction "USB1_DRVVBUS_M14") (pintype "bidirectional"))
    )
    (net (code "74") (name "Net-(TP13-1)") (class "Default")
      (node (ref "TP13") (pin "P$1") (pinfunction "1_P$1") (pintype "bidirectional"))
      (node (ref "U7") (pin "A10") (pinfunction "UART1_RTSN_A10") (pintype "bidirectional"))
    )
    (net (code "75") (name "Net-(TP15-1)") (class "Default")
      (node (ref "TP15") (pin "P$1") (pinfunction "1_P$1") (pintype "bidirectional"))
      (node (ref "U7") (pin "L15") (pinfunction "USB1_DP_L15") (pintype "bidirectional"))
    )
    (net (code "76") (name "Net-(TP16-1)") (class "Default")
      (node (ref "TP16") (pin "P$1") (pinfunction "1_P$1") (pintype "bidirectional"))
      (node (ref "U7") (pin "L16") (pinfunction "USB1_DM_L16") (pintype "bidirectional"))
    )
    (net (code "77") (name "Net-(TP17-1)") (class "Default")
      (node (ref "TP17") (pin "P$1") (pinfunction "1_P$1") (pintype "bidirectional"))
      (node (ref "U7") (pin "M15") (pinfunction "USB1_VBUS_M15") (pintype "bidirectional"))
    )
    (net (code "78") (name "Net-(TP35-1)") (class "Default")
      (node (ref "TP35") (pin "P$1") (pinfunction "1_P$1") (pintype "bidirectional"))
      (node (ref "U11") (pin "5") (pinfunction "SHDN_5") (pintype "input"))
    )
    (net (code "79") (name "Net-(TP36-1)") (class "Default")
      (node (ref "TP36") (pin "P$1") (pinfunction "1_P$1") (pintype "bidirectional"))
      (node (ref "U7") (pin "B8") (pinfunction "AIN1_B8") (pintype "bidirectional"))
    )
    (net (code "80") (name "Net-(TP37-1)") (class "Default")
      (node (ref "TP37") (pin "P$1") (pinfunction "1_P$1") (pintype "bidirectional"))
      (node (ref "U7") (pin "B6") (pinfunction "AIN2_B6") (pintype "bidirectional"))
    )
    (net (code "81") (name "Net-(TP38-1)") (class "Default")
      (node (ref "TP38") (pin "P$1") (pinfunction "1_P$1") (pintype "bidirectional"))
      (node (ref "U7") (pin "C6") (pinfunction "AIN3_C6") (pintype "bidirectional"))
    )
    (net (code "82") (name "Net-(TP40-1)") (class "Default")
      (node (ref "TP40") (pin "P$1") (pinfunction "1_P$1") (pintype "bidirectional"))
      (node (ref "U11") (pin "8") (pinfunction "S_8") (pintype "input"))
    )
    (net (code "83") (name "Net-(TP69-1)") (class "Default")
      (node (ref "TP69") (pin "P$1") (pinfunction "1_P$1") (pintype "bidirectional"))
      (node (ref "U17") (pin "7") (pinfunction "~{HOLD}_7") (pintype "input"))
    )
    (net (code "84") (name "Net-(TP102-1)") (class "Default")
      (node (ref "TP102") (pin "P$1") (pinfunction "1_P$1") (pintype "bidirectional"))
      (node (ref "U7") (pin "T11") (pinfunction "PMIC_PB_IN_T11") (pintype "bidirectional"))
    )
    (net (code "85") (name "Net-(TP121-1)") (class "Default")
      (node (ref "TP121") (pin "P$1") (pinfunction "1_P$1") (pintype "bidirectional"))
      (node (ref "U7") (pin "N10") (pinfunction "PMIC_POWER_EN_N10") (pintype "output"))
      (node (ref "U7") (pin "N11") (pinfunction "PMIC_PWR_EN_N11") (pintype "input"))
    )
    (net (code "86") (name "Net-(TP129-1)") (class "Default")
      (node (ref "TP129") (pin "P$1") (pinfunction "1_P$1") (pintype "bidirectional"))
      (node (ref "U7") (pin "N6") (pinfunction "PMIC_TS_N6") (pintype "bidirectional"))
    )
    (net (code "87") (name "Net-(TP130-1)") (class "Default")
      (node (ref "TP130") (pin "P$1") (pinfunction "1_P$1") (pintype "bidirectional"))
      (node (ref "U7") (pin "N7") (pinfunction "PMIC_BAT_SENSE_N7") (pintype "bidirectional"))
      (node (ref "U7") (pin "P8") (pinfunction "VIN_BAT_P8") (pintype "power_in"))
      (node (ref "U7") (pin "R8") (pinfunction "VIN_BAT_R8") (pintype "power_in"))
      (node (ref "U7") (pin "T8") (pinfunction "VIN_BAT_T8") (pintype "power_in"))
    )
    (net (code "88") (name "Net-(TP132-1)") (class "Default")
      (node (ref "TP132") (pin "P$1") (pinfunction "1_P$1") (pintype "bidirectional"))
      (node (ref "U7") (pin "N4") (pinfunction "PMIC_LDO_PGOOD_N4") (pintype "output"))
      (node (ref "U7") (pin "N5") (pinfunction "RTC_PWRONRSTN_N5") (pintype "bidirectional"))
    )
    (net (code "89") (name "Net-(TP133-1)") (class "Default")
      (node (ref "TP133") (pin "P$1") (pinfunction "1_P$1") (pintype "bidirectional"))
      (node (ref "U7") (pin "N13") (pinfunction "PMIC_MUX_IN_N13") (pintype "bidirectional"))
    )
    (net (code "90") (name "Net-(TP136-1)") (class "Default")
      (node (ref "TP136") (pin "P$1") (pinfunction "1_P$1") (pintype "bidirectional"))
      (node (ref "U7") (pin "M13") (pinfunction "PMIC_NRESET_M13") (pintype "bidirectional"))
    )
    (net (code "91") (name "Net-(TP138-1)") (class "Default")
      (node (ref "TP138") (pin "P$1") (pinfunction "1_P$1") (pintype "bidirectional"))
      (node (ref "U7") (pin "K14") (pinfunction "USB0_ID_K14") (pintype "bidirectional"))
    )
    (net (code "92") (name "Net-(TP139-1)") (class "Default")
      (node (ref "TP139") (pin "P$1") (pinfunction "1_P$1") (pintype "bidirectional"))
      (node (ref "U7") (pin "J15") (pinfunction "USB0_DRVVBUS_J15") (pintype "bidirectional"))
    )
    (net (code "93") (name "Net-(TP140-1)") (class "Default")
      (node (ref "TP140") (pin "P$1") (pinfunction "1_P$1") (pintype "bidirectional"))
      (node (ref "U7") (pin "L4") (pinfunction "PMIC_NWAKEUP_L4") (pintype "output"))
      (node (ref "U7") (pin "M4") (pinfunction "EXT_WAKEUP_M4") (pintype "bidirectional"))
    )
    (net (code "94") (name "Net-(TP141-1)") (class "Default")
      (node (ref "TP141") (pin "P$1") (pinfunction "1_P$1") (pintype "bidirectional"))
      (node (ref "U7") (pin "K13") (pinfunction "USB0_CE_K13") (pintype "bidirectional"))
    )
    (net (code "95") (name "Net-(TP144-1)") (class "Default")
      (node (ref "TP144") (pin "P$1") (pinfunction "1_P$1") (pintype "bidirectional"))
      (node (ref "U7") (pin "L13") (pinfunction "USB1_CE_L13") (pintype "bidirectional"))
    )
    (net (code "96") (name "Net-(TP154-1)") (class "Default")
      (node (ref "TP154") (pin "P$1") (pinfunction "1_P$1") (pintype "bidirectional"))
      (node (ref "U7") (pin "G4") (pinfunction "VDD_CORE_G4") (pintype "bidirectional"))
    )
    (net (code "97") (name "Net-(TP156-1)") (class "Default")
      (node (ref "TP156") (pin "P$1") (pinfunction "1_P$1") (pintype "bidirectional"))
      (node (ref "U7") (pin "F4") (pinfunction "VDDS_DDR_F4") (pintype "bidirectional"))
    )
    (net (code "98") (name "Net-(TP157-1)") (class "Default")
      (node (ref "TP157") (pin "P$1") (pinfunction "1_P$1") (pintype "bidirectional"))
      (node (ref "U7") (pin "H6") (pinfunction "VPP_H6") (pintype "bidirectional"))
    )
    (net (code "99") (name "Net-(TP160-1)") (class "Default")
      (node (ref "TP160") (pin "P$1") (pinfunction "1_P$1") (pintype "bidirectional"))
      (node (ref "U7") (pin "F13") (pinfunction "VDD_MPU_F13") (pintype "bidirectional"))
    )
    (net (code "100") (name "Net-(TP161-1)") (class "Default")
      (node (ref "TP161") (pin "P$1") (pinfunction "1_P$1") (pintype "bidirectional"))
      (node (ref "U7") (pin "F11") (pinfunction "SYS_VDD2_3P3V_F11") (pintype "power_in"))
      (node (ref "U7") (pin "G11") (pinfunction "SYS_VDD2_3P3V_G11") (pintype "power_in"))
    )
    (net (code "101") (name "Net-(TP163-1)") (class "Default")
      (node (ref "TP163") (pin "P$1") (pinfunction "1_P$1") (pintype "bidirectional"))
      (node (ref "U7") (pin "F10") (pinfunction "SYS_VDD_1P8V_F10") (pintype "power_in"))
      (node (ref "U7") (pin "G10") (pinfunction "SYS_VDD_1P8V_G10") (pintype "power_in"))
      (node (ref "U7") (pin "H10") (pinfunction "SYS_VDD_1P8V_H10") (pintype "power_in"))
      (node (ref "U7") (pin "H11") (pinfunction "SYS_VDD_1P8V_H11") (pintype "power_in"))
      (node (ref "U7") (pin "J10") (pinfunction "SYS_VDD_1P8V_J10") (pintype "power_in"))
      (node (ref "U7") (pin "J11") (pinfunction "SYS_VDD_1P8V_J11") (pintype "power_in"))
      (node (ref "U7") (pin "K10") (pinfunction "SYS_VDD_1P8V_K10") (pintype "power_in"))
      (node (ref "U7") (pin "L10") (pinfunction "SYS_VDD_1P8V_L10") (pintype "power_in"))
    )
    (net (code "102") (name "Net-(TP166-1)") (class "Default")
      (node (ref "TP166") (pin "P$1") (pinfunction "1_P$1") (pintype "bidirectional"))
      (node (ref "U7") (pin "G13") (pinfunction "VDDS_PLL_G13") (pintype "bidirectional"))
    )
    (net (code "103") (name "Net-(TP167-1)") (class "Default")
      (node (ref "TP167") (pin "P$1") (pinfunction "1_P$1") (pintype "bidirectional"))
      (node (ref "U7") (pin "D4") (pinfunction "EXTINTN_D4") (pintype "bidirectional"))
      (node (ref "U7") (pin "E4") (pinfunction "PMIC_NINT_E4") (pintype "output"))
    )
    (net (code "104") (name "Net-(TP168-1)") (class "Default")
      (node (ref "TP168") (pin "P$1") (pinfunction "1_P$1") (pintype "bidirectional"))
      (node (ref "U7") (pin "D6") (pinfunction "PMIC_MUX_OUT_D6") (pintype "bidirectional"))
    )
    (net (code "105") (name "Net-(TP173-1)") (class "Default")
      (node (ref "TP173") (pin "P$1") (pinfunction "1_P$1") (pintype "bidirectional"))
      (node (ref "U7") (pin "D5") (pinfunction "CAP_VDD_RTC_D5") (pintype "bidirectional"))
    )
    (net (code "106") (name "Net-(U2-RXIN1+)") (class "Default")
      (node (ref "R30") (pin "1") (pinfunction "1_1") (pintype "passive"))
      (node (ref "U2") (pin "11") (pinfunction "RXIN1+_11") (pintype "input"))
    )
    (net (code "107") (name "Net-(U2-RXIN1-)") (class "Default")
      (node (ref "R30") (pin "2") (pinfunction "2_2") (pintype "passive"))
      (node (ref "U2") (pin "10") (pinfunction "RXIN1-_10") (pintype "input"))
    )
    (net (code "108") (name "Net-(U2-RXIN2+)") (class "Default")
      (node (ref "R29") (pin "1") (pinfunction "1_1") (pintype "passive"))
      (node (ref "U2") (pin "15") (pinfunction "RXIN2+_15") (pintype "input"))
    )
    (net (code "109") (name "Net-(U2-RXIN2-)") (class "Default")
      (node (ref "R29") (pin "2") (pinfunction "2_2") (pintype "passive"))
      (node (ref "U2") (pin "14") (pinfunction "RXIN2-_14") (pintype "input"))
    )
    (net (code "110") (name "Net-(U2-~{PWR_DWN})") (class "Default")
      (node (ref "JP1") (pin "2") (pinfunction "2_2") (pintype "passive"))
      (node (ref "U2") (pin "22") (pinfunction "~{PWR_DWN}_22") (pintype "input"))
    )
    (net (code "111") (name "Net-(U3-VDDI)") (class "Default")
      (node (ref "C10") (pin "1") (pinfunction "1_1") (pintype "passive"))
      (node (ref "C12") (pin "1") (pinfunction "1_1") (pintype "passive"))
      (node (ref "U3") (pin "C2") (pinfunction "VDDI_C2") (pintype "power_in"))
    )
    (net (code "112") (name "Net-(U7A-EEPROM_WP)") (class "Default")
      (node (ref "R75") (pin "2") (pinfunction "2_2") (pintype "passive"))
      (node (ref "U7") (pin "M2") (pinfunction "EEPROM_WP_M2") (pintype "bidirectional"))
    )
    (net (code "113") (name "Net-(U7A-I2C0_SCL)") (class "Default")
      (node (ref "R73") (pin "2") (pinfunction "2_2") (pintype "passive"))
      (node (ref "U7") (pin "C10") (pinfunction "I2C0_SCL_C10") (pintype "bidirectional"))
      (node (ref "U7") (pin "D10") (pinfunction "PMIC_SCL_D10") (pintype "bidirectional"))
    )
    (net (code "114") (name "Net-(U7A-I2C0_SDA)") (class "Default")
      (node (ref "R74") (pin "2") (pinfunction "2_2") (pintype "passive"))
      (node (ref "U7") (pin "C11") (pinfunction "I2C0_SDA_C11") (pintype "bidirectional"))
      (node (ref "U7") (pin "D11") (pinfunction "PMIC_SDA_D11") (pintype "bidirectional"))
    )
    (net (code "115") (name "Net-(U7A-RTC_KALDO_ENN)") (class "Default")
      (node (ref "R15") (pin "2") (pinfunction "2_2") (pintype "passive"))
      (node (ref "U7") (pin "M16") (pinfunction "RTC_KALDO_ENN_M16") (pintype "bidirectional"))
    )
    (net (code "116") (name "Net-(U7B-OSC1_GND)") (class "Default")
      (node (ref "C29") (pin "2") (pinfunction "2_2") (pintype "passive"))
      (node (ref "C30") (pin "2") (pinfunction "2_2") (pintype "passive"))
      (node (ref "U7") (pin "B5") (pinfunction "OSC1_GND_B5") (pintype "bidirectional"))
    )
    (net (code "117") (name "Net-(U7B-OSC1_IN)") (class "Default")
      (node (ref "C30") (pin "1") (pinfunction "1_1") (pintype "passive"))
      (node (ref "R27") (pin "2") (pinfunction "2_2") (pintype "passive"))
      (node (ref "U7") (pin "A6") (pinfunction "OSC1_IN_A6") (pintype "bidirectional"))
      (node (ref "Y2") (pin "P$2") (pinfunction "P$2_P$2") (pintype "passive"))
    )
    (net (code "118") (name "Net-(U7B-OSC1_OUT)") (class "Default")
      (node (ref "C29") (pin "1") (pinfunction "1_1") (pintype "passive"))
      (node (ref "R27") (pin "1") (pinfunction "1_1") (pintype "passive"))
      (node (ref "U7") (pin "A5") (pinfunction "OSC1_OUT_A5") (pintype "bidirectional"))
      (node (ref "Y2") (pin "P$1") (pinfunction "P$1_P$1") (pintype "passive"))
    )
    (net (code "119") (name "Net-(U7C-GPMC_A5)") (class "Default")
      (node (ref "R2") (pin "1") (pinfunction "1_1") (pintype "passive"))
      (node (ref "U7") (pin "P13") (pinfunction "GPMC_A5_P13") (pintype "bidirectional"))
    )
    (net (code "120") (name "Net-(U7C-GPMC_A6)") (class "Default")
      (node (ref "R3") (pin "1") (pinfunction "1_1") (pintype "passive"))
      (node (ref "U7") (pin "T14") (pinfunction "GPMC_A6_T14") (pintype "bidirectional"))
    )
    (net (code "121") (name "Net-(U7C-GPMC_A7)") (class "Default")
      (node (ref "R4") (pin "1") (pinfunction "1_1") (pintype "passive"))
      (node (ref "U7") (pin "R14") (pinfunction "GPMC_A7_R14") (pintype "bidirectional"))
    )
    (net (code "122") (name "Net-(U7C-GPMC_A8)") (class "Default")
      (node (ref "R5") (pin "1") (pinfunction "1_1") (pintype "passive"))
      (node (ref "U7") (pin "P14") (pinfunction "GPMC_A8_P14") (pintype "bidirectional"))
    )
    (net (code "123") (name "Net-(U10-CATHODE)") (class "Default")
      (node (ref "Q1") (pin "B") (pinfunction "B_B") (pintype "passive"))
      (node (ref "R23") (pin "1") (pinfunction "1_1") (pintype "passive"))
      (node (ref "U10") (pin "2") (pinfunction "CATHODE_2") (pintype "bidirectional"))
    )
    (net (code "124") (name "Net-(U10-REF)") (class "Default")
      (node (ref "R28") (pin "1") (pinfunction "1_1") (pintype "passive"))
      (node (ref "R31") (pin "2") (pinfunction "2_2") (pintype "passive"))
      (node (ref "U10") (pin "1") (pinfunction "REF_1") (pintype "bidirectional"))
    )
    (net (code "125") (name "Net-(U11-RXD)") (class "Default")
      (node (ref "U11") (pin "4") (pinfunction "RXD_4") (pintype "output"))
      (node (ref "U7") (pin "B11") (pinfunction "UART1_TXD_B11") (pintype "bidirectional"))
    )
    (net (code "126") (name "Net-(U11-TXD)") (class "Default")
      (node (ref "U11") (pin "1") (pinfunction "TXD_1") (pintype "input"))
      (node (ref "U7") (pin "A11") (pinfunction "UART1_RXD_A11") (pintype "bidirectional"))
    )
    (net (code "127") (name "Net-(U12-INP)") (class "Default")
      (node (ref "C32") (pin "1") (pinfunction "1_1") (pintype "passive"))
      (node (ref "R36") (pin "1") (pinfunction "1_1") (pintype "passive"))
      (node (ref "R37") (pin "1") (pinfunction "1_1") (pintype "passive"))
      (node (ref "U12") (pin "1") (pinfunction "INP_1") (pintype "input"))
    )
    (net (code "128") (name "Net-(U12-OUT)") (class "Default")
      (node (ref "R35") (pin "1") (pinfunction "1_1") (pintype "passive"))
      (node (ref "TP44") (pin "1") (pinfunction "1_1") (pintype "passive"))
      (node (ref "U12") (pin "4") (pinfunction "OUT_4") (pintype "output"))
    )
    (net (code "129") (name "Net-(U13-INP)") (class "Default")
      (node (ref "C35") (pin "1") (pinfunction "1_1") (pintype "passive"))
      (node (ref "R44") (pin "1") (pinfunction "1_1") (pintype "passive"))
      (node (ref "R45") (pin "1") (pinfunction "1_1") (pintype "passive"))
      (node (ref "U13") (pin "1") (pinfunction "INP_1") (pintype "input"))
    )
    (net (code "130") (name "Net-(U13-OUT)") (class "Default")
      (node (ref "R43") (pin "1") (pinfunction "1_1") (pintype "passive"))
      (node (ref "TP43") (pin "1") (pinfunction "1_1") (pintype "passive"))
      (node (ref "U13") (pin "4") (pinfunction "OUT_4") (pintype "output"))
    )
    (net (code "131") (name "Net-(U14-CIN1+)") (class "Default")
      (node (ref "R50") (pin "1") (pinfunction "1_1") (pintype "passive"))
      (node (ref "R51") (pin "2") (pinfunction "2_2") (pintype "passive"))
      (node (ref "TP57") (pin "1") (pinfunction "1_1") (pintype "passive"))
      (node (ref "U14") (pin "10") (pinfunction "CIN1+_10") (pintype "input"))
    )
    (net (code "132") (name "Net-(U14-CIN1-)") (class "Default")
      (node (ref "R42") (pin "2") (pinfunction "2_2") (pintype "passive"))
      (node (ref "R47") (pin "1") (pinfunction "1_1") (pintype "passive"))
      (node (ref "TP47") (pin "1") (pinfunction "1_1") (pintype "passive"))
      (node (ref "U14") (pin "11") (pinfunction "CIN1-_11") (pintype "input"))
    )
    (net (code "133") (name "Net-(U14-CIN2+)") (class "Default")
      (node (ref "R47") (pin "2") (pinfunction "2_2") (pintype "passive"))
      (node (ref "U14") (pin "12") (pinfunction "REF_12") (pintype "output"))
      (node (ref "U14") (pin "8") (pinfunction "CIN2+_8") (pintype "input"))
    )
    (net (code "134") (name "Net-(U14-INHIBIT)") (class "Default")
      (node (ref "R38") (pin "1") (pinfunction "1_1") (pintype "passive"))
      (node (ref "U14") (pin "5") (pinfunction "INHIBIT_5") (pintype "input"))
    )
    (net (code "135") (name "Net-(U14-IOUT)") (class "Default")
      (node (ref "R50") (pin "2") (pinfunction "2_2") (pintype "passive"))
      (node (ref "U14") (pin "14") (pinfunction "IOUT_14") (pintype "output"))
    )
    (net (code "136") (name "Net-(U14-RS+)") (class "Default")
      (node (ref "C44") (pin "1") (pinfunction "1_1") (pintype "passive"))
      (node (ref "Q6") (pin "1") (pinfunction "D_1") (pintype "passive"))
      (node (ref "Q6") (pin "2") (pinfunction "D_2") (pintype "passive"))
      (node (ref "Q6") (pin "5") (pinfunction "D_5") (pintype "passive"))
      (node (ref "Q6") (pin "6") (pinfunction "D_6") (pintype "passive"))
      (node (ref "R63") (pin "1") (pinfunction "1_1") (pintype "passive"))
      (node (ref "U14") (pin "16") (pinfunction "RS+_16") (pintype "passive"))
    )
    (net (code "137") (name "Net-(U15-PG)") (class "Default")
      (node (ref "TP48") (pin "1") (pinfunction "1_1") (pintype "passive"))
      (node (ref "U15") (pin "13") (pinfunction "PG_13") (pintype "open_collector"))
    )
    (net (code "138") (name "Net-(U15-SYNC)") (class "Default")
      (node (ref "R34") (pin "1") (pinfunction "1_1") (pintype "passive"))
      (node (ref "R40") (pin "2") (pinfunction "2_2") (pintype "passive"))
      (node (ref "TP46") (pin "1") (pinfunction "1_1") (pintype "passive"))
      (node (ref "U15") (pin "5") (pinfunction "SYNC_5") (pintype "input"))
    )
    (net (code "139") (name "Net-(U16-IO6)") (class "Default")
      (node (ref "TP53") (pin "1") (pinfunction "1_1") (pintype "passive"))
      (node (ref "U16") (pin "11") (pinfunction "IO6_11") (pintype "bidirectional"))
    )
    (net (code "140") (name "Net-(U16-IO7)") (class "Default")
      (node (ref "TP56") (pin "1") (pinfunction "1_1") (pintype "passive"))
      (node (ref "U16") (pin "12") (pinfunction "IO7_12") (pintype "bidirectional"))
    )
    (net (code "141") (name "Net-(U16-~{RESET})") (class "Default")
      (node (ref "R72") (pin "1") (pinfunction "1_1") (pintype "passive"))
      (node (ref "U16") (pin "13") (pinfunction "~{RESET}_13") (pintype "input"))
    )
    (net (code "142") (name "Net-(U17-MISO)") (class "Default")
      (node (ref "U17") (pin "2") (pinfunction "MISO_2") (pintype "output"))
      (node (ref "U7") (pin "B13") (pinfunction "SPI0_D0_B13") (pintype "bidirectional"))
    )
    (net (code "143") (name "Net-(U17-MOSI)") (class "Default")
      (node (ref "U17") (pin "5") (pinfunction "MOSI_5") (pintype "input"))
      (node (ref "U7") (pin "B14") (pinfunction "SPI0_D1_B14") (pintype "bidirectional"))
    )
    (net (code "144") (name "Net-(U17-SCK)") (class "Default")
      (node (ref "U17") (pin "6") (pinfunction "SCK_6") (pintype "input"))
      (node (ref "U7") (pin "A13") (pinfunction "SPI0_SCLK_A13") (pintype "bidirectional"))
    )
    (net (code "145") (name "Net-(U17-~{CS})") (class "Default")
      (node (ref "U17") (pin "1") (pinfunction "~{CS}_1") (pintype "input"))
      (node (ref "U7") (pin "A14") (pinfunction "SPI0_CS0_A14") (pintype "bidirectional"))
    )
    (net (code "146") (name "Net-(U17-~{WP})") (class "Default")
      (node (ref "R59") (pin "1") (pinfunction "1_1") (pintype "passive"))
      (node (ref "R60") (pin "2") (pinfunction "2_2") (pintype "passive"))
      (node (ref "U17") (pin "3") (pinfunction "~{WP}_3") (pintype "input"))
    )
    (net (code "147") (name "ON{slash}~{OFF}") (class "Default")
      (node (ref "C34") (pin "1") (pinfunction "1_1") (pintype "passive"))
      (node (ref "Q4") (pin "1") (pinfunction "G_1") (pintype "passive"))
      (node (ref "R46") (pin "2") (pinfunction "2_2") (pintype "passive"))
      (node (ref "R49") (pin "2") (pinfunction "2_2") (pintype "passive"))
      (node (ref "TP50") (pin "1") (pinfunction "1_1") (pintype "passive"))
      (node (ref "U14") (pin "1") (pinfunction "VCC_1") (pintype "power_in"))
      (node (ref "U16") (pin "8") (pinfunction "IO3_8") (pintype "bidirectional"))
    )
    (net (code "148") (name "OPD_PWR") (class "Default")
      (node (ref "J4") (pin "15") (pinfunction "15_15") (pintype "passive"))
      (node (ref "J4") (pin "16") (pinfunction "16_16") (pintype "passive"))
      (node (ref "R71") (pin "1") (pinfunction "1_1") (pintype "passive"))
    )
    (net (code "149") (name "OPD_SCL") (class "Default")
      (node (ref "J4") (pin "13") (pinfunction "13_13") (pintype "passive"))
      (node (ref "J4") (pin "14") (pinfunction "14_14") (pintype "passive"))
      (node (ref "R48") (pin "1") (pinfunction "1_1") (pintype "passive"))
    )
    (net (code "150") (name "OPD_SDA") (class "Default")
      (node (ref "J4") (pin "11") (pinfunction "11_11") (pintype "passive"))
      (node (ref "J4") (pin "12") (pinfunction "12_12") (pintype "passive"))
      (node (ref "R41") (pin "1") (pinfunction "1_1") (pintype "passive"))
    )
    (net (code "151") (name "OSC0_GND") (class "Default")
      (node (ref "C19") (pin "1") (pinfunction "1_1") (pintype "passive"))
      (node (ref "C22") (pin "1") (pinfunction "1_1") (pintype "passive"))
      (node (ref "U7") (pin "N15") (pinfunction "OSC0_GND_N15") (pintype "bidirectional"))
    )
    (net (code "152") (name "OSC0_IN") (class "Default")
      (node (ref "C19") (pin "2") (pinfunction "2_2") (pintype "passive"))
      (node (ref "R13") (pin "2") (pinfunction "2_2") (pintype "passive"))
      (node (ref "U7") (pin "P16") (pinfunction "OSC0_IN_P16") (pintype "bidirectional"))
      (node (ref "Y1") (pin "1") (pinfunction "X1_1") (pintype "passive"))
    )
    (net (code "153") (name "OSC0_OUT") (class "Default")
      (node (ref "C22") (pin "2") (pinfunction "2_2") (pintype "passive"))
      (node (ref "R13") (pin "1") (pinfunction "1_1") (pintype "passive"))
      (node (ref "U7") (pin "N16") (pinfunction "OSC0_OUT_N16") (pintype "bidirectional"))
      (node (ref "Y1") (pin "3") (pinfunction "X2_3") (pintype "passive"))
    )
    (net (code "154") (name "OUT1_N") (class "Default")
      (node (ref "J2") (pin "5") (pinfunction "5_5") (pintype "passive"))
      (node (ref "J2") (pin "6") (pinfunction "6_6") (pintype "passive"))
      (node (ref "R6") (pin "2") (pinfunction "2_2") (pintype "passive"))
      (node (ref "U2") (pin "8") (pinfunction "RXIN0-_8") (pintype "input"))
    )
    (net (code "155") (name "OUT1_P") (class "Default")
      (node (ref "J2") (pin "7") (pinfunction "7_7") (pintype "passive"))
      (node (ref "J2") (pin "8") (pinfunction "8_8") (pintype "passive"))
      (node (ref "R6") (pin "1") (pinfunction "1_1") (pintype "passive"))
      (node (ref "U2") (pin "9") (pinfunction "RXIN0+_9") (pintype "input"))
    )
    (net (code "156") (name "PB6{slash}SCL") (class "Default")
      (node (ref "TP67") (pin "1") (pinfunction "1_1") (pintype "passive"))
      (node (ref "U16") (pin "4") (pinfunction "IO0_4") (pintype "bidirectional"))
    )
    (net (code "157") (name "PB7{slash}SDA") (class "Default")
      (node (ref "TP68") (pin "1") (pinfunction "1_1") (pintype "passive"))
      (node (ref "U16") (pin "5") (pinfunction "IO1_5") (pintype "bidirectional"))
    )
    (net (code "158") (name "PEN-SCL-FILT") (class "Default")
      (node (ref "Q3") (pin "6") (pinfunction "D_6") (pintype "passive"))
      (node (ref "R37") (pin "2") (pinfunction "2_2") (pintype "passive"))
      (node (ref "R65") (pin "1") (pinfunction "1_1") (pintype "passive"))
      (node (ref "R67") (pin "1") (pinfunction "1_1") (pintype "passive"))
      (node (ref "R69") (pin "1") (pinfunction "1_1") (pintype "passive"))
      (node (ref "TP42") (pin "1") (pinfunction "1_1") (pintype "passive"))
      (node (ref "TP66") (pin "1") (pinfunction "1_1") (pintype "passive"))
      (node (ref "U16") (pin "15") (pinfunction "SCL_15") (pintype "input"))
    )
    (net (code "159") (name "PEN-SDA-FILT") (class "Default")
      (node (ref "Q3") (pin "4") (pinfunction "D_4") (pintype "passive"))
      (node (ref "R45") (pin "2") (pinfunction "2_2") (pintype "passive"))
      (node (ref "R66") (pin "2") (pinfunction "2_2") (pintype "passive"))
      (node (ref "R68") (pin "2") (pinfunction "2_2") (pintype "passive"))
      (node (ref "R70") (pin "2") (pinfunction "2_2") (pintype "passive"))
      (node (ref "TP41") (pin "1") (pinfunction "1_1") (pintype "passive"))
      (node (ref "TP65") (pin "1") (pinfunction "1_1") (pintype "passive"))
      (node (ref "U16") (pin "16") (pinfunction "SDA_16") (pintype "bidirectional"))
    )
    (net (code "160") (name "PMIC_PGOOD") (class "Default")
      (node (ref "TP110") (pin "P$1") (pinfunction "1_P$1") (pintype "bidirectional"))
      (node (ref "U4") (pin "2") (pinfunction "A_2") (pintype "bidirectional"))
      (node (ref "U7") (pin "N12") (pinfunction "PMIC_PGOOD_N12") (pintype "output"))
      (node (ref "U7") (pin "P11") (pinfunction "PWRONRSTN_P11") (pintype "bidirectional"))
    )
    (net (code "161") (name "POUT") (class "Default")
      (node (ref "TP64") (pin "1") (pinfunction "1_1") (pintype "passive"))
      (node (ref "U14") (pin "13") (pinfunction "POUT_13") (pintype "output"))
    )
    (net (code "162") (name "PRU0_0") (class "Default")
      (node (ref "TP30") (pin "1") (pinfunction "1_1") (pintype "passive"))
      (node (ref "U2") (pin "24") (pinfunction "RXOUT0_24") (pintype "output"))
      (node (ref "U7") (pin "A1") (pinfunction "MCASP0_ACLKX_A1") (pintype "bidirectional"))
    )
    (net (code "163") (name "PRU0_1") (class "Default")
      (node (ref "TP29") (pin "1") (pinfunction "1_1") (pintype "passive"))
      (node (ref "U2") (pin "26") (pinfunction "RXOUT1_26") (pintype "output"))
      (node (ref "U7") (pin "A2") (pinfunction "MCASP0_FSX_A2") (pintype "bidirectional"))
    )
    (net (code "164") (name "PRU0_2") (class "Default")
      (node (ref "TP28") (pin "1") (pinfunction "1_1") (pintype "passive"))
      (node (ref "U2") (pin "27") (pinfunction "RXOUT2_27") (pintype "output"))
      (node (ref "U7") (pin "B2") (pinfunction "MCASP0_AXR0_B2") (pintype "bidirectional"))
    )
    (net (code "165") (name "PRU0_3") (class "Default")
      (node (ref "TP27") (pin "1") (pinfunction "1_1") (pintype "passive"))
      (node (ref "U2") (pin "29") (pinfunction "RXOUT3_29") (pintype "output"))
      (node (ref "U7") (pin "B1") (pinfunction "MCASP0_AHCLKR_B1") (pintype "bidirectional"))
    )
    (net (code "166") (name "PRU0_4") (class "Default")
      (node (ref "TP26") (pin "1") (pinfunction "1_1") (pintype "passive"))
      (node (ref "U2") (pin "30") (pinfunction "RXOUT4_30") (pintype "output"))
      (node (ref "U7") (pin "A3") (pinfunction "MCASP0_ACLKR_A3") (pintype "bidirectional"))
    )
    (net (code "167") (name "PRU0_5") (class "Default")
      (node (ref "TP24") (pin "1") (pinfunction "1_1") (pintype "passive"))
      (node (ref "U2") (pin "31") (pinfunction "RXOUT5_31") (pintype "output"))
      (node (ref "U7") (pin "B3") (pinfunction "MCASP0_FSR_B3") (pintype "bidirectional"))
    )
    (net (code "168") (name "PRU0_6") (class "Default")
      (node (ref "TP23") (pin "1") (pinfunction "1_1") (pintype "passive"))
      (node (ref "U2") (pin "33") (pinfunction "RXOUT6_33") (pintype "output"))
      (node (ref "U7") (pin "C3") (pinfunction "MCASP0_AXR1_C3") (pintype "bidirectional"))
    )
    (net (code "169") (name "PRU0_7") (class "Default")
      (node (ref "R11") (pin "2") (pinfunction "2_2") (pintype "passive"))
      (node (ref "TP21") (pin "1") (pinfunction "1_1") (pintype "passive"))
      (node (ref "U7") (pin "C4") (pinfunction "MCASP0_AHCLKX_C4") (pintype "bidirectional"))
    )
    (net (code "170") (name "PRU0_14") (class "Default")
      (node (ref "TP33") (pin "1") (pinfunction "1_1") (pintype "passive"))
      (node (ref "U7") (pin "P6") (pinfunction "GPMC_AD12_P6") (pintype "bidirectional"))
    )
    (net (code "171") (name "PRU0_15") (class "Default")
      (node (ref "TP34") (pin "1") (pinfunction "1_1") (pintype "passive"))
      (node (ref "U7") (pin "R6") (pinfunction "GPMC_AD13_R6") (pintype "bidirectional"))
    )
    (net (code "172") (name "PRU0_16_CLK") (class "Default")
      (node (ref "TP20") (pin "1") (pinfunction "1_1") (pintype "passive"))
      (node (ref "U2") (pin "23") (pinfunction "RXCLKOUT_23") (pintype "output"))
      (node (ref "U7") (pin "B4") (pinfunction "XDMA_EVENT_INTR1_B4") (pintype "bidirectional"))
    )
    (net (code "173") (name "RESET#") (class "Default")
      (node (ref "TP109") (pin "P$1") (pinfunction "1_P$1") (pintype "bidirectional"))
      (node (ref "U4") (pin "4") (pinfunction "Y_4") (pintype "bidirectional"))
      (node (ref "U7") (pin "R11") (pinfunction "WARMRSTN_R11") (pintype "bidirectional"))
    )
    (net (code "174") (name "SENSOR_ENABLE") (class "Default")
      (node (ref "J2") (pin "13") (pinfunction "13_13") (pintype "passive"))
      (node (ref "J2") (pin "14") (pinfunction "14_14") (pintype "passive"))
      (node (ref "U7") (pin "F3") (pinfunction "LCD_VSYNC_F3") (pintype "bidirectional"))
    )
    (net (code "175") (name "SPI1_CLK") (class "Default")
      (node (ref "J2") (pin "17") (pinfunction "17_17") (pintype "passive"))
      (node (ref "J2") (pin "18") (pinfunction "18_18") (pintype "passive"))
      (node (ref "TP19") (pin "1") (pinfunction "1_1") (pintype "passive"))
      (node (ref "U7") (pin "C5") (pinfunction "ECAP0_IN_PWM0_OUT_C5") (pintype "bidirectional"))
    )
    (net (code "176") (name "SPI1_MISO") (class "Default")
      (node (ref "J2") (pin "15") (pinfunction "15_15") (pintype "passive"))
      (node (ref "J2") (pin "16") (pinfunction "16_16") (pintype "passive"))
      (node (ref "TP1") (pin "1") (pinfunction "1_1") (pintype "passive"))
      (node (ref "U7") (pin "C12") (pinfunction "UART0_CTSN_C12") (pintype "bidirectional"))
    )
    (net (code "177") (name "SPI1_MOSI") (class "Default")
      (node (ref "J2") (pin "19") (pinfunction "19_19") (pintype "passive"))
      (node (ref "J2") (pin "20") (pinfunction "20_20") (pintype "passive"))
      (node (ref "TP18") (pin "1") (pinfunction "1_1") (pintype "passive"))
      (node (ref "U7") (pin "C13") (pinfunction "UART0_RTSN_C13") (pintype "bidirectional"))
    )
    (net (code "178") (name "SYSBOOT0") (class "Default")
      (node (ref "R17") (pin "14") (pinfunction "14_14") (pintype "passive"))
      (node (ref "SB0") (pin "TP") (pinfunction "TP_TP") (pintype "input"))
      (node (ref "U7") (pin "G3") (pinfunction "LCD_DATA0_G3") (pintype "bidirectional"))
    )
    (net (code "179") (name "SYSBOOT1") (class "Default")
      (node (ref "R17") (pin "13") (pinfunction "13_13") (pintype "passive"))
      (node (ref "SB1") (pin "TP") (pinfunction "TP_TP") (pintype "input"))
      (node (ref "U7") (pin "G2") (pinfunction "LCD_DATA1_G2") (pintype "bidirectional"))
    )
    (net (code "180") (name "SYSBOOT2") (class "Default")
      (node (ref "J3") (pin "2") (pinfunction "2_2") (pintype "passive"))
      (node (ref "JP2") (pin "2") (pinfunction "2_2") (pintype "passive"))
      (node (ref "JP3") (pin "2") (pinfunction "2_2") (pintype "passive"))
      (node (ref "SB2") (pin "TP") (pinfunction "TP_TP") (pintype "input"))
      (node (ref "U7") (pin "G1") (pinfunction "LCD_DATA2_G1") (pintype "bidirectional"))
    )
    (net (code "181") (name "SYSBOOT3") (class "Default")
      (node (ref "R17") (pin "11") (pinfunction "11_11") (pintype "passive"))
      (node (ref "SB3") (pin "TP") (pinfunction "TP_TP") (pintype "input"))
      (node (ref "U7") (pin "H3") (pinfunction "LCD_DATA3_H3") (pintype "bidirectional"))
    )
    (net (code "182") (name "SYSBOOT4") (class "Default")
      (node (ref "R17") (pin "10") (pinfunction "10_10") (pintype "passive"))
      (node (ref "SB4") (pin "TP") (pinfunction "TP_TP") (pintype "input"))
      (node (ref "U7") (pin "H2") (pinfunction "LCD_DATA4_H2") (pintype "bidirectional"))
    )
    (net (code "183") (name "SYSBOOT5") (class "Default")
      (node (ref "R17") (pin "15") (pinfunction "15_15") (pintype "passive"))
      (node (ref "SB5") (pin "TP") (pinfunction "TP_TP") (pintype "input"))
      (node (ref "U7") (pin "H1") (pinfunction "LCD_DATA5_H1") (pintype "bidirectional"))
    )
    (net (code "184") (name "SYSBOOT6") (class "Default")
      (node (ref "R17") (pin "16") (pinfunction "16_16") (pintype "passive"))
      (node (ref "SB6") (pin "TP") (pinfunction "TP_TP") (pintype "input"))
      (node (ref "U7") (pin "J3") (pinfunction "LCD_DATA6_J3") (pintype "bidirectional"))
    )
    (net (code "185") (name "SYSBOOT7") (class "Default")
      (node (ref "R16") (pin "16") (pinfunction "16_16") (pintype "passive"))
      (node (ref "SB7") (pin "TP") (pinfunction "TP_TP") (pintype "input"))
      (node (ref "U7") (pin "J2") (pinfunction "LCD_DATA7_J2") (pintype "bidirectional"))
    )
    (net (code "186") (name "SYSBOOT8") (class "Default")
      (node (ref "R16") (pin "15") (pinfunction "15_15") (pintype "passive"))
      (node (ref "SB8") (pin "TP") (pinfunction "TP_TP") (pintype "input"))
      (node (ref "U7") (pin "J1") (pinfunction "LCD_DATA8_J1") (pintype "bidirectional"))
    )
    (net (code "187") (name "SYSBOOT9") (class "Default")
      (node (ref "R16") (pin "14") (pinfunction "14_14") (pintype "passive"))
      (node (ref "SB9") (pin "TP") (pinfunction "TP_TP") (pintype "input"))
      (node (ref "U7") (pin "K3") (pinfunction "LCD_DATA9_K3") (pintype "bidirectional"))
    )
    (net (code "188") (name "SYSBOOT10") (class "Default")
      (node (ref "R16") (pin "13") (pinfunction "13_13") (pintype "passive"))
      (node (ref "SB10") (pin "TP") (pinfunction "TP_TP") (pintype "input"))
      (node (ref "U7") (pin "K2") (pinfunction "LCD_DATA10_K2") (pintype "bidirectional"))
    )
    (net (code "189") (name "SYSBOOT11") (class "Default")
      (node (ref "R16") (pin "12") (pinfunction "12_12") (pintype "passive"))
      (node (ref "SB11") (pin "TP") (pinfunction "TP_TP") (pintype "input"))
      (node (ref "U7") (pin "K1") (pinfunction "LCD_DATA11_K1") (pintype "bidirectional"))
    )
    (net (code "190") (name "SYSBOOT12") (class "Default")
      (node (ref "R16") (pin "11") (pinfunction "11_11") (pintype "passive"))
      (node (ref "SB12") (pin "TP") (pinfunction "TP_TP") (pintype "input"))
      (node (ref "U7") (pin "L3") (pinfunction "LCD_DATA12_L3") (pintype "bidirectional"))
    )
    (net (code "191") (name "SYSBOOT13") (class "Default")
      (node (ref "R16") (pin "10") (pinfunction "10_10") (pintype "passive"))
      (node (ref "SB13") (pin "TP") (pinfunction "TP_TP") (pintype "input"))
      (node (ref "U7") (pin "L2") (pinfunction "LCD_DATA13_L2") (pintype "bidirectional"))
    )
    (net (code "192") (name "SYSBOOT14") (class "Default")
      (node (ref "R17") (pin "9") (pinfunction "9_9") (pintype "passive"))
      (node (ref "SB14") (pin "TP") (pinfunction "TP_TP") (pintype "input"))
      (node (ref "U7") (pin "L1") (pinfunction "LCD_DATA14_L1") (pintype "bidirectional"))
    )
    (net (code "193") (name "SYSBOOT15") (class "Default")
      (node (ref "R16") (pin "9") (pinfunction "9_9") (pintype "passive"))
      (node (ref "SB15") (pin "TP") (pinfunction "TP_TP") (pintype "input"))
      (node (ref "U7") (pin "M3") (pinfunction "LCD_DATA15_M3") (pintype "bidirectional"))
    )
    (net (code "194") (name "TEC_ENABLE") (class "Default")
      (node (ref "J2") (pin "10") (pinfunction "10_10") (pintype "passive"))
      (node (ref "J2") (pin "9") (pinfunction "9_9") (pintype "passive"))
      (node (ref "U7") (pin "F1") (pinfunction "LCD_PCLK_F1") (pintype "bidirectional"))
    )
    (net (code "195") (name "THERM+") (class "Default")
      (node (ref "C51") (pin "1") (pinfunction "1_1") (pintype "passive"))
      (node (ref "J2") (pin "11") (pinfunction "11_11") (pintype "passive"))
      (node (ref "J2") (pin "12") (pinfunction "12_12") (pintype "passive"))
      (node (ref "R21") (pin "1") (pinfunction "1_1") (pintype "passive"))
      (node (ref "U7") (pin "A8") (pinfunction "AIN0_A8") (pintype "bidirectional"))
    )
    (net (code "196") (name "TXCLK_N") (class "Default")
      (node (ref "J2") (pin "1") (pinfunction "1_1") (pintype "passive"))
      (node (ref "J2") (pin "2") (pinfunction "2_2") (pintype "passive"))
      (node (ref "R7") (pin "1") (pinfunction "1_1") (pintype "passive"))
      (node (ref "U2") (pin "16") (pinfunction "RXCLKIN-_16") (pintype "input"))
    )
    (net (code "197") (name "TXCLK_P") (class "Default")
      (node (ref "J2") (pin "3") (pinfunction "3_3") (pintype "passive"))
      (node (ref "J2") (pin "4") (pinfunction "4_4") (pintype "passive"))
      (node (ref "R7") (pin "2") (pinfunction "2_2") (pintype "passive"))
      (node (ref "U2") (pin "17") (pinfunction "RXCLKIN+_17") (pintype "input"))
    )
    (net (code "198") (name "UART0_RX") (class "Default")
      (node (ref "J1") (pin "12") (pinfunction "CARD-RX_12") (pintype "passive"))
      (node (ref "TP31") (pin "1") (pinfunction "1_1") (pintype "passive"))
      (node (ref "U7") (pin "A12") (pinfunction "UART0_RXD_A12") (pintype "bidirectional"))
    )
    (net (code "199") (name "UART0_TX") (class "Default")
      (node (ref "J1") (pin "13") (pinfunction "CARD-TX_13") (pintype "passive"))
      (node (ref "TP32") (pin "1") (pinfunction "1_1") (pintype "passive"))
      (node (ref "U7") (pin "B12") (pinfunction "UART0_TXD_B12") (pintype "bidirectional"))
    )
    (net (code "200") (name "USB_CLI_N") (class "Default")
      (node (ref "J1") (pin "5") (pinfunction "DEVICE-D-_5") (pintype "passive"))
      (node (ref "U1") (pin "3") (pinfunction "I2_3") (pintype "bidirectional"))
      (node (ref "U7") (pin "K16") (pinfunction "USB0_DM_K16") (pintype "bidirectional"))
    )
    (net (code "201") (name "USB_CLI_P") (class "Default")
      (node (ref "J1") (pin "4") (pinfunction "DEVICE-D+_4") (pintype "passive"))
      (node (ref "U1") (pin "1") (pinfunction "I1_1") (pintype "bidirectional"))
      (node (ref "U7") (pin "K15") (pinfunction "USB0_DP_K15") (pintype "bidirectional"))
    )
    (net (code "202") (name "USB_CLI_VBUS") (class "Default")
      (node (ref "FB2") (pin "1") (pinfunction "1_1") (pintype "passive"))
      (node (ref "J1") (pin "1") (pinfunction "VBUSP_1") (pintype "passive"))
      (node (ref "J1") (pin "2") (pinfunction "VBUSP_2") (pintype "passive"))
    )
    (net (code "203") (name "VBUS") (class "Default")
      (node (ref "J4") (pin "21") (pinfunction "21_21") (pintype "passive"))
      (node (ref "J4") (pin "22") (pinfunction "22_22") (pintype "passive"))
      (node (ref "J4") (pin "23") (pinfunction "23_23") (pintype "passive"))
      (node (ref "J4") (pin "24") (pinfunction "24_24") (pintype "passive"))
      (node (ref "J4") (pin "25") (pinfunction "25_25") (pintype "passive"))
      (node (ref "J4") (pin "26") (pinfunction "26_26") (pintype "passive"))
      (node (ref "Q6") (pin "4") (pinfunction "S_4") (pintype "passive"))
      (node (ref "R52") (pin "2") (pinfunction "2_2") (pintype "passive"))
    )
    (net (code "204") (name "VBUSP") (class "Default")
      (node (ref "C33") (pin "2") (pinfunction "2_2") (pintype "passive"))
      (node (ref "C37") (pin "1") (pinfunction "1_1") (pintype "passive"))
      (node (ref "C38") (pin "1") (pinfunction "1_1") (pintype "passive"))
      (node (ref "Q5") (pin "1") (pinfunction "D_1") (pintype "passive"))
      (node (ref "Q5") (pin "2") (pinfunction "D_2") (pintype "passive"))
      (node (ref "Q5") (pin "5") (pinfunction "D_5") (pintype "passive"))
      (node (ref "Q5") (pin "6") (pinfunction "D_6") (pintype "passive"))
      (node (ref "R34") (pin "2") (pinfunction "2_2") (pintype "passive"))
      (node (ref "R61") (pin "2") (pinfunction "2_2") (pintype "passive"))
      (node (ref "TP55") (pin "1") (pinfunction "1_1") (pintype "passive"))
      (node (ref "U15") (pin "2") (pinfunction "VIN_2") (pintype "power_in"))
      (node (ref "U15") (pin "3") (pinfunction "VIN_3") (pintype "power_in"))
      (node (ref "U15") (pin "4") (pinfunction "EN_4") (pintype "input"))
      (node (ref "U15") (pin "8") (pinfunction "VIN_8") (pintype "power_in"))
    )
    (net (code "205") (name "VDD") (class "Default")
      (node (ref "C4") (pin "1") (pinfunction "1_1") (pintype "passive"))
      (node (ref "TP3") (pin "P$1") (pinfunction "1_P$1") (pintype "bidirectional"))
      (node (ref "U1") (pin "5") (pinfunction "VCC_5") (pintype "power_in"))
      (node (ref "U7") (pin "K6") (pinfunction "SYS_VOUT_K6") (pintype "power_in"))
      (node (ref "U7") (pin "K7") (pinfunction "SYS_VOUT_K7") (pintype "power_in"))
      (node (ref "U7") (pin "L6") (pinfunction "SYS_VOUT_L6") (pintype "power_in"))
      (node (ref "U7") (pin "L7") (pinfunction "SYS_VOUT_L7") (pintype "power_in"))
    )
    (net (code "206") (name "VIN_USB") (class "Default")
      (node (ref "C13") (pin "1") (pinfunction "1_1") (pintype "passive"))
      (node (ref "FB2") (pin "2") (pinfunction "2_2") (pintype "passive"))
      (node (ref "U7") (pin "J16") (pinfunction "USB0_VBUS_J16") (pintype "bidirectional"))
      (node (ref "U7") (pin "P9") (pinfunction "VIN_USB_P9") (pintype "power_in"))
      (node (ref "U7") (pin "R9") (pinfunction "VIN_USB_R9") (pintype "power_in"))
      (node (ref "U7") (pin "T9") (pinfunction "VIN_USB_T9") (pintype "power_in"))
    )
    (net (code "207") (name "VPD") (class "Default")
      (node (ref "C39") (pin "2") (pinfunction "2_2") (pintype "passive"))
      (node (ref "R32") (pin "2") (pinfunction "2_2") (pintype "passive"))
      (node (ref "R36") (pin "2") (pinfunction "2_2") (pintype "passive"))
      (node (ref "R44") (pin "2") (pinfunction "2_2") (pintype "passive"))
      (node (ref "R53") (pin "2") (pinfunction "2_2") (pintype "passive"))
      (node (ref "R55") (pin "2") (pinfunction "2_2") (pintype "passive"))
      (node (ref "R57") (pin "2") (pinfunction "2_2") (pintype "passive"))
      (node (ref "R71") (pin "2") (pinfunction "2_2") (pintype "passive"))
      (node (ref "R72") (pin "2") (pinfunction "2_2") (pintype "passive"))
      (node (ref "TP63") (pin "1") (pinfunction "1_1") (pintype "passive"))
      (node (ref "U12") (pin "5") (pinfunction "VDD_5") (pintype "power_in"))
      (node (ref "U13") (pin "5") (pinfunction "VDD_5") (pintype "power_in"))
      (node (ref "U16") (pin "14") (pinfunction "V+_14") (pintype "power_in"))
    )
    (net (code "208") (name "unconnected-(J1-DEBUG-0-Pad17)") (class "Default")
      (node (ref "J1") (pin "17") (pinfunction "DEBUG-0_17") (pintype "passive"))
    )
    (net (code "209") (name "unconnected-(J1-HOST-D+-Pad7)") (class "Default")
      (node (ref "J1") (pin "7") (pinfunction "HOST-D+_7") (pintype "passive"))
    )
    (net (code "210") (name "unconnected-(J1-HOST-D--Pad8)") (class "Default")
      (node (ref "J1") (pin "8") (pinfunction "HOST-D-_8") (pintype "passive"))
    )
    (net (code "211") (name "unconnected-(J1-NRST-Pad10)") (class "Default")
      (node (ref "J1") (pin "10") (pinfunction "NRST_10") (pintype "passive"))
    )
    (net (code "212") (name "unconnected-(J1-SWCLK-Pad15)") (class "Default")
      (node (ref "J1") (pin "15") (pinfunction "SWCLK_15") (pintype "passive"))
    )
    (net (code "213") (name "unconnected-(J1-SWDIO-Pad14)") (class "Default")
      (node (ref "J1") (pin "14") (pinfunction "SWDIO_14") (pintype "passive"))
    )
    (net (code "214") (name "unconnected-(J1-SWO-Pad16)") (class "Default")
      (node (ref "J1") (pin "16") (pinfunction "SWO_16") (pintype "passive"))
    )
    (net (code "215") (name "unconnected-(J1-VTARGET-Pad11)") (class "Default")
      (node (ref "J1") (pin "11") (pinfunction "VTARGET_11") (pintype "passive"))
    )
    (net (code "216") (name "unconnected-(R8-11-Pad1)") (class "Default")
      (node (ref "R8") (pin "1") (pinfunction "11_1") (pintype "passive"))
    )
    (net (code "217") (name "unconnected-(R9-11-Pad1)") (class "Default")
      (node (ref "R9") (pin "1") (pinfunction "11_1") (pintype "passive"))
    )
    (net (code "218") (name "unconnected-(R10-33-Pad3)") (class "Default")
      (node (ref "R10") (pin "3") (pinfunction "33_3") (pintype "passive"))
    )
    (net (code "219") (name "unconnected-(R10-44-Pad4)") (class "Default")
      (node (ref "R10") (pin "4") (pinfunction "44_4") (pintype "passive"))
    )
    (net (code "220") (name "unconnected-(R10-66-Pad6)") (class "Default")
      (node (ref "R10") (pin "6") (pinfunction "66_6") (pintype "passive"))
    )
    (net (code "221") (name "unconnected-(R10-77-Pad7)") (class "Default")
      (node (ref "R10") (pin "7") (pinfunction "77_7") (pintype "passive"))
    )
    (net (code "222") (name "unconnected-(U2-RXOUT7-Pad34)") (class "Default")
      (node (ref "U2") (pin "34") (pinfunction "RXOUT7_34") (pintype "output"))
    )
    (net (code "223") (name "unconnected-(U2-RXOUT8-Pad35)") (class "Default")
      (node (ref "U2") (pin "35") (pinfunction "RXOUT8_35") (pintype "output"))
    )
    (net (code "224") (name "unconnected-(U2-RXOUT9-Pad37)") (class "Default")
      (node (ref "U2") (pin "37") (pinfunction "RXOUT9_37") (pintype "output"))
    )
    (net (code "225") (name "unconnected-(U2-RXOUT10-Pad39)") (class "Default")
      (node (ref "U2") (pin "39") (pinfunction "RXOUT10_39") (pintype "output"))
    )
    (net (code "226") (name "unconnected-(U2-RXOUT11-Pad40)") (class "Default")
      (node (ref "U2") (pin "40") (pinfunction "RXOUT11_40") (pintype "output"))
    )
    (net (code "227") (name "unconnected-(U2-RXOUT12-Pad41)") (class "Default")
      (node (ref "U2") (pin "41") (pinfunction "RXOUT12_41") (pintype "output"))
    )
    (net (code "228") (name "unconnected-(U2-RXOUT13-Pad43)") (class "Default")
      (node (ref "U2") (pin "43") (pinfunction "RXOUT13_43") (pintype "output"))
    )
    (net (code "229") (name "unconnected-(U2-RXOUT14-Pad45)") (class "Default")
      (node (ref "U2") (pin "45") (pinfunction "RXOUT14_45") (pintype "output"))
    )
    (net (code "230") (name "unconnected-(U2-RXOUT15-Pad46)") (class "Default")
      (node (ref "U2") (pin "46") (pinfunction "RXOUT15_46") (pintype "output"))
    )
    (net (code "231") (name "unconnected-(U2-RXOUT16-Pad47)") (class "Default")
      (node (ref "U2") (pin "47") (pinfunction "RXOUT16_47") (pintype "output"))
    )
    (net (code "232") (name "unconnected-(U2-RXOUT17-Pad1)") (class "Default")
      (node (ref "U2") (pin "1") (pinfunction "RXOUT17_1") (pintype "output"))
    )
    (net (code "233") (name "unconnected-(U2-RXOUT18-Pad2)") (class "Default")
      (node (ref "U2") (pin "2") (pinfunction "RXOUT18_2") (pintype "output"))
    )
    (net (code "234") (name "unconnected-(U2-RXOUT19-Pad4)") (class "Default")
      (node (ref "U2") (pin "4") (pinfunction "RXOUT19_4") (pintype "output"))
    )
    (net (code "235") (name "unconnected-(U2-RXOUT20-Pad5)") (class "Default")
      (node (ref "U2") (pin "5") (pinfunction "RXOUT20_5") (pintype "output"))
    )
    (net (code "236") (name "unconnected-(U7B-AIN4-PadC7)") (class "Default")
      (node (ref "U7") (pin "C7") (pinfunction "AIN4_C7") (pintype "bidirectional"))
    )
    (net (code "237") (name "unconnected-(U7B-AIN5-PadC8)") (class "Default")
      (node (ref "U7") (pin "C8") (pinfunction "AIN5_C8") (pintype "bidirectional"))
    )
    (net (code "238") (name "unconnected-(U7B-AIN6-PadC9)") (class "Default")
      (node (ref "U7") (pin "C9") (pinfunction "AIN6_C9") (pintype "bidirectional"))
    )
    (net (code "239") (name "unconnected-(U7B-AIN7-PadD7)") (class "Default")
      (node (ref "U7") (pin "D7") (pinfunction "AIN7_D7") (pintype "bidirectional"))
    )
    (net (code "240") (name "unconnected-(U7C-GPMC_A0-PadT12)") (class "Default")
      (node (ref "U7") (pin "T12") (pinfunction "GPMC_A0_T12") (pintype "bidirectional"))
    )
    (net (code "241") (name "unconnected-(U7C-GPMC_A1-PadR12)") (class "Default")
      (node (ref "U7") (pin "R12") (pinfunction "GPMC_A1_R12") (pintype "bidirectional"))
    )
    (net (code "242") (name "unconnected-(U7C-GPMC_A2-PadP12)") (class "Default")
      (node (ref "U7") (pin "P12") (pinfunction "GPMC_A2_P12") (pintype "bidirectional"))
    )
    (net (code "243") (name "unconnected-(U7C-GPMC_A3-PadT13)") (class "Default")
      (node (ref "U7") (pin "T13") (pinfunction "GPMC_A3_T13") (pintype "bidirectional"))
    )
    (net (code "244") (name "unconnected-(U7C-GPMC_A9-PadT15)") (class "Default")
      (node (ref "U7") (pin "T15") (pinfunction "GPMC_A9_T15") (pintype "bidirectional"))
    )
    (net (code "245") (name "unconnected-(U7C-GPMC_A10-PadR15)") (class "Default")
      (node (ref "U7") (pin "R15") (pinfunction "GPMC_A10_R15") (pintype "bidirectional"))
    )
    (net (code "246") (name "unconnected-(U7C-GPMC_A11-PadT16)") (class "Default")
      (node (ref "U7") (pin "T16") (pinfunction "GPMC_A11_T16") (pintype "bidirectional"))
    )
    (net (code "247") (name "unconnected-(U7C-GPMC_AD8-PadT4)") (class "Default")
      (node (ref "U7") (pin "T4") (pinfunction "GPMC_AD8_T4") (pintype "bidirectional"))
    )
    (net (code "248") (name "unconnected-(U7C-GPMC_AD9-PadP5)") (class "Default")
      (node (ref "U7") (pin "P5") (pinfunction "GPMC_AD9_P5") (pintype "bidirectional"))
    )
    (net (code "249") (name "unconnected-(U7C-GPMC_AD10-PadR5)") (class "Default")
      (node (ref "U7") (pin "R5") (pinfunction "GPMC_AD10_R5") (pintype "bidirectional"))
    )
    (net (code "250") (name "unconnected-(U7C-GPMC_AD11-PadT5)") (class "Default")
      (node (ref "U7") (pin "T5") (pinfunction "GPMC_AD11_T5") (pintype "bidirectional"))
    )
    (net (code "251") (name "unconnected-(U7C-GPMC_AD14-PadT6)") (class "Default")
      (node (ref "U7") (pin "T6") (pinfunction "GPMC_AD14_T6") (pintype "bidirectional"))
    )
    (net (code "252") (name "unconnected-(U7C-GPMC_AD15-PadP7)") (class "Default")
      (node (ref "U7") (pin "P7") (pinfunction "GPMC_AD15_P7") (pintype "bidirectional"))
    )
    (net (code "253") (name "unconnected-(U7C-GPMC_ADVN_ALE-PadM1)") (class "Default")
      (node (ref "U7") (pin "M1") (pinfunction "GPMC_ADVN_ALE_M1") (pintype "bidirectional"))
    )
    (net (code "254") (name "unconnected-(U7C-GPMC_BEN0_CLE-PadN3)") (class "Default")
      (node (ref "U7") (pin "N3") (pinfunction "GPMC_BEN0_CLE_N3") (pintype "bidirectional"))
    )
    (net (code "255") (name "unconnected-(U7C-GPMC_BEN1-PadN14)") (class "Default")
      (node (ref "U7") (pin "N14") (pinfunction "GPMC_BEN1_N14") (pintype "bidirectional"))
    )
    (net (code "256") (name "unconnected-(U7C-GPMC_CLK-PadT7)") (class "Default")
      (node (ref "U7") (pin "T7") (pinfunction "GPMC_CLK_T7") (pintype "bidirectional"))
    )
    (net (code "257") (name "unconnected-(U7C-GPMC_CSN0-PadP3)") (class "Default")
      (node (ref "U7") (pin "P3") (pinfunction "GPMC_CSN0_P3") (pintype "bidirectional"))
    )
    (net (code "258") (name "unconnected-(U7C-GPMC_CSN3-PadR7)") (class "Default")
      (node (ref "U7") (pin "R7") (pinfunction "GPMC_CSN3_R7") (pintype "bidirectional"))
    )
    (net (code "259") (name "unconnected-(U7C-GPMC_OEN_REN-PadN1)") (class "Default")
      (node (ref "U7") (pin "N1") (pinfunction "GPMC_OEN_REN_N1") (pintype "bidirectional"))
    )
    (net (code "260") (name "unconnected-(U7C-GPMC_WAIT0-PadP15)") (class "Default")
      (node (ref "U7") (pin "P15") (pinfunction "GPMC_WAIT0_P15") (pintype "bidirectional"))
    )
    (net (code "261") (name "unconnected-(U7C-GPMC_WEN-PadN2)") (class "Default")
      (node (ref "U7") (pin "N2") (pinfunction "GPMC_WEN_N2") (pintype "bidirectional"))
    )
    (net (code "262") (name "unconnected-(U7C-GPMC_WPN-PadR16)") (class "Default")
      (node (ref "U7") (pin "R16") (pinfunction "GPMC_WPN_R16") (pintype "bidirectional"))
    )
    (net (code "263") (name "unconnected-(U7C-XDMA_EVENT_INTR0-PadA4)") (class "Default")
      (node (ref "U7") (pin "A4") (pinfunction "XDMA_EVENT_INTR0_A4") (pintype "bidirectional"))
    )
    (net (code "264") (name "unconnected-(U7D-LCD_AC_BIAS_EN-PadE1)") (class "Default")
      (node (ref "U7") (pin "E1") (pinfunction "LCD_AC_BIAS_EN_E1") (pintype "bidirectional"))
    )
    (net (code "265") (name "unconnected-(U7D-LCD_HSYNC-PadF2)") (class "Default")
      (node (ref "U7") (pin "F2") (pinfunction "LCD_HSYNC_F2") (pintype "bidirectional"))
    )
    (net (code "266") (name "unconnected-(U7D-MDC-PadD13)") (class "Default")
      (node (ref "U7") (pin "D13") (pinfunction "MDC_D13") (pintype "bidirectional"))
    )
    (net (code "267") (name "unconnected-(U7D-MDIO-PadE13)") (class "Default")
      (node (ref "U7") (pin "E13") (pinfunction "MDIO_E13") (pintype "bidirectional"))
    )
    (net (code "268") (name "unconnected-(U7D-MII1_COL-PadF15)") (class "Default")
      (node (ref "U7") (pin "F15") (pinfunction "MII1_COL_F15") (pintype "bidirectional"))
    )
    (net (code "269") (name "unconnected-(U7D-MII1_CRS-PadF14)") (class "Default")
      (node (ref "U7") (pin "F14") (pinfunction "MII1_CRS_F14") (pintype "bidirectional"))
    )
    (net (code "270") (name "unconnected-(U7D-MII1_RXD0-PadE14)") (class "Default")
      (node (ref "U7") (pin "E14") (pinfunction "MII1_RXD0_E14") (pintype "bidirectional"))
    )
    (net (code "271") (name "unconnected-(U7D-MII1_RXD1-PadD16)") (class "Default")
      (node (ref "U7") (pin "D16") (pinfunction "MII1_RXD1_D16") (pintype "bidirectional"))
    )
    (net (code "272") (name "unconnected-(U7D-MII1_RXD2-PadD15)") (class "Default")
      (node (ref "U7") (pin "D15") (pinfunction "MII1_RXD2_D15") (pintype "bidirectional"))
    )
    (net (code "273") (name "unconnected-(U7D-MII1_RXD3-PadD14)") (class "Default")
      (node (ref "U7") (pin "D14") (pinfunction "MII1_RXD3_D14") (pintype "bidirectional"))
    )
    (net (code "274") (name "unconnected-(U7D-MII1_RX_CLK-PadE16)") (class "Default")
      (node (ref "U7") (pin "E16") (pinfunction "MII1_RX_CLK_E16") (pintype "bidirectional"))
    )
    (net (code "275") (name "unconnected-(U7D-MII1_RX_DV-PadF16)") (class "Default")
      (node (ref "U7") (pin "F16") (pinfunction "MII1_RX_DV_F16") (pintype "bidirectional"))
    )
    (net (code "276") (name "unconnected-(U7D-MII1_RX_ER-PadE15)") (class "Default")
      (node (ref "U7") (pin "E15") (pinfunction "MII1_RX_ER_E15") (pintype "bidirectional"))
    )
    (net (code "277") (name "unconnected-(U7D-MII1_TXD0-PadH15)") (class "Default")
      (node (ref "U7") (pin "H15") (pinfunction "MII1_TXD0_H15") (pintype "bidirectional"))
    )
    (net (code "278") (name "unconnected-(U7D-MII1_TXD1-PadH14)") (class "Default")
      (node (ref "U7") (pin "H14") (pinfunction "MII1_TXD1_H14") (pintype "bidirectional"))
    )
    (net (code "279") (name "unconnected-(U7D-MII1_TXD2-PadG16)") (class "Default")
      (node (ref "U7") (pin "G16") (pinfunction "MII1_TXD2_G16") (pintype "bidirectional"))
    )
    (net (code "280") (name "unconnected-(U7D-MII1_TXD3-PadG15)") (class "Default")
      (node (ref "U7") (pin "G15") (pinfunction "MII1_TXD3_G15") (pintype "bidirectional"))
    )
    (net (code "281") (name "unconnected-(U7D-MII1_TX_CLK-PadH16)") (class "Default")
      (node (ref "U7") (pin "H16") (pinfunction "MII1_TX_CLK_H16") (pintype "bidirectional"))
    )
    (net (code "282") (name "unconnected-(U7D-MII1_TX_EN-PadG14)") (class "Default")
      (node (ref "U7") (pin "G14") (pinfunction "MII1_TX_EN_G14") (pintype "bidirectional"))
    )
    (net (code "283") (name "unconnected-(U7D-RMII1_REF_CLK-PadJ14)") (class "Default")
      (node (ref "U7") (pin "J14") (pinfunction "RMII1_REF_CLK_J14") (pintype "bidirectional"))
    )
    (net (code "284") (name "unconnected-(U7F-NC-PadD12)") (class "Default")
      (node (ref "U7") (pin "D12") (pinfunction "NC_D12") (pintype "bidirectional"))
    )
    (net (code "285") (name "unconnected-(U7F-NC-PadJ6)") (class "Default")
      (node (ref "U7") (pin "J6") (pinfunction "NC_J6") (pintype "bidirectional"))
    )
    (net (code "286") (name "unconnected-(U7F-NC-PadK4)") (class "Default")
      (node (ref "U7") (pin "K4") (pinfunction "NC_K4") (pintype "bidirectional"))
    )
    (net (code "287") (name "~{FAULT}") (class "Default")
      (node (ref "Q2") (pin "3") (pinfunction "D_3") (pintype "passive"))
      (node (ref "R32") (pin "1") (pinfunction "1_1") (pintype "passive"))
      (node (ref "TP45") (pin "1") (pinfunction "1_1") (pintype "passive"))
      (node (ref "U16") (pin "7") (pinfunction "IO2_7") (pintype "bidirectional"))
    )
    (net (code "288") (name "~{SD}") (class "Default")
      (node (ref "J4") (pin "39") (pinfunction "39_39") (pintype "passive"))
      (node (ref "J4") (pin "40") (pinfunction "40_40") (pintype "passive"))
    )
  )
)
